# CameraBoard.net
KiCad netlist of a schematic drawn in Altium Designer
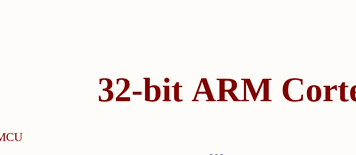
[diagram p0: CameraBoard.SchDoc, top left]
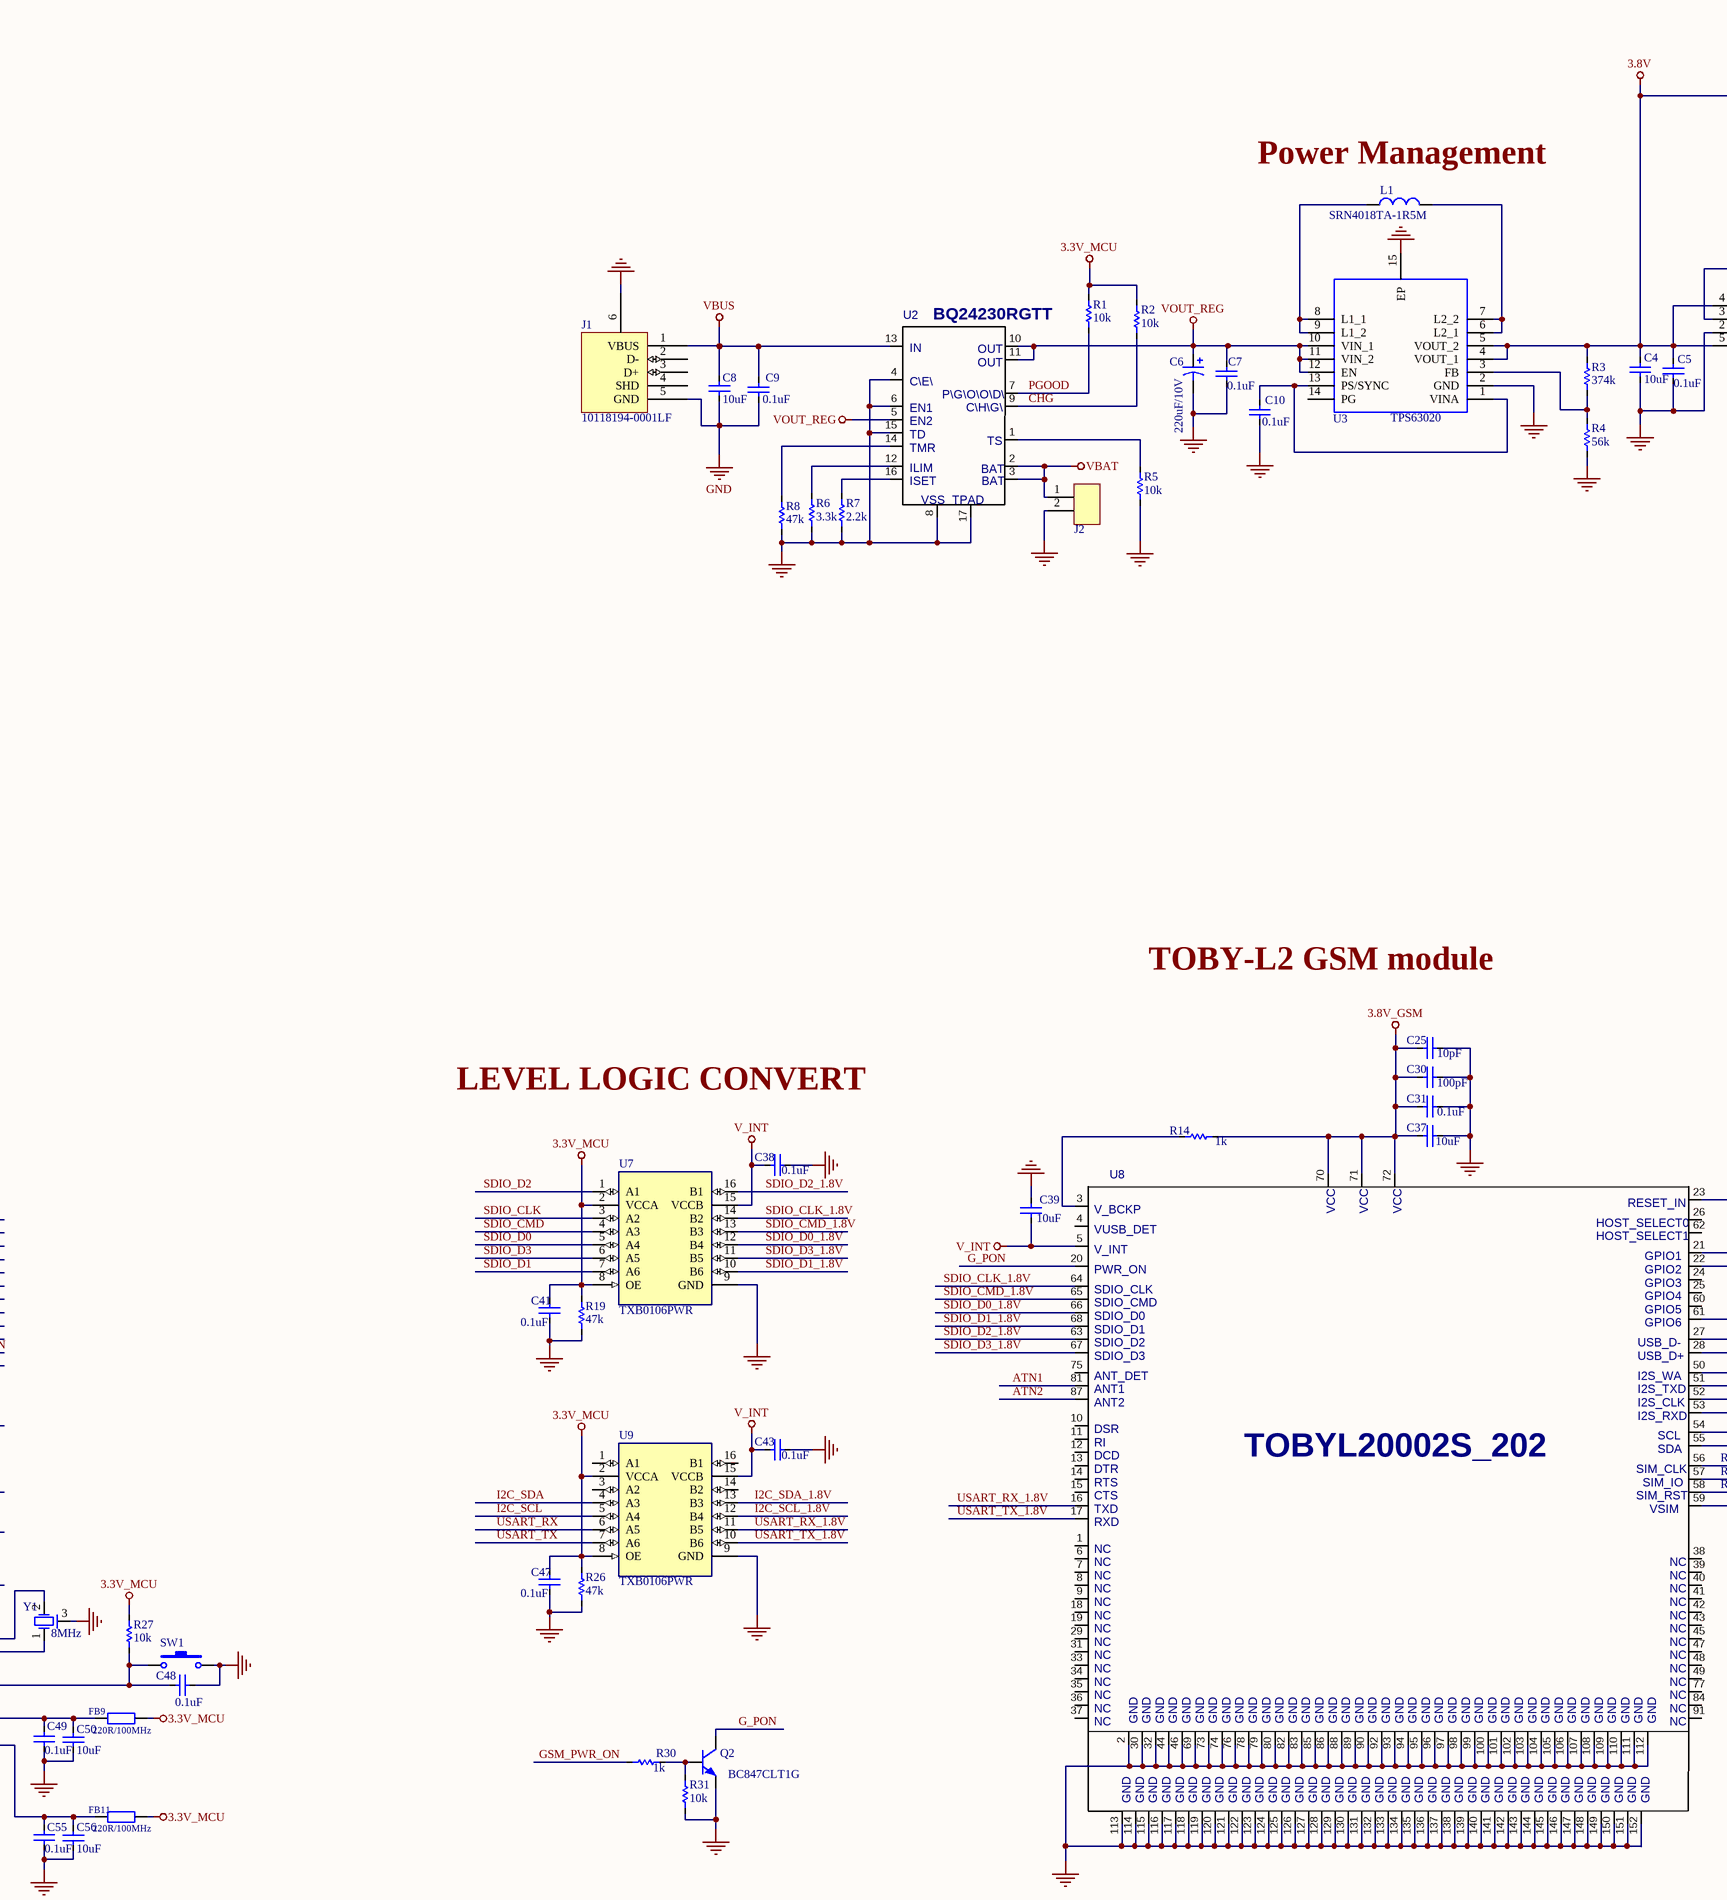
[diagram p1: CameraBoard.SchDoc, top middle]
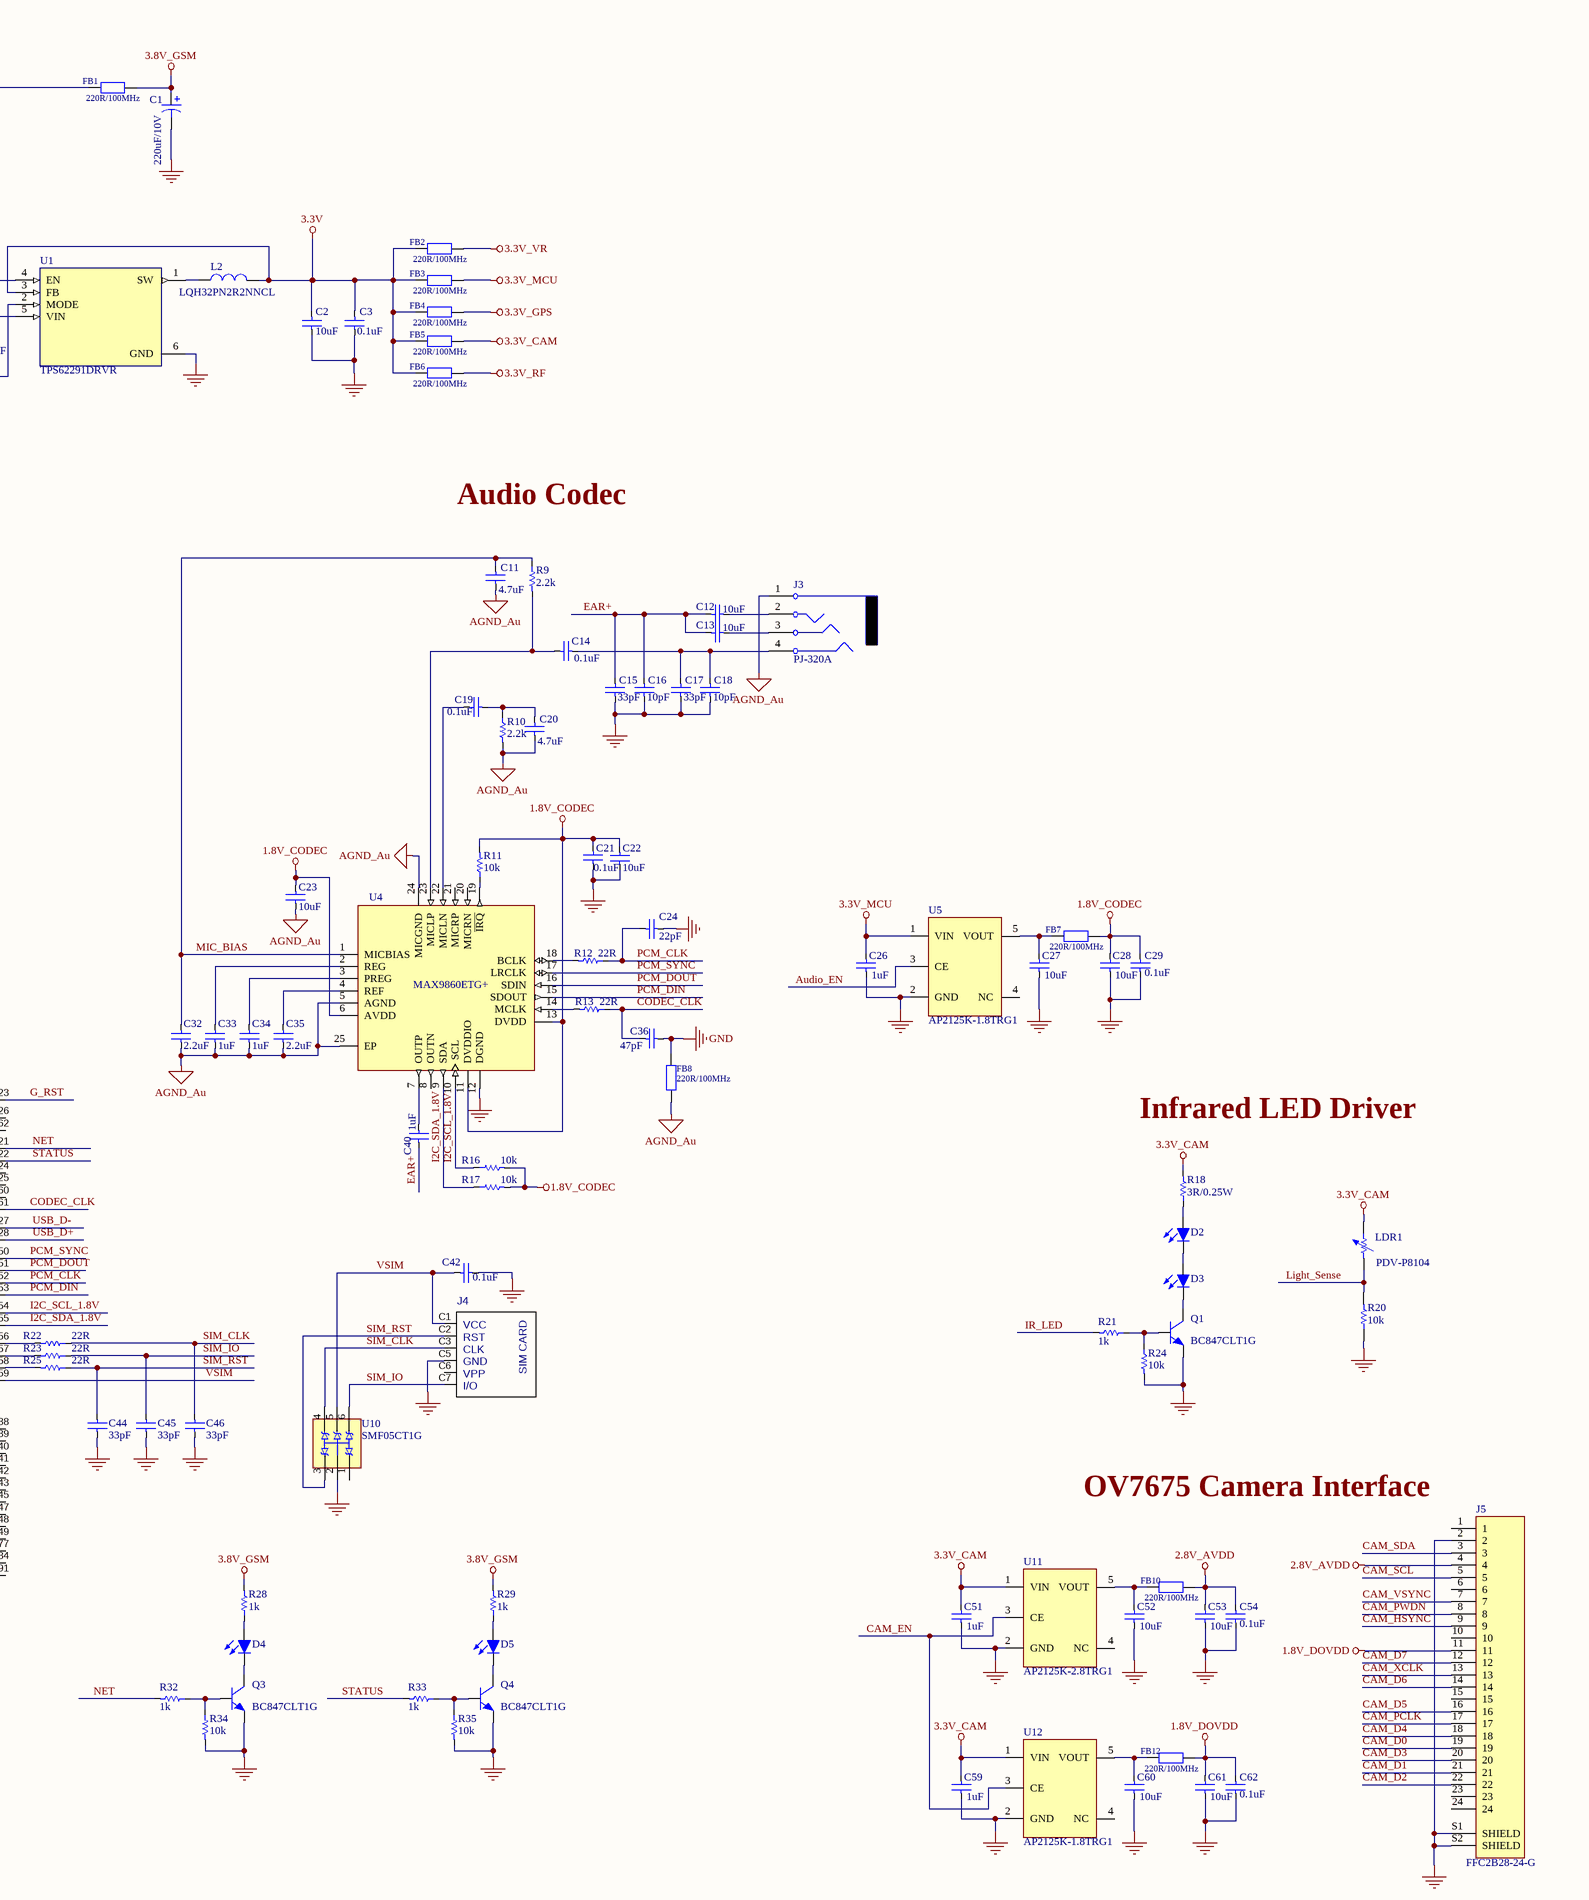
[diagram p2: CameraBoard.SchDoc, top right]
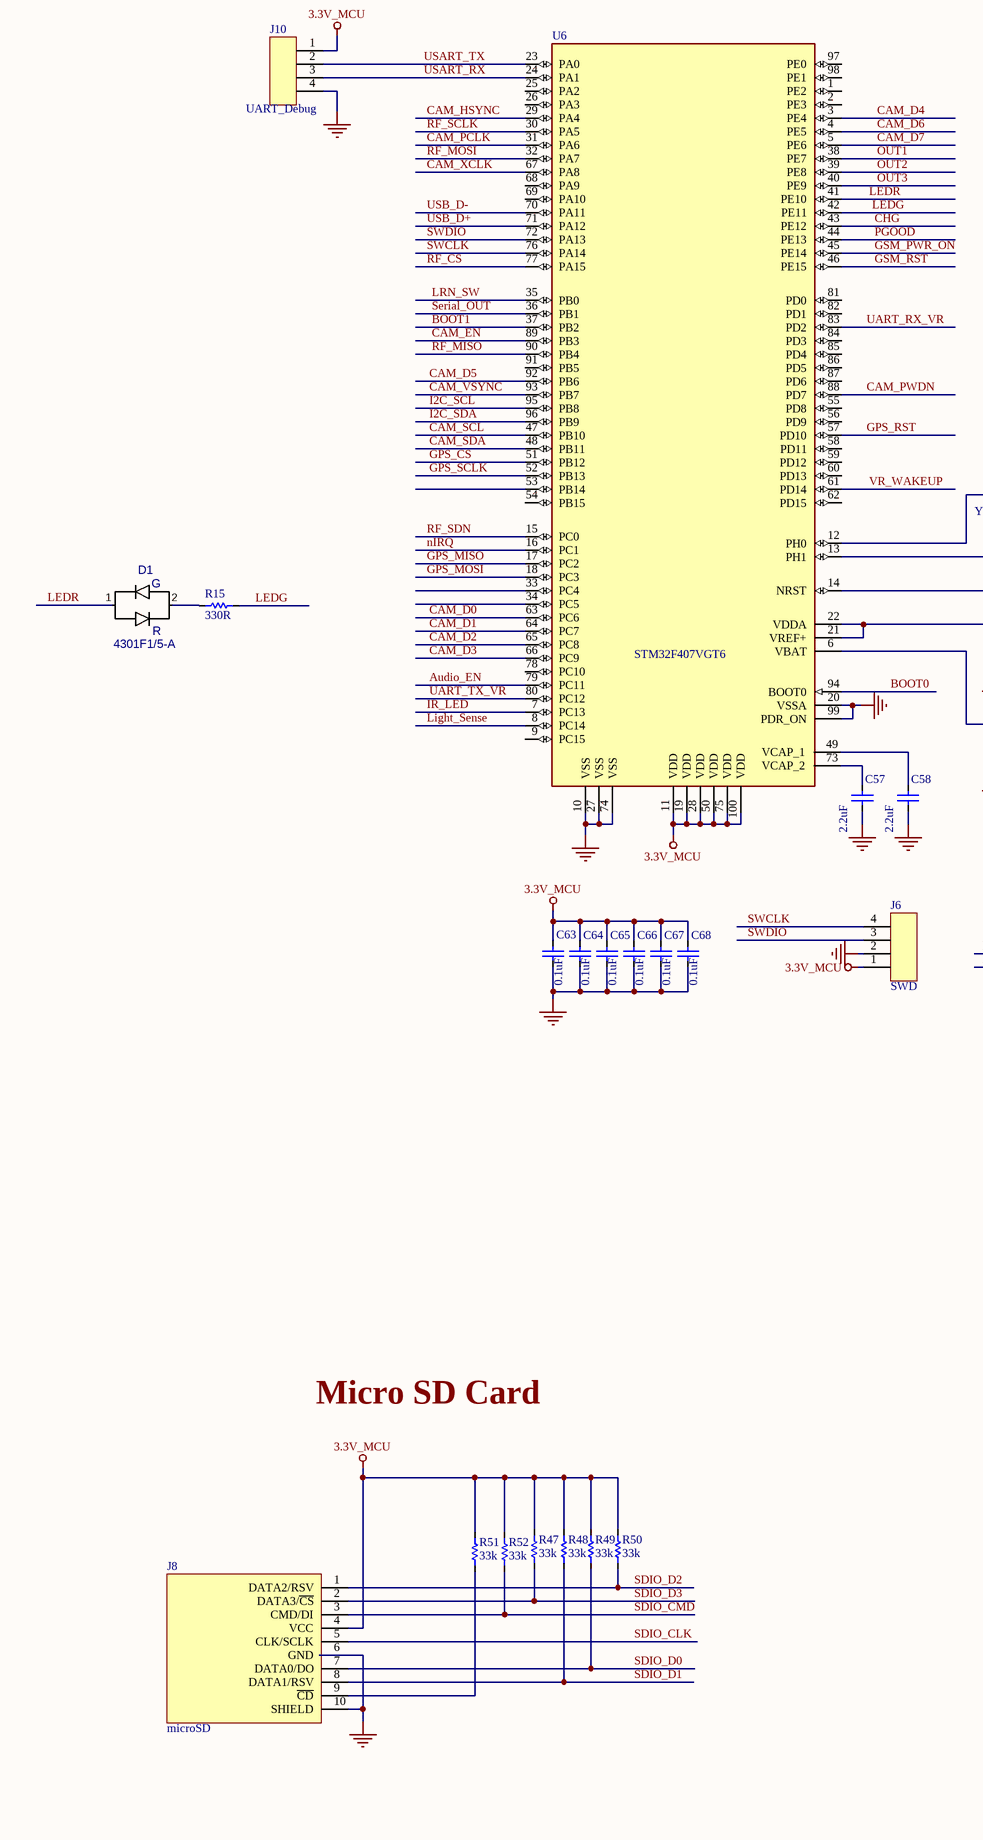
[diagram p3: CameraBoard.SchDoc, bottom left]
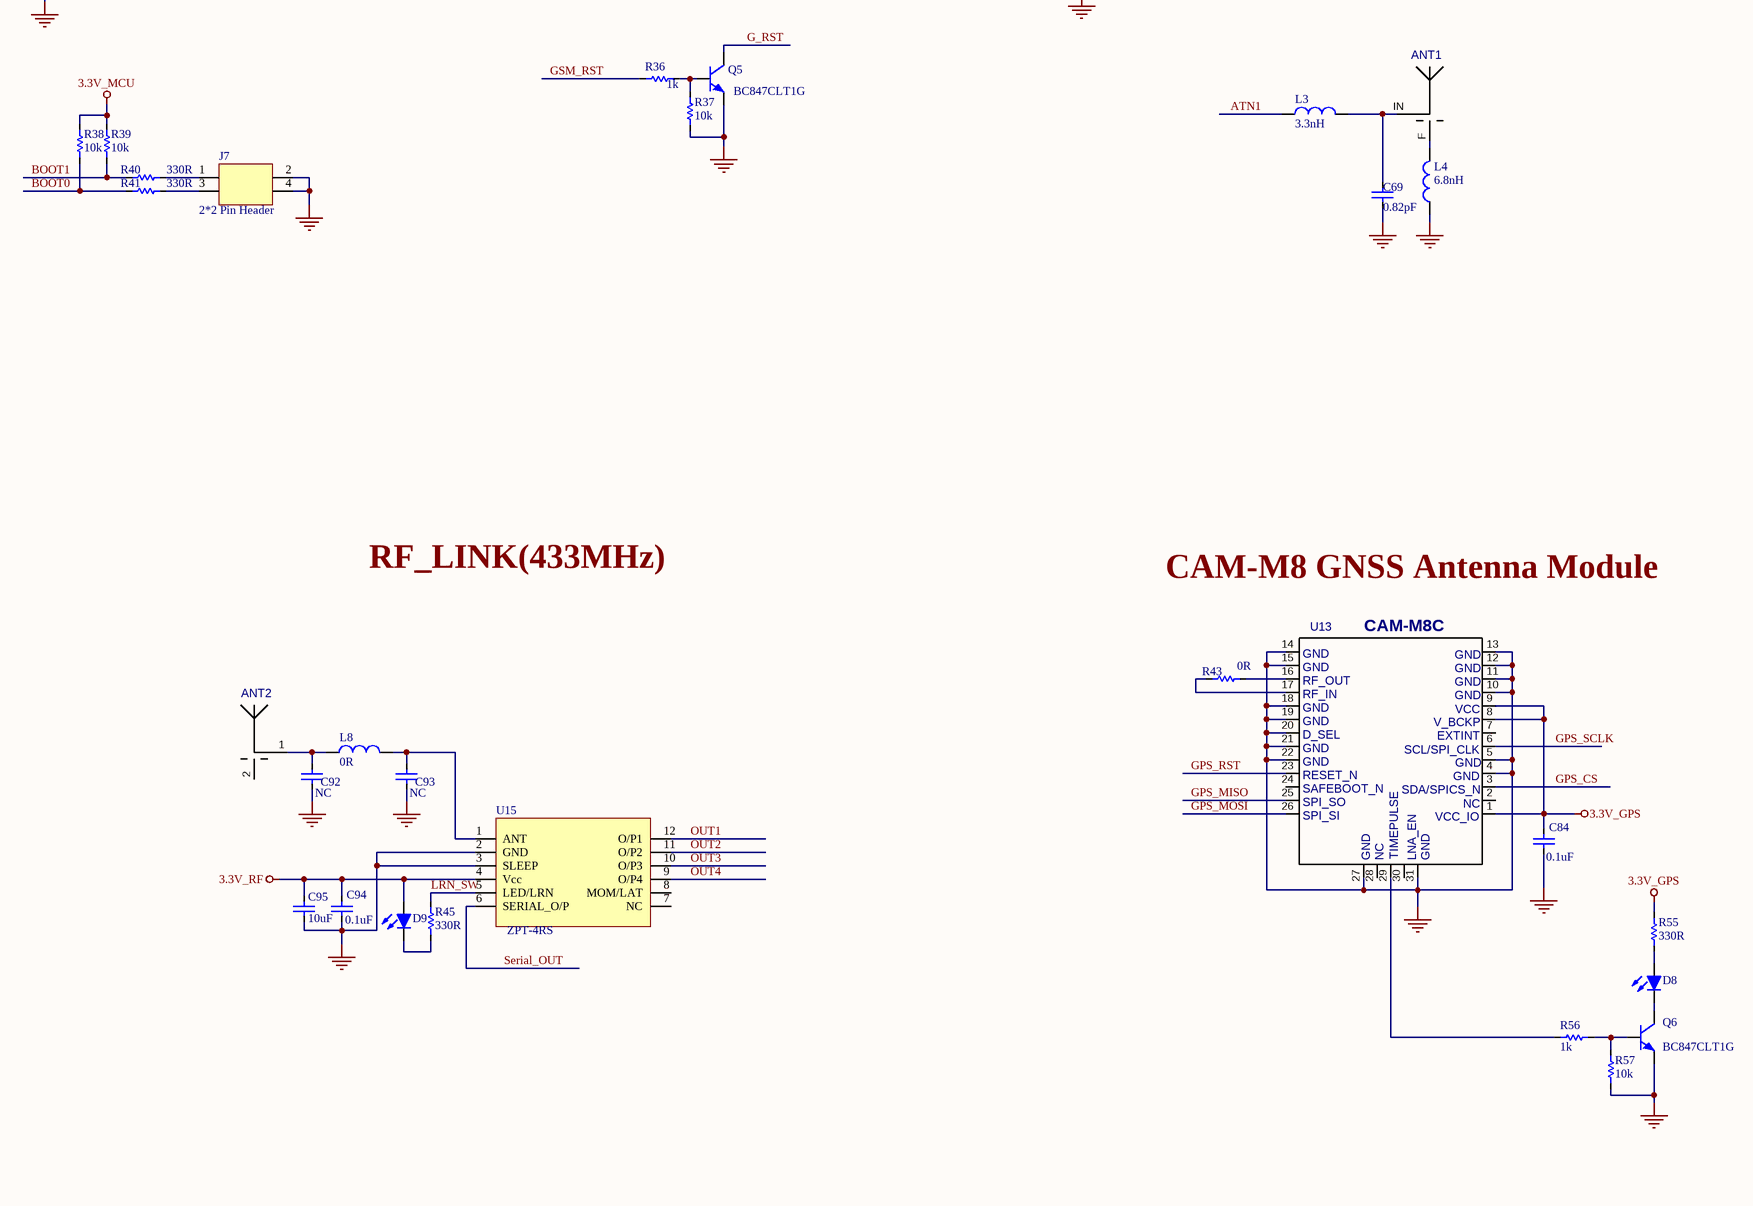
[diagram p4: CameraBoard.SchDoc, bottom middle]
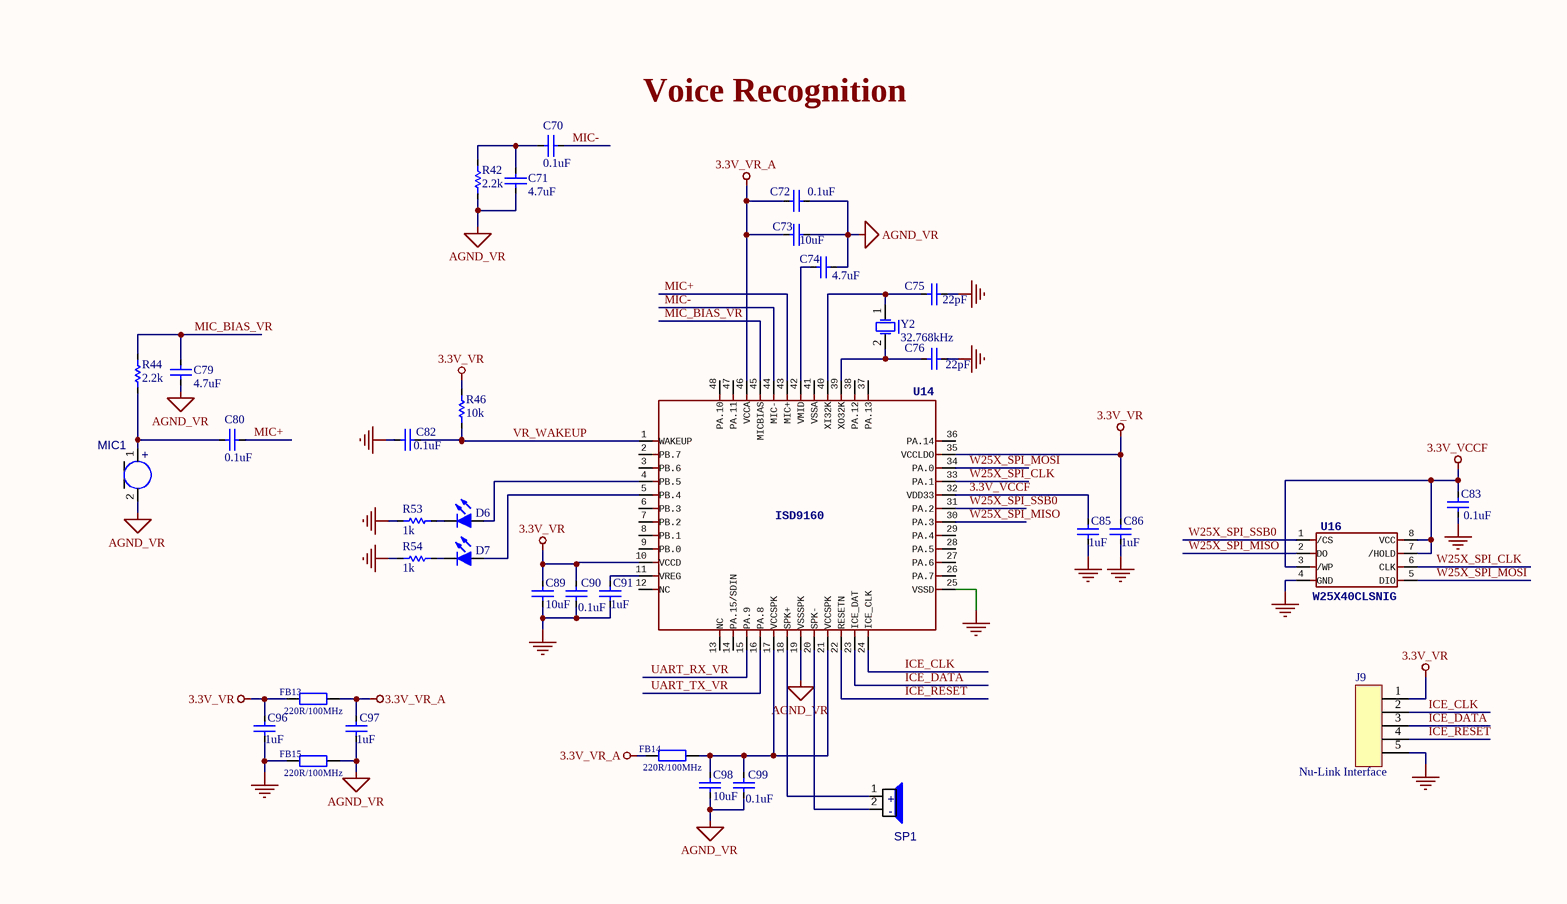
[diagram p5: CameraBoard.SchDoc, bottom right]

(export (version "E")
  (design (tool "Eeschema 10.0.6"))
  (components
    (comp (ref "ANT1")
      (value "Ant W3796_6")
      (footprint "Ant W3796_Ant W3796(Primary)")
      (libsource (lib "") (part "Ant W3796_6_1"))
    )
    (comp (ref "ANT2")
      (value "ACAG1204-868-T")
      (footprint "Antenna_SMD_ANT1204F002R0433A")
      (description "RF ANT 868MHZ CHIP SOLDER SMD")
      (libsource (lib "CameraBoard") (part "Ant W3796_6"))
    )
    (comp (ref "C1")
      (value "220uF/10V")
      (footprint "Tantalum C(E)")
      (description "TPSE227K010T0100V")
      (fields (field (name "PUBLISHER") "Altium Limited"))
      (libsource (lib "Miscellaneous Devices") (part "Cap Pol1"))
    )
    (comp (ref "C2")
      (value "10uF")
      (footprint "SMD_C(0603)")
      (description "PHE840MA6100MA04R17")
      (fields
        (field (name "MANUFACTURER") "Yageo")
        (field (name "MANUFACTURER PART NUMBER") "CC0603KPX7R9BB104")
      )
      (libsource (lib "Miscellaneous Devices") (part "Cap"))
    )
    (comp (ref "C3")
      (value "0.1uF")
      (footprint "SMD_C(0402)")
      (description "PHE840MA6100MA04R17")
      (fields
        (field (name "MANUFACTURER") "Yageo")
        (field (name "MANUFACTURER PART NUMBER") "CC0603KPX7R9BB104")
      )
      (libsource (lib "Miscellaneous Devices") (part "Cap"))
    )
    (comp (ref "C4")
      (value "10uF")
      (footprint "SMD_C(0603)")
      (description "PHE840MA6100MA04R17")
      (fields
        (field (name "MANUFACTURER") "Yageo")
        (field (name "MANUFACTURER PART NUMBER") "CC0603KPX7R9BB104")
      )
      (libsource (lib "Miscellaneous Devices") (part "Cap"))
    )
    (comp (ref "C5")
      (value "0.1uF")
      (footprint "SMD_C(0402)")
      (description "PHE840MA6100MA04R17")
      (fields
        (field (name "MANUFACTURER") "Yageo")
        (field (name "MANUFACTURER PART NUMBER") "CC0603KPX7R9BB104")
      )
      (libsource (lib "Miscellaneous Devices") (part "Cap"))
    )
    (comp (ref "C6")
      (value "220uF/10V")
      (footprint "Tantalum C(E)")
      (description "TPSE227K010T0100V")
      (fields (field (name "PUBLISHER") "Altium Limited"))
      (libsource (lib "Miscellaneous Devices") (part "Cap Pol1"))
    )
    (comp (ref "C7")
      (value "0.1uF")
      (footprint "SMD_C(0402)")
      (description "PHE840MA6100MA04R17")
      (fields
        (field (name "MANUFACTURER") "Yageo")
        (field (name "MANUFACTURER PART NUMBER") "CC0603KPX7R9BB104")
      )
      (libsource (lib "Miscellaneous Devices") (part "Cap"))
    )
    (comp (ref "C8")
      (value "10uF")
      (footprint "SMD_C(0603)")
      (description "PHE840MA6100MA04R17")
      (fields
        (field (name "MANUFACTURER") "Yageo")
        (field (name "MANUFACTURER PART NUMBER") "CC0603KPX7R9BB104")
      )
      (libsource (lib "Miscellaneous Devices") (part "Cap"))
    )
    (comp (ref "C9")
      (value "0.1uF")
      (footprint "SMD_C(0402)")
      (description "PHE840MA6100MA04R17")
      (fields
        (field (name "MANUFACTURER") "Yageo")
        (field (name "MANUFACTURER PART NUMBER") "CC0603KPX7R9BB104")
      )
      (libsource (lib "Miscellaneous Devices") (part "Cap"))
    )
    (comp (ref "C10")
      (value "0.1uF")
      (footprint "SMD_C(0402)")
      (description "PHE840MA6100MA04R17")
      (fields
        (field (name "MANUFACTURER") "Yageo")
        (field (name "MANUFACTURER PART NUMBER") "CC0603KPX7R9BB104")
      )
      (libsource (lib "Miscellaneous Devices") (part "Cap"))
    )
    (comp (ref "C11")
      (value "4.7uF")
      (footprint "SMD_C(0603)")
      (description "PHE840MA6100MA04R17")
      (fields
        (field (name "MANUFACTURER") "Yageo")
        (field (name "MANUFACTURER PART NUMBER") "CC0603KPX7R9BB104")
      )
      (libsource (lib "Miscellaneous Devices") (part "Cap"))
    )
    (comp (ref "C12")
      (value "10uF")
      (footprint "SMD_C(0603)")
      (description "PHE840MA6100MA04R17")
      (fields
        (field (name "MANUFACTURER") "Yageo")
        (field (name "MANUFACTURER PART NUMBER") "CC0603KPX7R9BB104")
      )
      (libsource (lib "Miscellaneous Devices") (part "Cap"))
    )
    (comp (ref "C13")
      (value "10uF")
      (footprint "SMD_C(0603)")
      (description "PHE840MA6100MA04R17")
      (fields
        (field (name "MANUFACTURER") "Yageo")
        (field (name "MANUFACTURER PART NUMBER") "CC0603KPX7R9BB104")
      )
      (libsource (lib "Miscellaneous Devices") (part "Cap"))
    )
    (comp (ref "C14")
      (value "0.1uF")
      (footprint "SMD_C(0402)")
      (description "PHE840MA6100MA04R17")
      (fields
        (field (name "MANUFACTURER") "Yageo")
        (field (name "MANUFACTURER PART NUMBER") "CC0603KPX7R9BB104")
      )
      (libsource (lib "Miscellaneous Devices") (part "Cap"))
    )
    (comp (ref "C15")
      (value "33pF")
      (footprint "SMD_C(0402)")
      (description "PHE840MA6100MA04R17")
      (fields
        (field (name "MANUFACTURER") "Yageo")
        (field (name "MANUFACTURER PART NUMBER") "CC0603KPX7R9BB104")
      )
      (libsource (lib "Miscellaneous Devices") (part "Cap"))
    )
    (comp (ref "C16")
      (value "10pF")
      (footprint "SMD_C(0402)")
      (description "PHE840MA6100MA04R17")
      (fields
        (field (name "MANUFACTURER") "Yageo")
        (field (name "MANUFACTURER PART NUMBER") "CC0603KPX7R9BB104")
      )
      (libsource (lib "Miscellaneous Devices") (part "Cap"))
    )
    (comp (ref "C17")
      (value "33pF")
      (footprint "SMD_C(0402)")
      (description "PHE840MA6100MA04R17")
      (fields
        (field (name "MANUFACTURER") "Yageo")
        (field (name "MANUFACTURER PART NUMBER") "CC0603KPX7R9BB104")
      )
      (libsource (lib "Miscellaneous Devices") (part "Cap"))
    )
    (comp (ref "C18")
      (value "10pF")
      (footprint "SMD_C(0402)")
      (description "PHE840MA6100MA04R17")
      (fields
        (field (name "MANUFACTURER") "Yageo")
        (field (name "MANUFACTURER PART NUMBER") "CC0603KPX7R9BB104")
      )
      (libsource (lib "Miscellaneous Devices") (part "Cap"))
    )
    (comp (ref "C19")
      (value "0.1uF")
      (footprint "SMD_C(0402)")
      (description "PHE840MA6100MA04R17")
      (fields
        (field (name "MANUFACTURER") "Yageo")
        (field (name "MANUFACTURER PART NUMBER") "CC0603KPX7R9BB104")
      )
      (libsource (lib "Miscellaneous Devices") (part "Cap"))
    )
    (comp (ref "C20")
      (value "4.7uF")
      (footprint "SMD_C(0603)")
      (description "PHE840MA6100MA04R17")
      (fields
        (field (name "MANUFACTURER") "Yageo")
        (field (name "MANUFACTURER PART NUMBER") "CC0603KPX7R9BB104")
      )
      (libsource (lib "Miscellaneous Devices") (part "Cap"))
    )
    (comp (ref "C21")
      (value "0.1uF")
      (footprint "SMD_C(0402)")
      (description "PHE840MA6100MA04R17")
      (fields
        (field (name "MANUFACTURER") "Yageo")
        (field (name "MANUFACTURER PART NUMBER") "CC0603KPX7R9BB104")
      )
      (libsource (lib "Miscellaneous Devices") (part "Cap"))
    )
    (comp (ref "C22")
      (value "10uF")
      (footprint "SMD_C(0603)")
      (description "PHE840MA6100MA04R17")
      (fields
        (field (name "MANUFACTURER") "Yageo")
        (field (name "MANUFACTURER PART NUMBER") "CC0603KPX7R9BB104")
      )
      (libsource (lib "Miscellaneous Devices") (part "Cap"))
    )
    (comp (ref "C23")
      (value "10uF")
      (footprint "SMD_C(0603)")
      (description "PHE840MA6100MA04R17")
      (fields
        (field (name "MANUFACTURER") "Yageo")
        (field (name "MANUFACTURER PART NUMBER") "CC0603KPX7R9BB104")
      )
      (libsource (lib "Miscellaneous Devices") (part "Cap"))
    )
    (comp (ref "C24")
      (value "22pF")
      (footprint "SMD_C(0402)")
      (description "PHE840MA6100MA04R17")
      (fields
        (field (name "MANUFACTURER") "Yageo")
        (field (name "MANUFACTURER PART NUMBER") "CC0603KPX7R9BB104")
      )
      (libsource (lib "Miscellaneous Devices") (part "Cap"))
    )
    (comp (ref "C25")
      (value "10pF")
      (footprint "SMD_C(0402)")
      (description "PHE840MA6100MA04R17")
      (fields
        (field (name "MANUFACTURER") "Yageo")
        (field (name "MANUFACTURER PART NUMBER") "CC0603KPX7R9BB104")
      )
      (libsource (lib "Miscellaneous Devices") (part "Cap"))
    )
    (comp (ref "C26")
      (value "1uF")
      (footprint "SMD_C(0603)")
      (description "PHE840MA6100MA04R17")
      (fields
        (field (name "MANUFACTURER") "Yageo")
        (field (name "MANUFACTURER PART NUMBER") "CC0603KPX7R9BB104")
      )
      (libsource (lib "Miscellaneous Devices") (part "Cap"))
    )
    (comp (ref "C27")
      (value "10uF")
      (footprint "SMD_C(0603)")
      (description "PHE840MA6100MA04R17")
      (fields
        (field (name "MANUFACTURER") "Yageo")
        (field (name "MANUFACTURER PART NUMBER") "CC0603KPX7R9BB104")
      )
      (libsource (lib "Miscellaneous Devices") (part "Cap"))
    )
    (comp (ref "C28")
      (value "10uF")
      (footprint "SMD_C(0603)")
      (description "PHE840MA6100MA04R17")
      (fields
        (field (name "MANUFACTURER") "Yageo")
        (field (name "MANUFACTURER PART NUMBER") "CC0603KPX7R9BB104")
      )
      (libsource (lib "Miscellaneous Devices") (part "Cap"))
    )
    (comp (ref "C29")
      (value "0.1uF")
      (footprint "SMD_C(0402)")
      (description "PHE840MA6100MA04R17")
      (fields
        (field (name "MANUFACTURER") "Yageo")
        (field (name "MANUFACTURER PART NUMBER") "CC0603KPX7R9BB104")
      )
      (libsource (lib "Miscellaneous Devices") (part "Cap"))
    )
    (comp (ref "C30")
      (value "100pF")
      (footprint "SMD_C(0402)")
      (description "PHE840MA6100MA04R17")
      (fields
        (field (name "MANUFACTURER") "Yageo")
        (field (name "MANUFACTURER PART NUMBER") "CC0603KPX7R9BB104")
      )
      (libsource (lib "Miscellaneous Devices") (part "Cap"))
    )
    (comp (ref "C31")
      (value "0.1uF")
      (footprint "SMD_C(0402)")
      (description "PHE840MA6100MA04R17")
      (fields
        (field (name "MANUFACTURER") "Yageo")
        (field (name "MANUFACTURER PART NUMBER") "CC0603KPX7R9BB104")
      )
      (libsource (lib "Miscellaneous Devices") (part "Cap"))
    )
    (comp (ref "C32")
      (value "2.2uF")
      (footprint "SMD_C(0603)")
      (description "PHE840MA6100MA04R17")
      (fields
        (field (name "MANUFACTURER") "Yageo")
        (field (name "MANUFACTURER PART NUMBER") "CC0603KPX7R9BB104")
      )
      (libsource (lib "Miscellaneous Devices") (part "Cap"))
    )
    (comp (ref "C33")
      (value "1uF")
      (footprint "SMD_C(0603)")
      (description "PHE840MA6100MA04R17")
      (fields
        (field (name "MANUFACTURER") "Yageo")
        (field (name "MANUFACTURER PART NUMBER") "CC0603KPX7R9BB104")
      )
      (libsource (lib "Miscellaneous Devices") (part "Cap"))
    )
    (comp (ref "C34")
      (value "1uF")
      (footprint "SMD_C(0603)")
      (description "PHE840MA6100MA04R17")
      (fields
        (field (name "MANUFACTURER") "Yageo")
        (field (name "MANUFACTURER PART NUMBER") "CC0603KPX7R9BB104")
      )
      (libsource (lib "Miscellaneous Devices") (part "Cap"))
    )
    (comp (ref "C35")
      (value "2.2uF")
      (footprint "SMD_C(0603)")
      (description "PHE840MA6100MA04R17")
      (fields
        (field (name "MANUFACTURER") "Yageo")
        (field (name "MANUFACTURER PART NUMBER") "CC0603KPX7R9BB104")
      )
      (libsource (lib "Miscellaneous Devices") (part "Cap"))
    )
    (comp (ref "C36")
      (value "47pF")
      (footprint "SMD_C(0402)")
      (description "PHE840MA6100MA04R17")
      (fields
        (field (name "MANUFACTURER") "Yageo")
        (field (name "MANUFACTURER PART NUMBER") "CC0603KPX7R9BB104")
      )
      (libsource (lib "Miscellaneous Devices") (part "Cap"))
    )
    (comp (ref "C37")
      (value "10uF")
      (footprint "SMD_C(0603)")
      (description "PHE840MA6100MA04R17")
      (fields
        (field (name "MANUFACTURER") "Yageo")
        (field (name "MANUFACTURER PART NUMBER") "CC0603KPX7R9BB104")
      )
      (libsource (lib "Miscellaneous Devices") (part "Cap"))
    )
    (comp (ref "C38")
      (value "0.1uF")
      (footprint "SMD_C(0402)")
      (description "PHE840MA6100MA04R17")
      (fields
        (field (name "MANUFACTURER") "Yageo")
        (field (name "MANUFACTURER PART NUMBER") "CC0603KPX7R9BB104")
      )
      (libsource (lib "Miscellaneous Devices") (part "Cap"))
    )
    (comp (ref "C39")
      (value "10uF")
      (footprint "SMD_C(0603)")
      (description "PHE840MA6100MA04R17")
      (fields
        (field (name "MANUFACTURER") "Yageo")
        (field (name "MANUFACTURER PART NUMBER") "CC0603KPX7R9BB104")
      )
      (libsource (lib "Miscellaneous Devices") (part "Cap"))
    )
    (comp (ref "C40")
      (value "1uF")
      (footprint "SMD_C(0603)")
      (description "PHE840MA6100MA04R17")
      (fields
        (field (name "MANUFACTURER") "Yageo")
        (field (name "MANUFACTURER PART NUMBER") "CC0603KPX7R9BB104")
      )
      (libsource (lib "Miscellaneous Devices") (part "Cap"))
    )
    (comp (ref "C41")
      (value "0.1uF")
      (footprint "SMD_C(0402)")
      (description "PHE840MA6100MA04R17")
      (fields
        (field (name "MANUFACTURER") "Yageo")
        (field (name "MANUFACTURER PART NUMBER") "CC0603KPX7R9BB104")
      )
      (libsource (lib "Miscellaneous Devices") (part "Cap"))
    )
    (comp (ref "C42")
      (value "0.1uF")
      (footprint "SMD_C(0402)")
      (description "PHE840MA6100MA04R17")
      (fields
        (field (name "MANUFACTURER") "Yageo")
        (field (name "MANUFACTURER PART NUMBER") "CC0603KPX7R9BB104")
      )
      (libsource (lib "Miscellaneous Devices") (part "Cap"))
    )
    (comp (ref "C43")
      (value "0.1uF")
      (footprint "SMD_C(0402)")
      (description "PHE840MA6100MA04R17")
      (fields
        (field (name "MANUFACTURER") "Yageo")
        (field (name "MANUFACTURER PART NUMBER") "CC0603KPX7R9BB104")
      )
      (libsource (lib "Miscellaneous Devices") (part "Cap"))
    )
    (comp (ref "C44")
      (value "33pF")
      (footprint "SMD_C(0402)")
      (description "PHE840MA6100MA04R17")
      (fields
        (field (name "MANUFACTURER") "Yageo")
        (field (name "MANUFACTURER PART NUMBER") "CC0603KPX7R9BB104")
      )
      (libsource (lib "Miscellaneous Devices") (part "Cap"))
    )
    (comp (ref "C45")
      (value "33pF")
      (footprint "SMD_C(0402)")
      (description "PHE840MA6100MA04R17")
      (fields
        (field (name "MANUFACTURER") "Yageo")
        (field (name "MANUFACTURER PART NUMBER") "CC0603KPX7R9BB104")
      )
      (libsource (lib "Miscellaneous Devices") (part "Cap"))
    )
    (comp (ref "C46")
      (value "33pF")
      (footprint "SMD_C(0402)")
      (description "PHE840MA6100MA04R17")
      (fields
        (field (name "MANUFACTURER") "Yageo")
        (field (name "MANUFACTURER PART NUMBER") "CC0603KPX7R9BB104")
      )
      (libsource (lib "Miscellaneous Devices") (part "Cap"))
    )
    (comp (ref "C47")
      (value "0.1uF")
      (footprint "SMD_C(0402)")
      (description "PHE840MA6100MA04R17")
      (fields
        (field (name "MANUFACTURER") "Yageo")
        (field (name "MANUFACTURER PART NUMBER") "CC0603KPX7R9BB104")
      )
      (libsource (lib "Miscellaneous Devices") (part "Cap"))
    )
    (comp (ref "C48")
      (value "0.1uF")
      (footprint "SMD_C(0402)")
      (description "PHE840MA6100MA04R17")
      (fields
        (field (name "MANUFACTURER") "Yageo")
        (field (name "MANUFACTURER PART NUMBER") "CC0603KPX7R9BB104")
      )
      (libsource (lib "Miscellaneous Devices") (part "Cap"))
    )
    (comp (ref "C49")
      (value "0.1uF")
      (footprint "SMD_C(0402)")
      (description "PHE840MA6100MA04R17")
      (fields
        (field (name "MANUFACTURER") "Yageo")
        (field (name "MANUFACTURER PART NUMBER") "CC0603KPX7R9BB104")
      )
      (libsource (lib "Miscellaneous Devices") (part "Cap"))
    )
    (comp (ref "C50")
      (value "10uF")
      (footprint "SMD_C(0603)")
      (description "PHE840MA6100MA04R17")
      (fields
        (field (name "MANUFACTURER") "Yageo")
        (field (name "MANUFACTURER PART NUMBER") "CC0603KPX7R9BB104")
      )
      (libsource (lib "Miscellaneous Devices") (part "Cap"))
    )
    (comp (ref "C51")
      (value "1uF")
      (footprint "SMD_C(0603)")
      (description "PHE840MA6100MA04R17")
      (fields
        (field (name "MANUFACTURER") "Yageo")
        (field (name "MANUFACTURER PART NUMBER") "CC0603KPX7R9BB104")
      )
      (libsource (lib "Miscellaneous Devices") (part "Cap"))
    )
    (comp (ref "C52")
      (value "10uF")
      (footprint "SMD_C(0603)")
      (description "PHE840MA6100MA04R17")
      (fields
        (field (name "MANUFACTURER") "Yageo")
        (field (name "MANUFACTURER PART NUMBER") "CC0603KPX7R9BB104")
      )
      (libsource (lib "Miscellaneous Devices") (part "Cap"))
    )
    (comp (ref "C53")
      (value "10uF")
      (footprint "SMD_C(0603)")
      (description "PHE840MA6100MA04R17")
      (fields
        (field (name "MANUFACTURER") "Yageo")
        (field (name "MANUFACTURER PART NUMBER") "CC0603KPX7R9BB104")
      )
      (libsource (lib "Miscellaneous Devices") (part "Cap"))
    )
    (comp (ref "C54")
      (value "0.1uF")
      (footprint "SMD_C(0402)")
      (description "PHE840MA6100MA04R17")
      (fields
        (field (name "MANUFACTURER") "Yageo")
        (field (name "MANUFACTURER PART NUMBER") "CC0603KPX7R9BB104")
      )
      (libsource (lib "Miscellaneous Devices") (part "Cap"))
    )
    (comp (ref "C55")
      (value "0.1uF")
      (footprint "SMD_C(0402)")
      (description "PHE840MA6100MA04R17")
      (fields
        (field (name "MANUFACTURER") "Yageo")
        (field (name "MANUFACTURER PART NUMBER") "CC0603KPX7R9BB104")
      )
      (libsource (lib "Miscellaneous Devices") (part "Cap"))
    )
    (comp (ref "C56")
      (value "10uF")
      (footprint "SMD_C(0603)")
      (description "PHE840MA6100MA04R17")
      (fields
        (field (name "MANUFACTURER") "Yageo")
        (field (name "MANUFACTURER PART NUMBER") "CC0603KPX7R9BB104")
      )
      (libsource (lib "Miscellaneous Devices") (part "Cap"))
    )
    (comp (ref "C57")
      (value "2.2uF")
      (footprint "SMD_C(0603)")
      (description "PHE840MA6100MA04R17")
      (fields
        (field (name "MANUFACTURER") "Yageo")
        (field (name "MANUFACTURER PART NUMBER") "CC0603KPX7R9BB104")
      )
      (libsource (lib "Miscellaneous Devices") (part "Cap"))
    )
    (comp (ref "C58")
      (value "2.2uF")
      (footprint "SMD_C(0603)")
      (description "PHE840MA6100MA04R17")
      (fields
        (field (name "MANUFACTURER") "Yageo")
        (field (name "MANUFACTURER PART NUMBER") "CC0603KPX7R9BB104")
      )
      (libsource (lib "Miscellaneous Devices") (part "Cap"))
    )
    (comp (ref "C59")
      (value "1uF")
      (footprint "SMD_C(0603)")
      (description "PHE840MA6100MA04R17")
      (fields
        (field (name "MANUFACTURER") "Yageo")
        (field (name "MANUFACTURER PART NUMBER") "CC0603KPX7R9BB104")
      )
      (libsource (lib "Miscellaneous Devices") (part "Cap"))
    )
    (comp (ref "C60")
      (value "10uF")
      (footprint "SMD_C(0603)")
      (description "PHE840MA6100MA04R17")
      (fields
        (field (name "MANUFACTURER") "Yageo")
        (field (name "MANUFACTURER PART NUMBER") "CC0603KPX7R9BB104")
      )
      (libsource (lib "Miscellaneous Devices") (part "Cap"))
    )
    (comp (ref "C61")
      (value "10uF")
      (footprint "SMD_C(0603)")
      (description "PHE840MA6100MA04R17")
      (fields
        (field (name "MANUFACTURER") "Yageo")
        (field (name "MANUFACTURER PART NUMBER") "CC0603KPX7R9BB104")
      )
      (libsource (lib "Miscellaneous Devices") (part "Cap"))
    )
    (comp (ref "C62")
      (value "0.1uF")
      (footprint "SMD_C(0402)")
      (description "PHE840MA6100MA04R17")
      (fields
        (field (name "MANUFACTURER") "Yageo")
        (field (name "MANUFACTURER PART NUMBER") "CC0603KPX7R9BB104")
      )
      (libsource (lib "Miscellaneous Devices") (part "Cap"))
    )
    (comp (ref "C63")
      (value "0.1uF")
      (footprint "SMD_C(0402)")
      (description "PHE840MA6100MA04R17")
      (fields
        (field (name "MANUFACTURER") "Yageo")
        (field (name "MANUFACTURER PART NUMBER") "CC0603KPX7R9BB104")
      )
      (libsource (lib "Miscellaneous Devices") (part "Cap"))
    )
    (comp (ref "C64")
      (value "0.1uF")
      (footprint "SMD_C(0402)")
      (description "PHE840MA6100MA04R17")
      (fields
        (field (name "MANUFACTURER") "Yageo")
        (field (name "MANUFACTURER PART NUMBER") "CC0603KPX7R9BB104")
      )
      (libsource (lib "Miscellaneous Devices") (part "Cap"))
    )
    (comp (ref "C65")
      (value "0.1uF")
      (footprint "SMD_C(0402)")
      (description "PHE840MA6100MA04R17")
      (fields
        (field (name "MANUFACTURER") "Yageo")
        (field (name "MANUFACTURER PART NUMBER") "CC0603KPX7R9BB104")
      )
      (libsource (lib "Miscellaneous Devices") (part "Cap"))
    )
    (comp (ref "C66")
      (value "0.1uF")
      (footprint "SMD_C(0402)")
      (description "PHE840MA6100MA04R17")
      (fields
        (field (name "MANUFACTURER") "Yageo")
        (field (name "MANUFACTURER PART NUMBER") "CC0603KPX7R9BB104")
      )
      (libsource (lib "Miscellaneous Devices") (part "Cap"))
    )
    (comp (ref "C67")
      (value "0.1uF")
      (footprint "SMD_C(0402)")
      (description "PHE840MA6100MA04R17")
      (fields
        (field (name "MANUFACTURER") "Yageo")
        (field (name "MANUFACTURER PART NUMBER") "CC0603KPX7R9BB104")
      )
      (libsource (lib "Miscellaneous Devices") (part "Cap"))
    )
    (comp (ref "C68")
      (value "0.1uF")
      (footprint "SMD_C(0402)")
      (description "PHE840MA6100MA04R17")
      (fields
        (field (name "MANUFACTURER") "Yageo")
        (field (name "MANUFACTURER PART NUMBER") "CC0603KPX7R9BB104")
      )
      (libsource (lib "Miscellaneous Devices") (part "Cap"))
    )
    (comp (ref "C69")
      (value "0.82pF")
      (footprint "SMD_C(0402)")
      (description "PHE840MA6100MA04R17")
      (fields
        (field (name "MANUFACTURER") "Yageo")
        (field (name "MANUFACTURER PART NUMBER") "CC0603KPX7R9BB104")
      )
      (libsource (lib "Miscellaneous Devices") (part "Cap"))
    )
    (comp (ref "C70")
      (value "0.1uF")
      (footprint "SMD_C(0402)")
      (description "PHE840MA6100MA04R17")
      (fields
        (field (name "MANUFACTURER") "Yageo")
        (field (name "MANUFACTURER PART NUMBER") "CC0603KPX7R9BB104")
      )
      (libsource (lib "Miscellaneous Devices") (part "Cap"))
    )
    (comp (ref "C71")
      (value "4.7uF")
      (footprint "SMD_C(0603)")
      (description "PHE840MA6100MA04R17")
      (fields
        (field (name "MANUFACTURER") "Yageo")
        (field (name "MANUFACTURER PART NUMBER") "CC0603KPX7R9BB104")
      )
      (libsource (lib "Miscellaneous Devices") (part "Cap"))
    )
    (comp (ref "C72")
      (value "0.1uF")
      (footprint "SMD_C(0402)")
      (description "PHE840MA6100MA04R17")
      (fields
        (field (name "MANUFACTURER") "Yageo")
        (field (name "MANUFACTURER PART NUMBER") "CC0603KPX7R9BB104")
      )
      (libsource (lib "Miscellaneous Devices") (part "Cap"))
    )
    (comp (ref "C73")
      (value "10uF")
      (footprint "SMD_C(0603)")
      (description "PHE840MA6100MA04R17")
      (fields
        (field (name "MANUFACTURER") "Yageo")
        (field (name "MANUFACTURER PART NUMBER") "CC0603KPX7R9BB104")
      )
      (libsource (lib "Miscellaneous Devices") (part "Cap"))
    )
    (comp (ref "C74")
      (value "4.7uF")
      (footprint "SMD_C(0603)")
      (description "PHE840MA6100MA04R17")
      (fields
        (field (name "MANUFACTURER") "Yageo")
        (field (name "MANUFACTURER PART NUMBER") "CC0603KPX7R9BB104")
      )
      (libsource (lib "Miscellaneous Devices") (part "Cap"))
    )
    (comp (ref "C75")
      (value "22pF")
      (footprint "SMD_C(0402)")
      (description "PHE840MA6100MA04R17")
      (fields
        (field (name "MANUFACTURER") "Yageo")
        (field (name "MANUFACTURER PART NUMBER") "CC0603KPX7R9BB104")
      )
      (libsource (lib "Miscellaneous Devices") (part "Cap"))
    )
    (comp (ref "C76")
      (value "22pF")
      (footprint "SMD_C(0402)")
      (description "PHE840MA6100MA04R17")
      (fields
        (field (name "MANUFACTURER") "Yageo")
        (field (name "MANUFACTURER PART NUMBER") "CC0603KPX7R9BB104")
      )
      (libsource (lib "Miscellaneous Devices") (part "Cap"))
    )
    (comp (ref "C79")
      (value "4.7uF")
      (footprint "SMD_C(0603)")
      (description "PHE840MA6100MA04R17")
      (fields
        (field (name "MANUFACTURER") "Yageo")
        (field (name "MANUFACTURER PART NUMBER") "CC0603KPX7R9BB104")
      )
      (libsource (lib "Miscellaneous Devices") (part "Cap"))
    )
    (comp (ref "C80")
      (value "0.1uF")
      (footprint "SMD_C(0402)")
      (description "PHE840MA6100MA04R17")
      (fields
        (field (name "MANUFACTURER") "Yageo")
        (field (name "MANUFACTURER PART NUMBER") "CC0603KPX7R9BB104")
      )
      (libsource (lib "Miscellaneous Devices") (part "Cap"))
    )
    (comp (ref "C82")
      (value "0.1uF")
      (footprint "SMD_C(0402)")
      (description "PHE840MA6100MA04R17")
      (fields
        (field (name "MANUFACTURER") "Yageo")
        (field (name "MANUFACTURER PART NUMBER") "CC0603KPX7R9BB104")
      )
      (libsource (lib "Miscellaneous Devices") (part "Cap"))
    )
    (comp (ref "C83")
      (value "0.1uF")
      (footprint "SMD_C(0402)")
      (description "PHE840MA6100MA04R17")
      (fields
        (field (name "MANUFACTURER") "Yageo")
        (field (name "MANUFACTURER PART NUMBER") "CC0603KPX7R9BB104")
      )
      (libsource (lib "Miscellaneous Devices") (part "Cap"))
    )
    (comp (ref "C84")
      (value "0.1uF")
      (footprint "SMD_C(0402)")
      (description "PHE840MA6100MA04R17")
      (fields
        (field (name "MANUFACTURER") "Yageo")
        (field (name "MANUFACTURER PART NUMBER") "CC0603KPX7R9BB104")
      )
      (libsource (lib "Miscellaneous Devices") (part "Cap"))
    )
    (comp (ref "C85")
      (value "1uF")
      (footprint "SMD_C(0603)")
      (description "PHE840MA6100MA04R17")
      (fields
        (field (name "MANUFACTURER") "Yageo")
        (field (name "MANUFACTURER PART NUMBER") "CC0603KPX7R9BB104")
      )
      (libsource (lib "Miscellaneous Devices") (part "Cap"))
    )
    (comp (ref "C86")
      (value "1uF")
      (footprint "SMD_C(0603)")
      (description "PHE840MA6100MA04R17")
      (fields
        (field (name "MANUFACTURER") "Yageo")
        (field (name "MANUFACTURER PART NUMBER") "CC0603KPX7R9BB104")
      )
      (libsource (lib "Miscellaneous Devices") (part "Cap"))
    )
    (comp (ref "C89")
      (value "10uF")
      (footprint "SMD_C(0603)")
      (description "PHE840MA6100MA04R17")
      (fields
        (field (name "MANUFACTURER") "Yageo")
        (field (name "MANUFACTURER PART NUMBER") "CC0603KPX7R9BB104")
      )
      (libsource (lib "Miscellaneous Devices") (part "Cap"))
    )
    (comp (ref "C90")
      (value "0.1uF")
      (footprint "SMD_C(0402)")
      (description "PHE840MA6100MA04R17")
      (fields
        (field (name "MANUFACTURER") "Yageo")
        (field (name "MANUFACTURER PART NUMBER") "CC0603KPX7R9BB104")
      )
      (libsource (lib "Miscellaneous Devices") (part "Cap"))
    )
    (comp (ref "C91")
      (value "1uF")
      (footprint "SMD_C(0603)")
      (description "PHE840MA6100MA04R17")
      (fields
        (field (name "MANUFACTURER") "Yageo")
        (field (name "MANUFACTURER PART NUMBER") "CC0603KPX7R9BB104")
      )
      (libsource (lib "Miscellaneous Devices") (part "Cap"))
    )
    (comp (ref "C92")
      (value "NC")
      (footprint "SMD_C(0402)")
      (description "PHE840MA6100MA04R17")
      (fields
        (field (name "MANUFACTURER") "Yageo")
        (field (name "MANUFACTURER PART NUMBER") "CC0603KPX7R9BB104")
      )
      (libsource (lib "Miscellaneous Devices") (part "Cap"))
    )
    (comp (ref "C93")
      (value "NC")
      (footprint "SMD_C(0402)")
      (description "PHE840MA6100MA04R17")
      (fields
        (field (name "MANUFACTURER") "Yageo")
        (field (name "MANUFACTURER PART NUMBER") "CC0603KPX7R9BB104")
      )
      (libsource (lib "Miscellaneous Devices") (part "Cap"))
    )
    (comp (ref "C94")
      (value "0.1uF")
      (footprint "SMD_C(0402)")
      (description "PHE840MA6100MA04R17")
      (fields
        (field (name "MANUFACTURER") "Yageo")
        (field (name "MANUFACTURER PART NUMBER") "CC0603KPX7R9BB104")
      )
      (libsource (lib "Miscellaneous Devices") (part "Cap"))
    )
    (comp (ref "C95")
      (value "10uF")
      (footprint "SMD_C(0603)")
      (description "PHE840MA6100MA04R17")
      (fields
        (field (name "MANUFACTURER") "Yageo")
        (field (name "MANUFACTURER PART NUMBER") "CC0603KPX7R9BB104")
      )
      (libsource (lib "Miscellaneous Devices") (part "Cap"))
    )
    (comp (ref "C96")
      (value "1uF")
      (footprint "SMD_C(0603)")
      (description "PHE840MA6100MA04R17")
      (fields
        (field (name "MANUFACTURER") "Yageo")
        (field (name "MANUFACTURER PART NUMBER") "CC0603KPX7R9BB104")
      )
      (libsource (lib "Miscellaneous Devices") (part "Cap"))
    )
    (comp (ref "C97")
      (value "1uF")
      (footprint "SMD_C(0603)")
      (description "PHE840MA6100MA04R17")
      (fields
        (field (name "MANUFACTURER") "Yageo")
        (field (name "MANUFACTURER PART NUMBER") "CC0603KPX7R9BB104")
      )
      (libsource (lib "Miscellaneous Devices") (part "Cap"))
    )
    (comp (ref "C98")
      (value "10uF")
      (footprint "SMD_C(0603)")
      (description "PHE840MA6100MA04R17")
      (fields
        (field (name "MANUFACTURER") "Yageo")
        (field (name "MANUFACTURER PART NUMBER") "CC0603KPX7R9BB104")
      )
      (libsource (lib "Miscellaneous Devices") (part "Cap"))
    )
    (comp (ref "C99")
      (value "0.1uF")
      (footprint "SMD_C(0402)")
      (description "PHE840MA6100MA04R17")
      (fields
        (field (name "MANUFACTURER") "Yageo")
        (field (name "MANUFACTURER PART NUMBER") "CC0603KPX7R9BB104")
      )
      (libsource (lib "Miscellaneous Devices") (part "Cap"))
    )
    (comp (ref "D1")
      (value "4301F1/5-A")
      (footprint "LED-DIP 3mm")
      (description "ledBicolor3mmRG_77")
      (libsource (lib "CameraBoard") (part "ledBicolor3mmRG_77"))
    )
    (comp (ref "D2")
      (value "HSDL-4220")
      (footprint "LED-DIP 5mm")
      (description "Typical RED GaAs LED")
      (fields (field (name "PUBLISHER") "Altium Limited"))
      (libsource (lib "WirelessCharger") (part "LED1"))
    )
    (comp (ref "D3")
      (value "HSDL-4220")
      (footprint "LED-DIP 5mm")
      (description "Typical RED GaAs LED")
      (fields (field (name "PUBLISHER") "Altium Limited"))
      (libsource (lib "WirelessCharger") (part "LED1"))
    )
    (comp (ref "D4")
      (value "Yellow")
      (footprint "SMD_LED(0603)")
      (description "Typical RED GaAs LED")
      (fields (field (name "PUBLISHER") "Altium Limited"))
      (libsource (lib "WirelessCharger") (part "LED1"))
    )
    (comp (ref "D5")
      (value "Green")
      (footprint "SMD_LED(0603)")
      (description "Typical RED GaAs LED")
      (fields (field (name "PUBLISHER") "Altium Limited"))
      (libsource (lib "WirelessCharger") (part "LED1"))
    )
    (comp (ref "D6")
      (value "SML-D12U1WT86")
      (footprint "SMD_LED(0603)")
      (description "Typical RED GaAs LED")
      (fields (field (name "PUBLISHER") "Altium Limited"))
      (libsource (lib "WirelessCharger") (part "LED1"))
    )
    (comp (ref "D7")
      (value "BLUE")
      (footprint "SMD_LED(0603)")
      (description "Typical BLUE GaAs LED")
      (fields (field (name "PUBLISHER") "Altium Limited"))
      (libsource (lib "WirelessCharger") (part "LED1"))
    )
    (comp (ref "D8")
      (value "SML-D12U1WT86")
      (footprint "SMD_LED(0603)")
      (description "Typical RED GaAs LED")
      (fields (field (name "PUBLISHER") "Altium Limited"))
      (libsource (lib "WirelessCharger") (part "LED1"))
    )
    (comp (ref "D9")
      (value "SML-D12U1WT86")
      (footprint "SMD_LED(0603)")
      (description "Typical RED GaAs LED")
      (fields (field (name "PUBLISHER") "Altium Limited"))
      (libsource (lib "WirelessCharger") (part "LED1"))
    )
    (comp (ref "FB1")
      (value "220R/100MHz")
      (footprint "SMD_R(0603)")
      (description "BLM18KG221SN1D Ferrite Bead(0603)")
      (fields (field (name "PUBLISHER") "Altium Limited"))
      (libsource (lib "") (part "Res2_1"))
    )
    (comp (ref "FB2")
      (value "220R/100MHz")
      (footprint "SMD_R(0603)")
      (description "BLM18KG221SN1D Ferrite Bead(0603)")
      (fields (field (name "PUBLISHER") "Altium Limited"))
      (libsource (lib "") (part "Res2_1"))
    )
    (comp (ref "FB3")
      (value "220R/100MHz")
      (footprint "SMD_R(0603)")
      (description "BLM18KG221SN1D Ferrite Bead(0603)")
      (fields (field (name "PUBLISHER") "Altium Limited"))
      (libsource (lib "") (part "Res2_1"))
    )
    (comp (ref "FB4")
      (value "220R/100MHz")
      (footprint "SMD_R(0603)")
      (description "BLM18KG221SN1D Ferrite Bead(0603)")
      (fields (field (name "PUBLISHER") "Altium Limited"))
      (libsource (lib "") (part "Res2_1"))
    )
    (comp (ref "FB5")
      (value "220R/100MHz")
      (footprint "SMD_R(0603)")
      (description "BLM18KG221SN1D Ferrite Bead(0603)")
      (fields (field (name "PUBLISHER") "Altium Limited"))
      (libsource (lib "") (part "Res2_1"))
    )
    (comp (ref "FB6")
      (value "220R/100MHz")
      (footprint "SMD_R(0603)")
      (description "BLM18KG221SN1D Ferrite Bead(0603)")
      (fields (field (name "PUBLISHER") "Altium Limited"))
      (libsource (lib "") (part "Res2_1"))
    )
    (comp (ref "FB7")
      (value "220R/100MHz")
      (footprint "SMD_R(0603)")
      (description "BLM18KG221SN1D Ferrite Bead(0603)")
      (fields (field (name "PUBLISHER") "Altium Limited"))
      (libsource (lib "") (part "Res2_1"))
    )
    (comp (ref "FB8")
      (value "220R/100MHz")
      (footprint "SMD_R(0603)")
      (description "BLM18KG221SN1D Ferrite Bead(0603)")
      (fields (field (name "PUBLISHER") "Altium Limited"))
      (libsource (lib "Miscellaneous Devices") (part "Res2"))
    )
    (comp (ref "FB9")
      (value "220R/100MHz")
      (footprint "SMD_R(0603)")
      (description "BLM18KG221SN1D Ferrite Bead(0603)")
      (fields (field (name "PUBLISHER") "Altium Limited"))
      (libsource (lib "") (part "Res2_1"))
    )
    (comp (ref "FB10")
      (value "220R/100MHz")
      (footprint "SMD_R(0603)")
      (description "BLM18KG221SN1D Ferrite Bead(0603)")
      (fields (field (name "PUBLISHER") "Altium Limited"))
      (libsource (lib "") (part "Res2_1"))
    )
    (comp (ref "FB11")
      (value "220R/100MHz")
      (footprint "SMD_R(0603)")
      (description "BLM18KG221SN1D Ferrite Bead(0603)")
      (fields (field (name "PUBLISHER") "Altium Limited"))
      (libsource (lib "") (part "Res2_1"))
    )
    (comp (ref "FB12")
      (value "220R/100MHz")
      (footprint "SMD_R(0603)")
      (description "BLM18KG221SN1D Ferrite Bead(0603)")
      (fields (field (name "PUBLISHER") "Altium Limited"))
      (libsource (lib "") (part "Res2_1"))
    )
    (comp (ref "FB13")
      (value "220R/100MHz")
      (footprint "SMD_R(0603)")
      (description "BLM18KG221SN1D Ferrite Bead(0603)")
      (fields (field (name "PUBLISHER") "Altium Limited"))
      (libsource (lib "") (part "Res2_1"))
    )
    (comp (ref "FB14")
      (value "220R/100MHz")
      (footprint "SMD_R(0603)")
      (description "BLM18KG221SN1D Ferrite Bead(0603)")
      (fields (field (name "PUBLISHER") "Altium Limited"))
      (libsource (lib "") (part "Res2_1"))
    )
    (comp (ref "FB15")
      (value "220R/100MHz")
      (footprint "SMD_R(0603)")
      (description "BLM18KG221SN1D Ferrite Bead(0603)")
      (fields (field (name "PUBLISHER") "Altium Limited"))
      (libsource (lib "") (part "Res2_1"))
    )
    (comp (ref "J1")
      (value "10118194-0001LF")
      (footprint "10118194-0001LF")
      (description "CONN RCPT USB2.0 MICRO B SMD R/A")
      (fields (field (name "MANUFACTURER") "Amphenol FCI"))
      (libsource (lib "LED_LIB") (part "10118194-0001LF"))
    )
    (comp (ref "J2")
      (value "2 Pin Connector")
      (footprint "JST_S2B-PH-SM4-TB(LF)(SN)")
      (description "JST_S2B-PH-SM4-TB(LF)(SN)")
      (libsource (lib "WirelessCharger") (part "2PinConnector"))
    )
    (comp (ref "J3")
      (value "PJ-320A")
      (footprint "AUDIO-TH_PJ-320A")
      (description "Connector, 3.5mm Stereo Audio Socket, Black")
      (libsource (lib "WirelessCharger") (part "PJ-320A"))
    )
    (comp (ref "J4")
      (value "78646-3001")
      (footprint "78646-3001")
      (description "CN SimCard_63")
      (libsource (lib "CameraBoard") (part "CN SimCard_63"))
    )
    (comp (ref "J5")
      (value "FFC2B28-24-G")
      (footprint "FCI_10051922-3010ELF")
      (description "UC7675-A66 connector")
      (fields (field (name "MF") "Global Connector Technology"))
      (libsource (lib "SnapEDAsch") (part "FFC2B28-24-G"))
    )
    (comp (ref "J6")
      (value "SWD")
      (footprint "Header-2.54m-4pin")
      (description "4PinConnector")
      (libsource (lib "") (part "4PinConnector_1"))
    )
    (comp (ref "J7")
      (value "2*2 Pin Header")
      (footprint "Header-2.54m-2*2pin")
      (libsource (lib "WirelessCharger") (part "2*2 Pin Header"))
    )
    (comp (ref "J8")
      (value "microSD")
      (footprint "*MOLEX_47352-1001_47352-1001(Primary)")
      (description "SD CARD SOCKET")
      (fields (field (name "PUBLISHER") "Altium Limited"))
      (libsource (lib "WirelessCharger") (part "SD CARD SOCKET_1"))
    )
    (comp (ref "J9")
      (value "Nu-Link Interface")
      (footprint "Header-2.54m-5pin")
      (description "5PinConnector")
      (libsource (lib "WirelessCharger") (part "5PinConnector"))
    )
    (comp (ref "J10")
      (value "UART_Debug")
      (footprint "Header-2.54m-4pin")
      (description "4PinConnector")
      (libsource (lib "WirelessCharger") (part "4PinConnector"))
    )
    (comp (ref "L1")
      (value "SRN4018TA-1R5M")
      (footprint "IND_SRN4018TA-1R5M")
      (fields (field (name "PUBLISHER") "Altium Limited"))
      (libsource (lib "WirelessCharger") (part "Inductor"))
    )
    (comp (ref "L2")
      (value "LQH32PN2R2NNCL")
      (footprint "IND_LQH32PN2R2NNCL")
      (description "744771004")
      (fields (field (name "PUBLISHER") "Altium Limited"))
      (libsource (lib "WirelessCharger") (part "Inductor"))
    )
    (comp (ref "L3")
      (value "3.3nH")
      (footprint "SMD_R(0603)")
      (description "744771004")
      (fields (field (name "PUBLISHER") "Altium Limited"))
      (libsource (lib "WirelessCharger") (part "Inductor"))
    )
    (comp (ref "L4")
      (value "6.8nH")
      (footprint "SMD_R(0603)")
      (description "744771004")
      (fields (field (name "PUBLISHER") "Altium Limited"))
      (libsource (lib "WirelessCharger") (part "Inductor"))
    )
    (comp (ref "L8")
      (value "0R")
      (footprint "SMD_R(0402)")
      (description "744771004")
      (fields (field (name "PUBLISHER") "Altium Limited"))
      (libsource (lib "WirelessCharger") (part "Inductor"))
    )
    (comp (ref "LDR1")
      (value "PDV-P8104")
      (footprint "PHODET_PDV-P8103")
      (description "Variable Resistor")
      (fields (field (name "PUBLISHER") "Altium Limited"))
      (libsource (lib "Miscellaneous Devices") (part "Res Adj1"))
    )
    (comp (ref "MIC1")
      (value "CMEJ-0627-42-P")
      (footprint "MIC_CMEJ-0627-42-P")
      (description "MICPHONE_80")
      (libsource (lib "CameraBoard") (part "MICPHONE_80"))
    )
    (comp (ref "Q1")
      (value "BC847CLT1G")
      (footprint "SOT23-3")
      (description "NPN General Purpose Amplifier")
      (fields (field (name "PUBLISHER") "Altium Limited"))
      (libsource (lib "Wemo_Board") (part "2N3904"))
    )
    (comp (ref "Q2")
      (value "BC847CLT1G")
      (footprint "SOT23-3")
      (description "NPN General Purpose Amplifier")
      (fields (field (name "PUBLISHER") "Altium Limited"))
      (libsource (lib "Wemo_Board") (part "2N3904"))
    )
    (comp (ref "Q3")
      (value "BC847CLT1G")
      (footprint "SOT23-3")
      (description "NPN General Purpose Amplifier")
      (fields (field (name "PUBLISHER") "Altium Limited"))
      (libsource (lib "Wemo_Board") (part "2N3904"))
    )
    (comp (ref "Q4")
      (value "BC847CLT1G")
      (footprint "SOT23-3")
      (description "NPN General Purpose Amplifier")
      (fields (field (name "PUBLISHER") "Altium Limited"))
      (libsource (lib "Wemo_Board") (part "2N3904"))
    )
    (comp (ref "Q5")
      (value "BC847CLT1G")
      (footprint "SOT23-3")
      (description "NPN General Purpose Amplifier")
      (fields (field (name "PUBLISHER") "Altium Limited"))
      (libsource (lib "Wemo_Board") (part "2N3904"))
    )
    (comp (ref "Q6")
      (value "BC847CLT1G")
      (footprint "SOT23-3")
      (description "NPN General Purpose Amplifier")
      (fields (field (name "PUBLISHER") "Altium Limited"))
      (libsource (lib "Wemo_Board") (part "2N3904"))
    )
    (comp (ref "R1")
      (value "10k")
      (footprint "SMD_R(0402)")
      (description "CRCW04024R02FKED")
      (fields (field (name "PUBLISHER") "Altium Limited"))
      (libsource (lib "Miscellaneous Devices") (part "Res Semi"))
    )
    (comp (ref "R2")
      (value "10k")
      (footprint "SMD_R(0402)")
      (description "CRCW04024R02FKED")
      (fields (field (name "PUBLISHER") "Altium Limited"))
      (libsource (lib "Miscellaneous Devices") (part "Res Semi"))
    )
    (comp (ref "R3")
      (value "374k")
      (footprint "SMD_R(0402)")
      (description "CRCW04024R02FKED")
      (fields (field (name "PUBLISHER") "Altium Limited"))
      (libsource (lib "Miscellaneous Devices") (part "Res Semi"))
    )
    (comp (ref "R4")
      (value "56k")
      (footprint "SMD_R(0402)")
      (description "CRCW04024R02FKED")
      (fields (field (name "PUBLISHER") "Altium Limited"))
      (libsource (lib "Miscellaneous Devices") (part "Res Semi"))
    )
    (comp (ref "R5")
      (value "10k")
      (footprint "SMD_R(0402)")
      (description "CRCW04024R02FKED")
      (fields (field (name "PUBLISHER") "Altium Limited"))
      (libsource (lib "Miscellaneous Devices") (part "Res Semi"))
    )
    (comp (ref "R6")
      (value "3.3k")
      (footprint "SMD_R(0402)")
      (description "CRCW04024R02FKED")
      (fields (field (name "PUBLISHER") "Altium Limited"))
      (libsource (lib "Miscellaneous Devices") (part "Res Semi"))
    )
    (comp (ref "R7")
      (value "2.2k")
      (footprint "SMD_R(0402)")
      (description "CRCW04024R02FKED")
      (fields (field (name "PUBLISHER") "Altium Limited"))
      (libsource (lib "Miscellaneous Devices") (part "Res Semi"))
    )
    (comp (ref "R8")
      (value "47k")
      (footprint "SMD_R(0402)")
      (description "CRCW04024R02FKED")
      (fields (field (name "PUBLISHER") "Altium Limited"))
      (libsource (lib "Miscellaneous Devices") (part "Res Semi"))
    )
    (comp (ref "R9")
      (value "2.2k")
      (footprint "SMD_R(0402)")
      (description "CRCW04024R02FKED")
      (fields (field (name "PUBLISHER") "Altium Limited"))
      (libsource (lib "Miscellaneous Devices") (part "Res Semi"))
    )
    (comp (ref "R10")
      (value "2.2k")
      (footprint "SMD_R(0402)")
      (description "CRCW04024R02FKED")
      (fields (field (name "PUBLISHER") "Altium Limited"))
      (libsource (lib "Miscellaneous Devices") (part "Res Semi"))
    )
    (comp (ref "R11")
      (value "10k")
      (footprint "SMD_R(0402)")
      (description "CRCW04024R02FKED")
      (fields (field (name "PUBLISHER") "Altium Limited"))
      (libsource (lib "Miscellaneous Devices") (part "Res Semi"))
    )
    (comp (ref "R12")
      (value "22R")
      (footprint "SMD_R(0402)")
      (description "CRCW04024R02FKED")
      (fields (field (name "PUBLISHER") "Altium Limited"))
      (libsource (lib "Miscellaneous Devices") (part "Res Semi"))
    )
    (comp (ref "R13")
      (value "22R")
      (footprint "SMD_R(0402)")
      (description "CRCW04024R02FKED")
      (fields (field (name "PUBLISHER") "Altium Limited"))
      (libsource (lib "Miscellaneous Devices") (part "Res Semi"))
    )
    (comp (ref "R14")
      (value "1k")
      (footprint "SMD_R(0402)")
      (description "CRCW04024R02FKED")
      (fields (field (name "PUBLISHER") "Altium Limited"))
      (libsource (lib "Miscellaneous Devices") (part "Res Semi"))
    )
    (comp (ref "R15")
      (value "330R")
      (footprint "SMD_R(0402)")
      (description "CRCW04024R02FKED")
      (fields (field (name "PUBLISHER") "Altium Limited"))
      (libsource (lib "Miscellaneous Devices") (part "Res Semi"))
    )
    (comp (ref "R16")
      (value "10k")
      (footprint "SMD_R(0402)")
      (description "CRCW04024R02FKED")
      (fields (field (name "PUBLISHER") "Altium Limited"))
      (libsource (lib "Miscellaneous Devices") (part "Res Semi"))
    )
    (comp (ref "R17")
      (value "10k")
      (footprint "SMD_R(0402)")
      (description "CRCW04024R02FKED")
      (fields (field (name "PUBLISHER") "Altium Limited"))
      (libsource (lib "Miscellaneous Devices") (part "Res Semi"))
    )
    (comp (ref "R18")
      (value "3R/0.25W")
      (footprint "SMD_R(0603)")
      (description "CRCW04024R02FKED")
      (fields (field (name "PUBLISHER") "Altium Limited"))
      (libsource (lib "Miscellaneous Devices") (part "Res Semi"))
    )
    (comp (ref "R19")
      (value "47k")
      (footprint "SMD_R(0402)")
      (description "CRCW04024R02FKED")
      (fields (field (name "PUBLISHER") "Altium Limited"))
      (libsource (lib "Miscellaneous Devices") (part "Res Semi"))
    )
    (comp (ref "R20")
      (value "10k")
      (footprint "SMD_R(0402)")
      (description "AC0402FR-0710KL")
      (fields (field (name "PUBLISHER") "Altium Limited"))
      (libsource (lib "") (part "Res Semi_1"))
    )
    (comp (ref "R21")
      (value "1k")
      (footprint "SMD_R(0402)")
      (description "CRCW04024R02FKED")
      (fields (field (name "PUBLISHER") "Altium Limited"))
      (libsource (lib "Miscellaneous Devices") (part "Res Semi"))
    )
    (comp (ref "R22")
      (value "22R")
      (footprint "SMD_R(0402)")
      (description "CRCW04024R02FKED")
      (fields (field (name "PUBLISHER") "Altium Limited"))
      (libsource (lib "Miscellaneous Devices") (part "Res Semi"))
    )
    (comp (ref "R23")
      (value "22R")
      (footprint "SMD_R(0402)")
      (description "CRCW04024R02FKED")
      (fields (field (name "PUBLISHER") "Altium Limited"))
      (libsource (lib "Miscellaneous Devices") (part "Res Semi"))
    )
    (comp (ref "R24")
      (value "10k")
      (footprint "SMD_R(0402)")
      (description "CRCW04024R02FKED")
      (fields (field (name "PUBLISHER") "Altium Limited"))
      (libsource (lib "Miscellaneous Devices") (part "Res Semi"))
    )
    (comp (ref "R25")
      (value "22R")
      (footprint "SMD_R(0402)")
      (description "CRCW04024R02FKED")
      (fields (field (name "PUBLISHER") "Altium Limited"))
      (libsource (lib "Miscellaneous Devices") (part "Res Semi"))
    )
    (comp (ref "R26")
      (value "47k")
      (footprint "SMD_R(0402)")
      (description "CRCW04024R02FKED")
      (fields (field (name "PUBLISHER") "Altium Limited"))
      (libsource (lib "Miscellaneous Devices") (part "Res Semi"))
    )
    (comp (ref "R27")
      (value "10k")
      (footprint "SMD_R(0402)")
      (description "CRCW04024R02FKED")
      (fields (field (name "PUBLISHER") "Altium Limited"))
      (libsource (lib "Miscellaneous Devices") (part "Res Semi"))
    )
    (comp (ref "R28")
      (value "1k")
      (footprint "SMD_R(0402)")
      (description "CRCW04024R02FKED")
      (fields (field (name "PUBLISHER") "Altium Limited"))
      (libsource (lib "Miscellaneous Devices") (part "Res Semi"))
    )
    (comp (ref "R29")
      (value "1k")
      (footprint "SMD_R(0402)")
      (description "CRCW04024R02FKED")
      (fields (field (name "PUBLISHER") "Altium Limited"))
      (libsource (lib "Miscellaneous Devices") (part "Res Semi"))
    )
    (comp (ref "R30")
      (value "1k")
      (footprint "SMD_R(0402)")
      (description "CRCW04024R02FKED")
      (fields (field (name "PUBLISHER") "Altium Limited"))
      (libsource (lib "Miscellaneous Devices") (part "Res Semi"))
    )
    (comp (ref "R31")
      (value "10k")
      (footprint "SMD_R(0402)")
      (description "CRCW04024R02FKED")
      (fields (field (name "PUBLISHER") "Altium Limited"))
      (libsource (lib "Miscellaneous Devices") (part "Res Semi"))
    )
    (comp (ref "R32")
      (value "1k")
      (footprint "SMD_R(0402)")
      (description "CRCW04024R02FKED")
      (fields (field (name "PUBLISHER") "Altium Limited"))
      (libsource (lib "Miscellaneous Devices") (part "Res Semi"))
    )
    (comp (ref "R33")
      (value "1k")
      (footprint "SMD_R(0402)")
      (description "CRCW04024R02FKED")
      (fields (field (name "PUBLISHER") "Altium Limited"))
      (libsource (lib "Miscellaneous Devices") (part "Res Semi"))
    )
    (comp (ref "R34")
      (value "10k")
      (footprint "SMD_R(0402)")
      (description "CRCW04024R02FKED")
      (fields (field (name "PUBLISHER") "Altium Limited"))
      (libsource (lib "Miscellaneous Devices") (part "Res Semi"))
    )
    (comp (ref "R35")
      (value "10k")
      (footprint "SMD_R(0402)")
      (description "CRCW04024R02FKED")
      (fields (field (name "PUBLISHER") "Altium Limited"))
      (libsource (lib "Miscellaneous Devices") (part "Res Semi"))
    )
    (comp (ref "R36")
      (value "1k")
      (footprint "SMD_R(0402)")
      (description "CRCW04024R02FKED")
      (fields (field (name "PUBLISHER") "Altium Limited"))
      (libsource (lib "Miscellaneous Devices") (part "Res Semi"))
    )
    (comp (ref "R37")
      (value "10k")
      (footprint "SMD_R(0402)")
      (description "CRCW04024R02FKED")
      (fields (field (name "PUBLISHER") "Altium Limited"))
      (libsource (lib "Miscellaneous Devices") (part "Res Semi"))
    )
    (comp (ref "R38")
      (value "10k")
      (footprint "SMD_R(0402)")
      (description "CRCW04024R02FKED")
      (fields (field (name "PUBLISHER") "Altium Limited"))
      (libsource (lib "Miscellaneous Devices") (part "Res Semi"))
    )
    (comp (ref "R39")
      (value "10k")
      (footprint "SMD_R(0402)")
      (description "CRCW04024R02FKED")
      (fields (field (name "PUBLISHER") "Altium Limited"))
      (libsource (lib "Miscellaneous Devices") (part "Res Semi"))
    )
    (comp (ref "R40")
      (value "330R")
      (footprint "SMD_R(0402)")
      (description "CRCW04024R02FKED")
      (fields (field (name "PUBLISHER") "Altium Limited"))
      (libsource (lib "Miscellaneous Devices") (part "Res Semi"))
    )
    (comp (ref "R41")
      (value "330R")
      (footprint "SMD_R(0402)")
      (description "CRCW04024R02FKED")
      (fields (field (name "PUBLISHER") "Altium Limited"))
      (libsource (lib "Miscellaneous Devices") (part "Res Semi"))
    )
    (comp (ref "R42")
      (value "2.2k")
      (footprint "SMD_R(0402)")
      (description "CRCW04024R02FKED")
      (fields (field (name "PUBLISHER") "Altium Limited"))
      (libsource (lib "Miscellaneous Devices") (part "Res Semi"))
    )
    (comp (ref "R43")
      (value "0R")
      (footprint "SMD_R(0402)")
      (description "CRCW04024R02FKED")
      (fields (field (name "PUBLISHER") "Altium Limited"))
      (libsource (lib "Miscellaneous Devices") (part "Res Semi"))
    )
    (comp (ref "R44")
      (value "2.2k")
      (footprint "SMD_R(0402)")
      (description "CRCW04024R02FKED")
      (fields (field (name "PUBLISHER") "Altium Limited"))
      (libsource (lib "Miscellaneous Devices") (part "Res Semi"))
    )
    (comp (ref "R45")
      (value "330R")
      (footprint "SMD_R(0402)")
      (description "CRCW04024R02FKED")
      (fields (field (name "PUBLISHER") "Altium Limited"))
      (libsource (lib "Miscellaneous Devices") (part "Res Semi"))
    )
    (comp (ref "R46")
      (value "10k")
      (footprint "SMD_R(0402)")
      (description "CRCW04024R02FKED")
      (fields (field (name "PUBLISHER") "Altium Limited"))
      (libsource (lib "Miscellaneous Devices") (part "Res Semi"))
    )
    (comp (ref "R47")
      (value "33k")
      (footprint "SMD_R(0402)")
      (description "CRCW04024R02FKED")
      (fields (field (name "PUBLISHER") "Altium Limited"))
      (libsource (lib "Miscellaneous Devices") (part "Res Semi"))
    )
    (comp (ref "R48")
      (value "33k")
      (footprint "SMD_R(0402)")
      (description "CRCW04024R02FKED")
      (fields (field (name "PUBLISHER") "Altium Limited"))
      (libsource (lib "Miscellaneous Devices") (part "Res Semi"))
    )
    (comp (ref "R49")
      (value "33k")
      (footprint "SMD_R(0402)")
      (description "CRCW04024R02FKED")
      (fields (field (name "PUBLISHER") "Altium Limited"))
      (libsource (lib "Miscellaneous Devices") (part "Res Semi"))
    )
    (comp (ref "R50")
      (value "33k")
      (footprint "SMD_R(0402)")
      (description "CRCW04024R02FKED")
      (fields (field (name "PUBLISHER") "Altium Limited"))
      (libsource (lib "Miscellaneous Devices") (part "Res Semi"))
    )
    (comp (ref "R51")
      (value "33k")
      (footprint "SMD_R(0402)")
      (description "CRCW04024R02FKED")
      (fields (field (name "PUBLISHER") "Altium Limited"))
      (libsource (lib "Miscellaneous Devices") (part "Res Semi"))
    )
    (comp (ref "R52")
      (value "33k")
      (footprint "SMD_R(0402)")
      (description "CRCW04024R02FKED")
      (fields (field (name "PUBLISHER") "Altium Limited"))
      (libsource (lib "Miscellaneous Devices") (part "Res Semi"))
    )
    (comp (ref "R53")
      (value "1k")
      (footprint "SMD_R(0402)")
      (description "CRCW04024R02FKED")
      (fields (field (name "PUBLISHER") "Altium Limited"))
      (libsource (lib "Miscellaneous Devices") (part "Res Semi"))
    )
    (comp (ref "R54")
      (value "1k")
      (footprint "SMD_R(0402)")
      (description "CRCW04024R02FKED")
      (fields (field (name "PUBLISHER") "Altium Limited"))
      (libsource (lib "Miscellaneous Devices") (part "Res Semi"))
    )
    (comp (ref "R55")
      (value "330R")
      (footprint "SMD_R(0402)")
      (description "CRCW04024R02FKED")
      (fields (field (name "PUBLISHER") "Altium Limited"))
      (libsource (lib "Miscellaneous Devices") (part "Res Semi"))
    )
    (comp (ref "R56")
      (value "1k")
      (footprint "SMD_R(0402)")
      (description "CRCW04024R02FKED")
      (fields (field (name "PUBLISHER") "Altium Limited"))
      (libsource (lib "Miscellaneous Devices") (part "Res Semi"))
    )
    (comp (ref "R57")
      (value "10k")
      (footprint "SMD_R(0402)")
      (description "CRCW04024R02FKED")
      (fields (field (name "PUBLISHER") "Altium Limited"))
      (libsource (lib "Miscellaneous Devices") (part "Res Semi"))
    )
    (comp (ref "SP1")
      (value "SPEAKER 10mm_193")
      (footprint "Header-2.54m-2pin")
      (libsource (lib "CameraBoard") (part "SPEAKER 10mm_193"))
    )
    (comp (ref "SW1")
      (value "1825966-1")
      (footprint "SW_1825966-1")
      (description "Switch")
      (fields (field (name "PUBLISHER") "Altium Limited"))
      (libsource (lib "Miscellaneous Devices") (part "SW-PB"))
    )
    (comp (ref "U1")
      (value "TPS62291DRVR")
      (footprint "SON65P200X200X80-7N")
      (description "2.25MHz 1A Step-Down Converter in 2x2mm SON Package 6-WSON -40 to 85")
      (fields (field (name "MF") "Texas Instruments"))
      (libsource (lib "TPS62291DRVR") (part "TPS62291DRVR"))
    )
    (comp (ref "U2")
      (value "BQ24230RGTT")
      (footprint "VQFN-17N")
      (description "BQ24230_200")
      (libsource (lib "CameraBoard") (part "BQ24230_200"))
    )
    (comp (ref "U3") (value "TPS63020") (footprint "TPS63020") (libsource (lib "Schlib1") (part "TPS63020")))
    (comp (ref "U4")
      (value "MAX9860ETG+")
      (footprint "QFN50P400X400X75-25N")
      (description "Audio Interface 16 b Serial 24-TQFN _4x4_")
      (fields (field (name "DIGI-KEY_PART_NUMBER") "MAX9860ETG+-ND") (field (name "MF") "Maxim Integrated"))
      (libsource (lib "WirelessCharger") (part "MAX9860ETG+"))
    )
    (comp (ref "U5")
      (value "AP2125K-1.8TRG1")
      (footprint "SOT23-5")
      (description "IC REG LINEAR 2.8V 300MA SOT23-5")
      (libsource (lib "WirelessCharger") (part "AP2125K-2.8TRG1"))
    )
    (comp (ref "U6")
      (value "STM32F407VGT6")
      (footprint "LQFP-100N")
      (description "ARMÂ® CortexÂ®-M4 STM32F4 Microcontroller IC 32-Bit 168MHz 1MB _1M x 8_ FLASH 100-LQFP _14x14_")
      (fields (field (name "MF") "STMicroelectronics"))
      (libsource (lib "WirelessCharger") (part "STM32F407VGT6"))
    )
    (comp (ref "U7")
      (value "TXB0106PWR")
      (footprint "TSSOP-16N")
      (fields (field (name "MF") "Texas Instruments"))
      (libsource (lib "WirelessCharger") (part "TXB0106PWR"))
    )
    (comp (ref "U8")
      (value "TOBYL20002S_202")
      (footprint "TOBYL20002S_TOBYL20002S(Primary)")
      (libsource (lib "CameraBoard") (part "TOBYL20002S_202"))
    )
    (comp (ref "U9")
      (value "TXB0106PWR")
      (footprint "TSSOP-16N")
      (fields (field (name "MF") "Texas Instruments"))
      (libsource (lib "WirelessCharger") (part "TXB0106PWR"))
    )
    (comp (ref "U10")
      (value "SMF05CT1G")
      (footprint "SOT-363")
      (description "12.5V Clamp 8A _8/20Âµs_ Ipp Tvs Diode Surface Mount SC-88/SC70-6/SOT-363")
      (fields (field (name "DIGI-KEY_PART_NUMBER") "SMF05CT1GOSCT-ND") (field (name "MF") "ON Semiconductor"))
      (libsource (lib "SnapEDAsch") (part "SMF05CT1G"))
    )
    (comp (ref "U11")
      (value "AP2125K-2.8TRG1")
      (footprint "SOT23-5")
      (description "IC REG LINEAR 2.8V 300MA SOT23-5")
      (libsource (lib "WirelessCharger") (part "AP2125K-2.8TRG1"))
    )
    (comp (ref "U12")
      (value "AP2125K-1.8TRG1")
      (footprint "SOT23-5")
      (description "IC REG LINEAR 2.8V 300MA SOT23-5")
      (libsource (lib "WirelessCharger") (part "AP2125K-2.8TRG1"))
    )
    (comp (ref "U13")
      (value "CAM-M8C")
      (footprint "CAM-M8C_LCC-31N")
      (description "CAM-M8C_79")
      (libsource (lib "CameraBoard") (part "CAM-M8C_79"))
    )
    (comp (ref "U14")
      (value "ISD9160")
      (footprint "LQFP-48N")
      (libsource (lib "template") (part "MCU-ISD9160"))
    )
    (comp (ref "U15")
      (value "ZPT-4RS")
      (footprint "ZPT-4RS")
      (description "RF RECEIVER 433MHZ MODULE")
      (libsource (lib "WirelessCharger") (part "ZPT-4RS"))
    )
    (comp (ref "U16")
      (value "W25X40CLSNIG")
      (footprint "SOIC-8N")
      (description "1M-BIT,2M-BIT,4M-BIT AND 8M-BIT SERIAL FLASH MEMORY WITH 4KB SECTORS AND DUAL OUTPUT SPI")
      (libsource (lib "IC-new") (part "FLASH-W25X80"))
    )
    (comp (ref "Y1")
      (value "8MHz")
      (footprint "Resonator_mini")
      (description "Crystal Oscillator")
      (fields (field (name "PUBLISHER") "Altium Limited"))
      (libsource (lib "MySchLib") (part "XTAL"))
    )
    (comp (ref "Y2")
      (value "32.768kHz")
      (footprint "TC26H_3_REPAIR_SMD")
      (description "TFSM262P32K7680")
      (fields (field (name "PUBLISHER") "Altium Limited"))
      (libsource (lib "SolarEnabledPowerBank_1") (part "XTAL"))
    )
  )
  (nets
    (net (code "1") (name "/ATN1") (class "Default")
      (node (ref "L3") (pin "1") (pinfunction "1_1") (pintype "passive"))
      (node (ref "U8") (pin "81") (pinfunction "81_81") (pintype "passive"))
    )
    (net (code "2") (name "/ATN2") (class "Default")
      (node (ref "U8") (pin "87") (pinfunction "87_87") (pintype "passive"))
    )
    (net (code "3") (name "/Audio_EN") (class "Default")
      (node (ref "U5") (pin "3") (pinfunction "CE_3") (pintype "passive"))
      (node (ref "U6") (pin "79") (pinfunction "PC11_79") (pintype "bidirectional"))
    )
    (net (code "4") (name "/BOOT0") (class "Default")
      (node (ref "R38") (pin "2") (pinfunction "2_2") (pintype "passive"))
      (node (ref "R41") (pin "1") (pinfunction "1_1") (pintype "passive"))
      (node (ref "U6") (pin "94") (pinfunction "BOOT0_94") (pintype "input"))
    )
    (net (code "5") (name "/BOOT1") (class "Default")
      (node (ref "R39") (pin "2") (pinfunction "2_2") (pintype "passive"))
      (node (ref "R40") (pin "1") (pinfunction "1_1") (pintype "passive"))
      (node (ref "U6") (pin "37") (pinfunction "PB2_37") (pintype "bidirectional"))
    )
    (net (code "6") (name "/CAM_D0") (class "Default")
      (node (ref "J5") (pin "19") (pinfunction "19_19") (pintype "passive"))
      (node (ref "U6") (pin "63") (pinfunction "PC6_63") (pintype "bidirectional"))
    )
    (net (code "7") (name "/CAM_D1") (class "Default")
      (node (ref "J5") (pin "21") (pinfunction "21_21") (pintype "passive"))
      (node (ref "U6") (pin "64") (pinfunction "PC7_64") (pintype "bidirectional"))
    )
    (net (code "8") (name "/CAM_D2") (class "Default")
      (node (ref "J5") (pin "22") (pinfunction "22_22") (pintype "passive"))
      (node (ref "U6") (pin "65") (pinfunction "PC8_65") (pintype "bidirectional"))
    )
    (net (code "9") (name "/CAM_D3") (class "Default")
      (node (ref "J5") (pin "20") (pinfunction "20_20") (pintype "passive"))
      (node (ref "U6") (pin "66") (pinfunction "PC9_66") (pintype "bidirectional"))
    )
    (net (code "10") (name "/CAM_D4") (class "Default")
      (node (ref "J5") (pin "18") (pinfunction "18_18") (pintype "passive"))
      (node (ref "U6") (pin "3") (pinfunction "PE4_3") (pintype "bidirectional"))
    )
    (net (code "11") (name "/CAM_D5") (class "Default")
      (node (ref "J5") (pin "16") (pinfunction "16_16") (pintype "passive"))
      (node (ref "U6") (pin "92") (pinfunction "PB6_92") (pintype "bidirectional"))
    )
    (net (code "12") (name "/CAM_D6") (class "Default")
      (node (ref "J5") (pin "14") (pinfunction "14_14") (pintype "passive"))
      (node (ref "U6") (pin "4") (pinfunction "PE5_4") (pintype "bidirectional"))
    )
    (net (code "13") (name "/CAM_D7") (class "Default")
      (node (ref "J5") (pin "12") (pinfunction "12_12") (pintype "passive"))
      (node (ref "U6") (pin "5") (pinfunction "PE6_5") (pintype "bidirectional"))
    )
    (net (code "14") (name "/CAM_EN") (class "Default")
      (node (ref "U11") (pin "3") (pinfunction "CE_3") (pintype "passive"))
      (node (ref "U12") (pin "3") (pinfunction "CE_3") (pintype "passive"))
      (node (ref "U6") (pin "89") (pinfunction "PB3_89") (pintype "bidirectional"))
    )
    (net (code "15") (name "/CAM_HSYNC") (class "Default")
      (node (ref "J5") (pin "9") (pinfunction "9_9") (pintype "passive"))
      (node (ref "U6") (pin "29") (pinfunction "PA4_29") (pintype "bidirectional"))
    )
    (net (code "16") (name "/CAM_PCLK") (class "Default")
      (node (ref "J5") (pin "17") (pinfunction "17_17") (pintype "passive"))
      (node (ref "U6") (pin "31") (pinfunction "PA6_31") (pintype "bidirectional"))
    )
    (net (code "17") (name "/CAM_PWDN") (class "Default")
      (node (ref "J5") (pin "8") (pinfunction "8_8") (pintype "passive"))
      (node (ref "U6") (pin "88") (pinfunction "PD7_88") (pintype "bidirectional"))
    )
    (net (code "18") (name "/CAM_SCL") (class "Default")
      (node (ref "J5") (pin "5") (pinfunction "5_5") (pintype "passive"))
      (node (ref "U6") (pin "47") (pinfunction "PB10_47") (pintype "bidirectional"))
    )
    (net (code "19") (name "/CAM_SDA") (class "Default")
      (node (ref "J5") (pin "3") (pinfunction "3_3") (pintype "passive"))
      (node (ref "U6") (pin "48") (pinfunction "PB11_48") (pintype "bidirectional"))
    )
    (net (code "20") (name "/CAM_VSYNC") (class "Default")
      (node (ref "J5") (pin "7") (pinfunction "7_7") (pintype "passive"))
      (node (ref "U6") (pin "93") (pinfunction "PB7_93") (pintype "bidirectional"))
    )
    (net (code "21") (name "/CAM_XCLK") (class "Default")
      (node (ref "J5") (pin "13") (pinfunction "13_13") (pintype "passive"))
      (node (ref "U6") (pin "67") (pinfunction "PA8_67") (pintype "bidirectional"))
    )
    (net (code "22") (name "/CHG") (class "Default")
      (node (ref "R2") (pin "2") (pinfunction "2_2") (pintype "passive"))
      (node (ref "U2") (pin "9") (pinfunction "9_9") (pintype "passive"))
      (node (ref "U6") (pin "43") (pinfunction "PE12_43") (pintype "bidirectional"))
    )
    (net (code "23") (name "/CODEC_CLK") (class "Default")
      (node (ref "C36") (pin "2") (pinfunction "2_2") (pintype "passive"))
      (node (ref "R13") (pin "1") (pinfunction "1_1") (pintype "passive"))
      (node (ref "U8") (pin "61") (pinfunction "61_61") (pintype "passive"))
    )
    (net (code "24") (name "/EAR+") (class "Default")
      (node (ref "C12") (pin "2") (pinfunction "2_2") (pintype "passive"))
      (node (ref "C13") (pin "2") (pinfunction "2_2") (pintype "passive"))
      (node (ref "C15") (pin "1") (pinfunction "1_1") (pintype "passive"))
      (node (ref "C16") (pin "1") (pinfunction "1_1") (pintype "passive"))
      (node (ref "C40") (pin "1") (pinfunction "1_1") (pintype "passive"))
    )
    (net (code "25") (name "/GPS_CS") (class "Default")
      (node (ref "U13") (pin "3") (pinfunction "3_3") (pintype "passive"))
      (node (ref "U6") (pin "51") (pinfunction "PB12_51") (pintype "bidirectional"))
    )
    (net (code "26") (name "/GPS_MISO") (class "Default")
      (node (ref "U13") (pin "25") (pinfunction "25_25") (pintype "passive"))
      (node (ref "U6") (pin "17") (pinfunction "PC2_17") (pintype "bidirectional"))
    )
    (net (code "27") (name "/GPS_MOSI") (class "Default")
      (node (ref "U13") (pin "26") (pinfunction "26_26") (pintype "passive"))
      (node (ref "U6") (pin "18") (pinfunction "PC3_18") (pintype "bidirectional"))
    )
    (net (code "28") (name "/GPS_RST") (class "Default")
      (node (ref "U13") (pin "23") (pinfunction "23_23") (pintype "passive"))
      (node (ref "U6") (pin "57") (pinfunction "PD10_57") (pintype "bidirectional"))
    )
    (net (code "29") (name "/GPS_SCLK") (class "Default")
      (node (ref "U13") (pin "6") (pinfunction "6_6") (pintype "passive"))
      (node (ref "U6") (pin "52") (pinfunction "PB13_52") (pintype "bidirectional"))
    )
    (net (code "30") (name "/GSM_PWR_ON") (class "Default")
      (node (ref "R30") (pin "2") (pinfunction "2_2") (pintype "passive"))
      (node (ref "U6") (pin "45") (pinfunction "PE14_45") (pintype "bidirectional"))
    )
    (net (code "31") (name "/GSM_RST") (class "Default")
      (node (ref "R36") (pin "2") (pinfunction "2_2") (pintype "passive"))
      (node (ref "U6") (pin "46") (pinfunction "PE15_46") (pintype "bidirectional"))
    )
    (net (code "32") (name "/G_PON") (class "Default")
      (node (ref "Q2") (pin "3") (pinfunction "C_3") (pintype "passive"))
      (node (ref "U8") (pin "20") (pinfunction "20_20") (pintype "passive"))
    )
    (net (code "33") (name "/G_RST") (class "Default")
      (node (ref "Q5") (pin "3") (pinfunction "C_3") (pintype "passive"))
      (node (ref "U8") (pin "23") (pinfunction "23_23") (pintype "passive"))
    )
    (net (code "34") (name "/I2C_SCL") (class "Default")
      (node (ref "U6") (pin "95") (pinfunction "PB8_95") (pintype "bidirectional"))
      (node (ref "U9") (pin "5") (pinfunction "A4_5") (pintype "bidirectional"))
    )
    (net (code "35") (name "/I2C_SCL_1.8V") (class "Default")
      (node (ref "R16") (pin "1") (pinfunction "1_1") (pintype "passive"))
      (node (ref "U4") (pin "10") (pinfunction "SCL_10") (pintype "input"))
      (node (ref "U8") (pin "54") (pinfunction "54_54") (pintype "passive"))
      (node (ref "U9") (pin "12") (pinfunction "B4_12") (pintype "bidirectional"))
    )
    (net (code "36") (name "/I2C_SDA") (class "Default")
      (node (ref "U6") (pin "96") (pinfunction "PB9_96") (pintype "bidirectional"))
      (node (ref "U9") (pin "4") (pinfunction "A3_4") (pintype "bidirectional"))
    )
    (net (code "37") (name "/I2C_SDA_1.8V") (class "Default")
      (node (ref "R17") (pin "1") (pinfunction "1_1") (pintype "passive"))
      (node (ref "U4") (pin "9") (pinfunction "SDA_9") (pintype "output"))
      (node (ref "U8") (pin "55") (pinfunction "55_55") (pintype "passive"))
      (node (ref "U9") (pin "13") (pinfunction "B3_13") (pintype "bidirectional"))
    )
    (net (code "38") (name "/ICE_CLK") (class "Default")
      (node (ref "J9") (pin "2") (pinfunction "2_2") (pintype "passive"))
      (node (ref "U14") (pin "24") (pinfunction "ICE_CLK_24") (pintype "passive"))
    )
    (net (code "39") (name "/ICE_DATA") (class "Default")
      (node (ref "J9") (pin "3") (pinfunction "3_3") (pintype "passive"))
      (node (ref "U14") (pin "23") (pinfunction "ICE_DAT_23") (pintype "passive"))
    )
    (net (code "40") (name "/ICE_RESET") (class "Default")
      (node (ref "J9") (pin "4") (pinfunction "4_4") (pintype "passive"))
      (node (ref "U14") (pin "22") (pinfunction "RESETN_22") (pintype "passive"))
    )
    (net (code "41") (name "/IR_LED") (class "Default")
      (node (ref "R21") (pin "2") (pinfunction "2_2") (pintype "passive"))
      (node (ref "U6") (pin "7") (pinfunction "PC13_7") (pintype "bidirectional"))
    )
    (net (code "42") (name "/LEDG") (class "Default")
      (node (ref "R15") (pin "1") (pinfunction "1_1") (pintype "passive"))
      (node (ref "U6") (pin "42") (pinfunction "PE11_42") (pintype "bidirectional"))
    )
    (net (code "43") (name "/LEDR") (class "Default")
      (node (ref "D1") (pin "1") (pinfunction "R_1") (pintype "passive"))
      (node (ref "U6") (pin "41") (pinfunction "PE10_41") (pintype "bidirectional"))
    )
    (net (code "44") (name "/LRN_SW") (class "Default")
      (node (ref "R45") (pin "2") (pinfunction "2_2") (pintype "passive"))
      (node (ref "U15") (pin "5") (pinfunction "LED/LRN_5") (pintype "passive"))
      (node (ref "U6") (pin "35") (pinfunction "PB0_35") (pintype "bidirectional"))
    )
    (net (code "45") (name "/Light_Sense") (class "Default")
      (node (ref "LDR1") (pin "1") (pinfunction "1_1") (pintype "passive"))
      (node (ref "R20") (pin "2") (pinfunction "2_2") (pintype "passive"))
      (node (ref "U6") (pin "8") (pinfunction "PC14_8") (pintype "bidirectional"))
    )
    (net (code "46") (name "/MIC+") (class "Default")
      (node (ref "C80") (pin "2") (pinfunction "2_2") (pintype "passive"))
      (node (ref "U14") (pin "43") (pinfunction "MIC+_43") (pintype "passive"))
    )
    (net (code "47") (name "/MIC-") (class "Default")
      (node (ref "C70") (pin "2") (pinfunction "2_2") (pintype "passive"))
      (node (ref "U14") (pin "44") (pinfunction "MIC-_44") (pintype "passive"))
    )
    (net (code "48") (name "/MIC_BIAS") (class "Default")
      (node (ref "C11") (pin "2") (pinfunction "2_2") (pintype "passive"))
      (node (ref "C32") (pin "2") (pinfunction "2_2") (pintype "passive"))
      (node (ref "R9") (pin "1") (pinfunction "1_1") (pintype "passive"))
      (node (ref "U4") (pin "1") (pinfunction "MICBIAS_1") (pintype "passive"))
    )
    (net (code "49") (name "/MIC_BIAS_VR") (class "Default")
      (node (ref "C79") (pin "2") (pinfunction "2_2") (pintype "passive"))
      (node (ref "R44") (pin "1") (pinfunction "1_1") (pintype "passive"))
      (node (ref "U14") (pin "45") (pinfunction "MICBIAS_45") (pintype "passive"))
    )
    (net (code "50") (name "/NET") (class "Default")
      (node (ref "R32") (pin "2") (pinfunction "2_2") (pintype "passive"))
      (node (ref "U8") (pin "21") (pinfunction "21_21") (pintype "passive"))
    )
    (net (code "51") (name "/OUT1") (class "Default")
      (node (ref "U15") (pin "12") (pinfunction "O/P1_12") (pintype "passive"))
      (node (ref "U6") (pin "38") (pinfunction "PE7_38") (pintype "bidirectional"))
    )
    (net (code "52") (name "/OUT2") (class "Default")
      (node (ref "U15") (pin "11") (pinfunction "O/P2_11") (pintype "passive"))
      (node (ref "U6") (pin "39") (pinfunction "PE8_39") (pintype "bidirectional"))
    )
    (net (code "53") (name "/OUT3") (class "Default")
      (node (ref "U15") (pin "10") (pinfunction "O/P3_10") (pintype "passive"))
      (node (ref "U6") (pin "40") (pinfunction "PE9_40") (pintype "bidirectional"))
    )
    (net (code "54") (name "/OUT4") (class "Default")
      (node (ref "U15") (pin "9") (pinfunction "O/P4_9") (pintype "passive"))
    )
    (net (code "55") (name "/PCM_CLK") (class "Default")
      (node (ref "C24") (pin "2") (pinfunction "2_2") (pintype "passive"))
      (node (ref "R12") (pin "1") (pinfunction "1_1") (pintype "passive"))
      (node (ref "U8") (pin "52") (pinfunction "52_52") (pintype "passive"))
    )
    (net (code "56") (name "/PCM_DIN") (class "Default")
      (node (ref "U4") (pin "15") (pinfunction "SDOUT_15") (pintype "output"))
      (node (ref "U8") (pin "53") (pinfunction "53_53") (pintype "passive"))
    )
    (net (code "57") (name "/PCM_DOUT") (class "Default")
      (node (ref "U4") (pin "16") (pinfunction "SDIN_16") (pintype "input"))
      (node (ref "U8") (pin "51") (pinfunction "51_51") (pintype "passive"))
    )
    (net (code "58") (name "/PCM_SYNC") (class "Default")
      (node (ref "U4") (pin "17") (pinfunction "LRCLK_17") (pintype "bidirectional"))
      (node (ref "U8") (pin "50") (pinfunction "50_50") (pintype "passive"))
    )
    (net (code "59") (name "/PGOOD") (class "Default")
      (node (ref "R1") (pin "2") (pinfunction "2_2") (pintype "passive"))
      (node (ref "U2") (pin "7") (pinfunction "7_7") (pintype "passive"))
      (node (ref "U6") (pin "44") (pinfunction "PE13_44") (pintype "bidirectional"))
    )
    (net (code "60") (name "/RF_CS") (class "Default")
      (node (ref "U6") (pin "77") (pinfunction "PA15_77") (pintype "bidirectional"))
    )
    (net (code "61") (name "/RF_MISO") (class "Default")
      (node (ref "U6") (pin "90") (pinfunction "PB4_90") (pintype "bidirectional"))
    )
    (net (code "62") (name "/RF_MOSI") (class "Default")
      (node (ref "U6") (pin "32") (pinfunction "PA7_32") (pintype "bidirectional"))
    )
    (net (code "63") (name "/RF_SCLK") (class "Default")
      (node (ref "U6") (pin "30") (pinfunction "PA5_30") (pintype "bidirectional"))
    )
    (net (code "64") (name "/RF_SDN") (class "Default")
      (node (ref "U6") (pin "15") (pinfunction "PC0_15") (pintype "bidirectional"))
    )
    (net (code "65") (name "/SDIO_CLK") (class "Default")
      (node (ref "J8") (pin "5") (pinfunction "CLK/SCLK_5") (pintype "passive"))
      (node (ref "U7") (pin "3") (pinfunction "A2_3") (pintype "bidirectional"))
    )
    (net (code "66") (name "/SDIO_CLK_1.8V") (class "Default")
      (node (ref "U7") (pin "14") (pinfunction "B2_14") (pintype "bidirectional"))
      (node (ref "U8") (pin "64") (pinfunction "64_64") (pintype "passive"))
    )
    (net (code "67") (name "/SDIO_CMD") (class "Default")
      (node (ref "J8") (pin "3") (pinfunction "CMD/DI_3") (pintype "passive"))
      (node (ref "R52") (pin "1") (pinfunction "1_1") (pintype "passive"))
      (node (ref "U7") (pin "4") (pinfunction "A3_4") (pintype "bidirectional"))
    )
    (net (code "68") (name "/SDIO_CMD_1.8V") (class "Default")
      (node (ref "U7") (pin "13") (pinfunction "B3_13") (pintype "bidirectional"))
      (node (ref "U8") (pin "65") (pinfunction "65_65") (pintype "passive"))
    )
    (net (code "69") (name "/SDIO_D0") (class "Default")
      (node (ref "J8") (pin "7") (pinfunction "DATA0/DO_7") (pintype "passive"))
      (node (ref "R49") (pin "1") (pinfunction "1_1") (pintype "passive"))
      (node (ref "U7") (pin "5") (pinfunction "A4_5") (pintype "bidirectional"))
    )
    (net (code "70") (name "/SDIO_D0_1.8V") (class "Default")
      (node (ref "U7") (pin "12") (pinfunction "B4_12") (pintype "bidirectional"))
      (node (ref "U8") (pin "66") (pinfunction "66_66") (pintype "passive"))
    )
    (net (code "71") (name "/SDIO_D1") (class "Default")
      (node (ref "J8") (pin "8") (pinfunction "DATA1/RSV_8") (pintype "passive"))
      (node (ref "R48") (pin "1") (pinfunction "1_1") (pintype "passive"))
      (node (ref "U7") (pin "7") (pinfunction "A6_7") (pintype "bidirectional"))
    )
    (net (code "72") (name "/SDIO_D1_1.8V") (class "Default")
      (node (ref "U7") (pin "10") (pinfunction "B6_10") (pintype "bidirectional"))
      (node (ref "U8") (pin "68") (pinfunction "68_68") (pintype "passive"))
    )
    (net (code "73") (name "/SDIO_D2") (class "Default")
      (node (ref "J8") (pin "1") (pinfunction "DATA2/RSV_1") (pintype "passive"))
      (node (ref "R50") (pin "1") (pinfunction "1_1") (pintype "passive"))
      (node (ref "U7") (pin "1") (pinfunction "A1_1") (pintype "bidirectional"))
    )
    (net (code "74") (name "/SDIO_D2_1.8V") (class "Default")
      (node (ref "U7") (pin "16") (pinfunction "B1_16") (pintype "bidirectional"))
      (node (ref "U8") (pin "63") (pinfunction "63_63") (pintype "passive"))
    )
    (net (code "75") (name "/SDIO_D3") (class "Default")
      (node (ref "J8") (pin "2") (pinfunction "DATA3/~{CS}_2") (pintype "passive"))
      (node (ref "R47") (pin "1") (pinfunction "1_1") (pintype "passive"))
      (node (ref "U7") (pin "6") (pinfunction "A5_6") (pintype "bidirectional"))
    )
    (net (code "76") (name "/SDIO_D3_1.8V") (class "Default")
      (node (ref "U7") (pin "11") (pinfunction "B5_11") (pintype "bidirectional"))
      (node (ref "U8") (pin "67") (pinfunction "67_67") (pintype "passive"))
    )
    (net (code "77") (name "/SIM_CLK") (class "Default")
      (node (ref "C46") (pin "2") (pinfunction "2_2") (pintype "passive"))
      (node (ref "J4") (pin "C3") (pinfunction "C3_C3") (pintype "passive"))
      (node (ref "R22") (pin "1") (pinfunction "1_1") (pintype "passive"))
      (node (ref "U10") (pin "4") (pinfunction "C3_4") (pintype "passive"))
    )
    (net (code "78") (name "/SIM_IO") (class "Default")
      (node (ref "C45") (pin "2") (pinfunction "2_2") (pintype "passive"))
      (node (ref "J4") (pin "C7") (pinfunction "C7_C7") (pintype "passive"))
      (node (ref "R23") (pin "1") (pinfunction "1_1") (pintype "passive"))
      (node (ref "U10") (pin "6") (pinfunction "C5_6") (pintype "passive"))
    )
    (net (code "79") (name "/SIM_RST") (class "Default")
      (node (ref "C44") (pin "2") (pinfunction "2_2") (pintype "passive"))
      (node (ref "J4") (pin "C2") (pinfunction "C2_C2") (pintype "passive"))
      (node (ref "R25") (pin "1") (pinfunction "1_1") (pintype "passive"))
      (node (ref "U10") (pin "3") (pinfunction "C2_3") (pintype "passive"))
    )
    (net (code "80") (name "/STATUS") (class "Default")
      (node (ref "R33") (pin "2") (pinfunction "2_2") (pintype "passive"))
      (node (ref "U8") (pin "22") (pinfunction "22_22") (pintype "passive"))
    )
    (net (code "81") (name "/SWCLK") (class "Default")
      (node (ref "J6") (pin "4") (pinfunction "4_4") (pintype "passive"))
      (node (ref "U6") (pin "76") (pinfunction "PA14_76") (pintype "bidirectional"))
    )
    (net (code "82") (name "/SWDIO") (class "Default")
      (node (ref "J6") (pin "3") (pinfunction "3_3") (pintype "passive"))
      (node (ref "U6") (pin "72") (pinfunction "PA13_72") (pintype "bidirectional"))
    )
    (net (code "83") (name "/Serial_OUT") (class "Default")
      (node (ref "U15") (pin "6") (pinfunction "SERIAL_O/P_6") (pintype "passive"))
      (node (ref "U6") (pin "36") (pinfunction "PB1_36") (pintype "bidirectional"))
    )
    (net (code "84") (name "/UART_RX_VR") (class "Default")
      (node (ref "U14") (pin "15") (pinfunction "PA.9_15") (pintype "passive"))
      (node (ref "U6") (pin "83") (pinfunction "PD2_83") (pintype "bidirectional"))
    )
    (net (code "85") (name "/UART_TX_VR") (class "Default")
      (node (ref "U14") (pin "16") (pinfunction "PA.8_16") (pintype "passive"))
      (node (ref "U6") (pin "80") (pinfunction "PC12_80") (pintype "bidirectional"))
    )
    (net (code "86") (name "/USART_RX") (class "Default")
      (node (ref "J10") (pin "3") (pinfunction "3_3") (pintype "passive"))
      (node (ref "U6") (pin "24") (pinfunction "PA1_24") (pintype "bidirectional"))
      (node (ref "U9") (pin "6") (pinfunction "A5_6") (pintype "bidirectional"))
    )
    (net (code "87") (name "/USART_RX_1.8V") (class "Default")
      (node (ref "U8") (pin "16") (pinfunction "16_16") (pintype "passive"))
      (node (ref "U9") (pin "11") (pinfunction "B5_11") (pintype "bidirectional"))
    )
    (net (code "88") (name "/USART_TX") (class "Default")
      (node (ref "J10") (pin "2") (pinfunction "2_2") (pintype "passive"))
      (node (ref "U6") (pin "23") (pinfunction "PA0_23") (pintype "bidirectional"))
      (node (ref "U9") (pin "7") (pinfunction "A6_7") (pintype "bidirectional"))
    )
    (net (code "89") (name "/USART_TX_1.8V") (class "Default")
      (node (ref "U8") (pin "17") (pinfunction "17_17") (pintype "passive"))
      (node (ref "U9") (pin "10") (pinfunction "B6_10") (pintype "bidirectional"))
    )
    (net (code "90") (name "/USB_D+") (class "Default")
      (node (ref "U6") (pin "71") (pinfunction "PA12_71") (pintype "bidirectional"))
      (node (ref "U8") (pin "28") (pinfunction "28_28") (pintype "passive"))
    )
    (net (code "91") (name "/USB_D-") (class "Default")
      (node (ref "U6") (pin "70") (pinfunction "PA11_70") (pintype "bidirectional"))
      (node (ref "U8") (pin "27") (pinfunction "27_27") (pintype "passive"))
    )
    (net (code "92") (name "/VR_WAKEUP") (class "Default")
      (node (ref "C82") (pin "2") (pinfunction "2_2") (pintype "passive"))
      (node (ref "R46") (pin "2") (pinfunction "2_2") (pintype "passive"))
      (node (ref "U14") (pin "1") (pinfunction "WAKEUP_1") (pintype "passive"))
      (node (ref "U6") (pin "61") (pinfunction "PD14_61") (pintype "bidirectional"))
    )
    (net (code "93") (name "/VSIM") (class "Default")
      (node (ref "C42") (pin "1") (pinfunction "1_1") (pintype "passive"))
      (node (ref "J4") (pin "C1") (pinfunction "C1_C1") (pintype "passive"))
      (node (ref "U10") (pin "5") (pinfunction "C4_5") (pintype "passive"))
      (node (ref "U8") (pin "59") (pinfunction "59_59") (pintype "passive"))
    )
    (net (code "94") (name "/W25X_SPI_CLK") (class "Default")
      (node (ref "U14") (pin "33") (pinfunction "PA.1_33") (pintype "passive"))
      (node (ref "U16") (pin "6") (pinfunction "CLK_6") (pintype "passive"))
    )
    (net (code "95") (name "/W25X_SPI_MISO") (class "Default")
      (node (ref "U14") (pin "30") (pinfunction "PA.3_30") (pintype "passive"))
      (node (ref "U16") (pin "2") (pinfunction "DO_2") (pintype "passive"))
    )
    (net (code "96") (name "/W25X_SPI_MOSI") (class "Default")
      (node (ref "U14") (pin "34") (pinfunction "PA.0_34") (pintype "passive"))
      (node (ref "U16") (pin "5") (pinfunction "DIO_5") (pintype "passive"))
    )
    (net (code "97") (name "/W25X_SPI_SSB0") (class "Default")
      (node (ref "U14") (pin "31") (pinfunction "PA.2_31") (pintype "passive"))
      (node (ref "U16") (pin "1") (pinfunction "/CS_1") (pintype "passive"))
    )
    (net (code "98") (name "/nIRQ") (class "Default")
      (node (ref "U6") (pin "16") (pinfunction "PC1_16") (pintype "bidirectional"))
    )
    (net (code "99") (name "1.8V_CODEC") (class "Default")
      (node (ref "C21") (pin "2") (pinfunction "2_2") (pintype "passive"))
      (node (ref "C22") (pin "2") (pinfunction "2_2") (pintype "passive"))
      (node (ref "C23") (pin "2") (pinfunction "2_2") (pintype "passive"))
      (node (ref "C28") (pin "2") (pinfunction "2_2") (pintype "passive"))
      (node (ref "C29") (pin "1") (pinfunction "1_1") (pintype "passive"))
      (node (ref "FB7") (pin "2") (pinfunction "2_2") (pintype "passive"))
      (node (ref "R11") (pin "2") (pinfunction "2_2") (pintype "passive"))
      (node (ref "R16") (pin "2") (pinfunction "2_2") (pintype "passive"))
      (node (ref "R17") (pin "2") (pinfunction "2_2") (pintype "passive"))
      (node (ref "U4") (pin "11") (pinfunction "DVDDIO_11") (pintype "power_in"))
      (node (ref "U4") (pin "13") (pinfunction "DVDD_13") (pintype "power_in"))
      (node (ref "U4") (pin "6") (pinfunction "AVDD_6") (pintype "power_in"))
    )
    (net (code "100") (name "1.8V_DOVDD") (class "Default")
      (node (ref "C61") (pin "2") (pinfunction "2_2") (pintype "passive"))
      (node (ref "C62") (pin "1") (pinfunction "1_1") (pintype "passive"))
      (node (ref "FB12") (pin "2") (pinfunction "2_2") (pintype "passive"))
      (node (ref "J5") (pin "11") (pinfunction "11_11") (pintype "passive"))
    )
    (net (code "101") (name "2.8V_AVDD") (class "Default")
      (node (ref "C53") (pin "2") (pinfunction "2_2") (pintype "passive"))
      (node (ref "C54") (pin "1") (pinfunction "1_1") (pintype "passive"))
      (node (ref "FB10") (pin "2") (pinfunction "2_2") (pintype "passive"))
      (node (ref "J5") (pin "4") (pinfunction "4_4") (pintype "passive"))
    )
    (net (code "102") (name "3.3V") (class "Default")
      (node (ref "C2") (pin "2") (pinfunction "2_2") (pintype "passive"))
      (node (ref "C3") (pin "2") (pinfunction "2_2") (pintype "passive"))
      (node (ref "FB2") (pin "1") (pinfunction "1_1") (pintype "passive"))
      (node (ref "FB3") (pin "1") (pinfunction "1_1") (pintype "passive"))
      (node (ref "FB4") (pin "1") (pinfunction "1_1") (pintype "passive"))
      (node (ref "FB5") (pin "1") (pinfunction "1_1") (pintype "passive"))
      (node (ref "FB6") (pin "1") (pinfunction "1_1") (pintype "passive"))
      (node (ref "L2") (pin "2") (pinfunction "2_2") (pintype "passive"))
      (node (ref "U1") (pin "3") (pinfunction "FB_3") (pintype "input"))
    )
    (net (code "103") (name "3.3V_CAM") (class "Default")
      (node (ref "C51") (pin "2") (pinfunction "2_2") (pintype "passive"))
      (node (ref "C59") (pin "2") (pinfunction "2_2") (pintype "passive"))
      (node (ref "FB5") (pin "2") (pinfunction "2_2") (pintype "passive"))
      (node (ref "LDR1") (pin "2") (pinfunction "2_2") (pintype "passive"))
      (node (ref "R18") (pin "2") (pinfunction "2_2") (pintype "passive"))
      (node (ref "U11") (pin "1") (pinfunction "VIN_1") (pintype "passive"))
      (node (ref "U12") (pin "1") (pinfunction "VIN_1") (pintype "passive"))
    )
    (net (code "104") (name "3.3V_GPS") (class "Default")
      (node (ref "C84") (pin "2") (pinfunction "2_2") (pintype "passive"))
      (node (ref "FB4") (pin "2") (pinfunction "2_2") (pintype "passive"))
      (node (ref "R55") (pin "2") (pinfunction "2_2") (pintype "passive"))
      (node (ref "U13") (pin "1") (pinfunction "1_1") (pintype "passive"))
      (node (ref "U13") (pin "8") (pinfunction "8_8") (pintype "passive"))
      (node (ref "U13") (pin "9") (pinfunction "9_9") (pintype "passive"))
    )
    (net (code "105") (name "3.3V_MCU") (class "Default")
      (node (ref "C26") (pin "2") (pinfunction "2_2") (pintype "passive"))
      (node (ref "C41") (pin "1") (pinfunction "1_1") (pintype "passive"))
      (node (ref "C47") (pin "1") (pinfunction "1_1") (pintype "passive"))
      (node (ref "C63") (pin "2") (pinfunction "2_2") (pintype "passive"))
      (node (ref "C64") (pin "2") (pinfunction "2_2") (pintype "passive"))
      (node (ref "C65") (pin "2") (pinfunction "2_2") (pintype "passive"))
      (node (ref "C66") (pin "2") (pinfunction "2_2") (pintype "passive"))
      (node (ref "C67") (pin "2") (pinfunction "2_2") (pintype "passive"))
      (node (ref "C68") (pin "2") (pinfunction "2_2") (pintype "passive"))
      (node (ref "FB11") (pin "2") (pinfunction "2_2") (pintype "passive"))
      (node (ref "FB3") (pin "2") (pinfunction "2_2") (pintype "passive"))
      (node (ref "FB9") (pin "2") (pinfunction "2_2") (pintype "passive"))
      (node (ref "J10") (pin "1") (pinfunction "1_1") (pintype "passive"))
      (node (ref "J6") (pin "1") (pinfunction "1_1") (pintype "passive"))
      (node (ref "J8") (pin "4") (pinfunction "VCC_4") (pintype "passive"))
      (node (ref "R1") (pin "1") (pinfunction "1_1") (pintype "passive"))
      (node (ref "R19") (pin "2") (pinfunction "2_2") (pintype "passive"))
      (node (ref "R2") (pin "1") (pinfunction "1_1") (pintype "passive"))
      (node (ref "R26") (pin "2") (pinfunction "2_2") (pintype "passive"))
      (node (ref "R27") (pin "1") (pinfunction "1_1") (pintype "passive"))
      (node (ref "R38") (pin "1") (pinfunction "1_1") (pintype "passive"))
      (node (ref "R39") (pin "1") (pinfunction "1_1") (pintype "passive"))
      (node (ref "R47") (pin "2") (pinfunction "2_2") (pintype "passive"))
      (node (ref "R48") (pin "2") (pinfunction "2_2") (pintype "passive"))
      (node (ref "R49") (pin "2") (pinfunction "2_2") (pintype "passive"))
      (node (ref "R50") (pin "2") (pinfunction "2_2") (pintype "passive"))
      (node (ref "R51") (pin "2") (pinfunction "2_2") (pintype "passive"))
      (node (ref "R52") (pin "2") (pinfunction "2_2") (pintype "passive"))
      (node (ref "U5") (pin "1") (pinfunction "VIN_1") (pintype "passive"))
      (node (ref "U6") (pin "100") (pinfunction "VDD_100") (pintype "power_in"))
      (node (ref "U6") (pin "11") (pinfunction "VDD_11") (pintype "power_in"))
      (node (ref "U6") (pin "19") (pinfunction "VDD_19") (pintype "power_in"))
      (node (ref "U6") (pin "28") (pinfunction "VDD_28") (pintype "power_in"))
      (node (ref "U6") (pin "50") (pinfunction "VDD_50") (pintype "power_in"))
      (node (ref "U6") (pin "75") (pinfunction "VDD_75") (pintype "power_in"))
      (node (ref "U7") (pin "2") (pinfunction "VCCA_2") (pintype "power_in"))
      (node (ref "U7") (pin "8") (pinfunction "OE_8") (pintype "input"))
      (node (ref "U9") (pin "2") (pinfunction "VCCA_2") (pintype "power_in"))
      (node (ref "U9") (pin "8") (pinfunction "OE_8") (pintype "input"))
    )
    (net (code "106") (name "3.3V_RF") (class "Default")
      (node (ref "C94") (pin "2") (pinfunction "2_2") (pintype "passive"))
      (node (ref "C95") (pin "2") (pinfunction "2_2") (pintype "passive"))
      (node (ref "D9") (pin "1") (pinfunction "A_1") (pintype "passive"))
      (node (ref "FB6") (pin "2") (pinfunction "2_2") (pintype "passive"))
      (node (ref "U15") (pin "4") (pinfunction "Vcc_4") (pintype "passive"))
    )
    (net (code "107") (name "3.3V_VCCF") (class "Default")
      (node (ref "C83") (pin "2") (pinfunction "2_2") (pintype "passive"))
      (node (ref "C85") (pin "2") (pinfunction "2_2") (pintype "passive"))
      (node (ref "U14") (pin "32") (pinfunction "VDD33_32") (pintype "passive"))
      (node (ref "U16") (pin "3") (pinfunction "/WP_3") (pintype "passive"))
      (node (ref "U16") (pin "7") (pinfunction "/HOLD_7") (pintype "passive"))
      (node (ref "U16") (pin "8") (pinfunction "VCC_8") (pintype "passive"))
    )
    (net (code "108") (name "3.3V_VR") (class "Default")
      (node (ref "C86") (pin "2") (pinfunction "2_2") (pintype "passive"))
      (node (ref "C89") (pin "2") (pinfunction "2_2") (pintype "passive"))
      (node (ref "C90") (pin "1") (pinfunction "1_1") (pintype "passive"))
      (node (ref "C96") (pin "2") (pinfunction "2_2") (pintype "passive"))
      (node (ref "FB13") (pin "1") (pinfunction "1_1") (pintype "passive"))
      (node (ref "FB2") (pin "2") (pinfunction "2_2") (pintype "passive"))
      (node (ref "J9") (pin "1") (pinfunction "1_1") (pintype "passive"))
      (node (ref "R46") (pin "1") (pinfunction "1_1") (pintype "passive"))
      (node (ref "U14") (pin "10") (pinfunction "VCCD_10") (pintype "passive"))
      (node (ref "U14") (pin "35") (pinfunction "VCCLDO_35") (pintype "passive"))
    )
    (net (code "109") (name "3.3V_VR_A") (class "Default")
      (node (ref "C72") (pin "1") (pinfunction "1_1") (pintype "passive"))
      (node (ref "C73") (pin "2") (pinfunction "2_2") (pintype "passive"))
      (node (ref "C97") (pin "2") (pinfunction "2_2") (pintype "passive"))
      (node (ref "FB13") (pin "2") (pinfunction "2_2") (pintype "passive"))
      (node (ref "FB14") (pin "1") (pinfunction "1_1") (pintype "passive"))
      (node (ref "U14") (pin "46") (pinfunction "VCCA_46") (pintype "passive"))
    )
    (net (code "110") (name "3.8V") (class "Default")
      (node (ref "C4") (pin "2") (pinfunction "2_2") (pintype "passive"))
      (node (ref "C5") (pin "1") (pinfunction "1_1") (pintype "passive"))
      (node (ref "FB1") (pin "1") (pinfunction "1_1") (pintype "passive"))
      (node (ref "R3") (pin "1") (pinfunction "1_1") (pintype "passive"))
      (node (ref "U1") (pin "4") (pinfunction "EN_4") (pintype "input"))
      (node (ref "U1") (pin "5") (pinfunction "VIN_5") (pintype "input"))
      (node (ref "U3") (pin "4") (pinfunction "VOUT_1_4") (pintype "passive"))
      (node (ref "U3") (pin "5") (pinfunction "VOUT_2_5") (pintype "passive"))
    )
    (net (code "111") (name "3.8V_GSM") (class "Default")
      (node (ref "C1") (pin "1") (pinfunction "1_1") (pintype "passive"))
      (node (ref "C25") (pin "1") (pinfunction "1_1") (pintype "passive"))
      (node (ref "C30") (pin "1") (pinfunction "1_1") (pintype "passive"))
      (node (ref "C31") (pin "1") (pinfunction "1_1") (pintype "passive"))
      (node (ref "C37") (pin "1") (pinfunction "1_1") (pintype "passive"))
      (node (ref "FB1") (pin "2") (pinfunction "2_2") (pintype "passive"))
      (node (ref "R14") (pin "1") (pinfunction "1_1") (pintype "passive"))
      (node (ref "R28") (pin "2") (pinfunction "2_2") (pintype "passive"))
      (node (ref "R29") (pin "2") (pinfunction "2_2") (pintype "passive"))
      (node (ref "U8") (pin "70") (pinfunction "70_70") (pintype "passive"))
      (node (ref "U8") (pin "71") (pinfunction "71_71") (pintype "passive"))
      (node (ref "U8") (pin "72") (pinfunction "72_72") (pintype "passive"))
    )
    (net (code "112") (name "AGND_Au") (class "Default")
      (node (ref "C11") (pin "1") (pinfunction "1_1") (pintype "passive"))
      (node (ref "C20") (pin "1") (pinfunction "1_1") (pintype "passive"))
      (node (ref "C23") (pin "1") (pinfunction "1_1") (pintype "passive"))
      (node (ref "C32") (pin "1") (pinfunction "1_1") (pintype "passive"))
      (node (ref "C33") (pin "1") (pinfunction "1_1") (pintype "passive"))
      (node (ref "C34") (pin "1") (pinfunction "1_1") (pintype "passive"))
      (node (ref "C35") (pin "1") (pinfunction "1_1") (pintype "passive"))
      (node (ref "FB8") (pin "1") (pinfunction "1_1") (pintype "passive"))
      (node (ref "J3") (pin "1") (pinfunction "1_1") (pintype "passive"))
      (node (ref "R10") (pin "2") (pinfunction "2_2") (pintype "passive"))
      (node (ref "U4") (pin "24") (pinfunction "MICGND_24") (pintype "power_in"))
      (node (ref "U4") (pin "25") (pinfunction "EP_25") (pintype "power_in"))
      (node (ref "U4") (pin "5") (pinfunction "AGND_5") (pintype "power_in"))
    )
    (net (code "113") (name "AGND_VR") (class "Default")
      (node (ref "C71") (pin "1") (pinfunction "1_1") (pintype "passive"))
      (node (ref "C72") (pin "2") (pinfunction "2_2") (pintype "passive"))
      (node (ref "C73") (pin "1") (pinfunction "1_1") (pintype "passive"))
      (node (ref "C74") (pin "1") (pinfunction "1_1") (pintype "passive"))
      (node (ref "C79") (pin "1") (pinfunction "1_1") (pintype "passive"))
      (node (ref "C97") (pin "1") (pinfunction "1_1") (pintype "passive"))
      (node (ref "C98") (pin "1") (pinfunction "1_1") (pintype "passive"))
      (node (ref "C99") (pin "2") (pinfunction "2_2") (pintype "passive"))
      (node (ref "FB15") (pin "2") (pinfunction "2_2") (pintype "passive"))
      (node (ref "MIC1") (pin "2") (pinfunction "2_2") (pintype "passive"))
      (node (ref "R42") (pin "2") (pinfunction "2_2") (pintype "passive"))
      (node (ref "U14") (pin "19") (pinfunction "VSSSPK_19") (pintype "passive"))
    )
    (net (code "114") (name "GND") (class "Default")
      (node (ref "C1") (pin "2") (pinfunction "2_2") (pintype "passive"))
      (node (ref "C10") (pin "1") (pinfunction "1_1") (pintype "passive"))
      (node (ref "C15") (pin "2") (pinfunction "2_2") (pintype "passive"))
      (node (ref "C16") (pin "2") (pinfunction "2_2") (pintype "passive"))
      (node (ref "C17") (pin "2") (pinfunction "2_2") (pintype "passive"))
      (node (ref "C18") (pin "2") (pinfunction "2_2") (pintype "passive"))
      (node (ref "C2") (pin "1") (pinfunction "1_1") (pintype "passive"))
      (node (ref "C21") (pin "1") (pinfunction "1_1") (pintype "passive"))
      (node (ref "C22") (pin "1") (pinfunction "1_1") (pintype "passive"))
      (node (ref "C24") (pin "1") (pinfunction "1_1") (pintype "passive"))
      (node (ref "C25") (pin "2") (pinfunction "2_2") (pintype "passive"))
      (node (ref "C26") (pin "1") (pinfunction "1_1") (pintype "passive"))
      (node (ref "C27") (pin "1") (pinfunction "1_1") (pintype "passive"))
      (node (ref "C28") (pin "1") (pinfunction "1_1") (pintype "passive"))
      (node (ref "C29") (pin "2") (pinfunction "2_2") (pintype "passive"))
      (node (ref "C3") (pin "1") (pinfunction "1_1") (pintype "passive"))
      (node (ref "C30") (pin "2") (pinfunction "2_2") (pintype "passive"))
      (node (ref "C31") (pin "2") (pinfunction "2_2") (pintype "passive"))
      (node (ref "C36") (pin "1") (pinfunction "1_1") (pintype "passive"))
      (node (ref "C37") (pin "2") (pinfunction "2_2") (pintype "passive"))
      (node (ref "C38") (pin "1") (pinfunction "1_1") (pintype "passive"))
      (node (ref "C39") (pin "2") (pinfunction "2_2") (pintype "passive"))
      (node (ref "C4") (pin "1") (pinfunction "1_1") (pintype "passive"))
      (node (ref "C41") (pin "2") (pinfunction "2_2") (pintype "passive"))
      (node (ref "C42") (pin "2") (pinfunction "2_2") (pintype "passive"))
      (node (ref "C43") (pin "1") (pinfunction "1_1") (pintype "passive"))
      (node (ref "C44") (pin "1") (pinfunction "1_1") (pintype "passive"))
      (node (ref "C45") (pin "1") (pinfunction "1_1") (pintype "passive"))
      (node (ref "C46") (pin "1") (pinfunction "1_1") (pintype "passive"))
      (node (ref "C47") (pin "2") (pinfunction "2_2") (pintype "passive"))
      (node (ref "C48") (pin "1") (pinfunction "1_1") (pintype "passive"))
      (node (ref "C49") (pin "1") (pinfunction "1_1") (pintype "passive"))
      (node (ref "C5") (pin "2") (pinfunction "2_2") (pintype "passive"))
      (node (ref "C50") (pin "1") (pinfunction "1_1") (pintype "passive"))
      (node (ref "C51") (pin "1") (pinfunction "1_1") (pintype "passive"))
      (node (ref "C52") (pin "1") (pinfunction "1_1") (pintype "passive"))
      (node (ref "C53") (pin "1") (pinfunction "1_1") (pintype "passive"))
      (node (ref "C54") (pin "2") (pinfunction "2_2") (pintype "passive"))
      (node (ref "C55") (pin "1") (pinfunction "1_1") (pintype "passive"))
      (node (ref "C56") (pin "1") (pinfunction "1_1") (pintype "passive"))
      (node (ref "C57") (pin "1") (pinfunction "1_1") (pintype "passive"))
      (node (ref "C58") (pin "1") (pinfunction "1_1") (pintype "passive"))
      (node (ref "C59") (pin "1") (pinfunction "1_1") (pintype "passive"))
      (node (ref "C6") (pin "2") (pinfunction "2_2") (pintype "passive"))
      (node (ref "C60") (pin "1") (pinfunction "1_1") (pintype "passive"))
      (node (ref "C61") (pin "1") (pinfunction "1_1") (pintype "passive"))
      (node (ref "C62") (pin "2") (pinfunction "2_2") (pintype "passive"))
      (node (ref "C63") (pin "1") (pinfunction "1_1") (pintype "passive"))
      (node (ref "C64") (pin "1") (pinfunction "1_1") (pintype "passive"))
      (node (ref "C65") (pin "1") (pinfunction "1_1") (pintype "passive"))
      (node (ref "C66") (pin "1") (pinfunction "1_1") (pintype "passive"))
      (node (ref "C67") (pin "1") (pinfunction "1_1") (pintype "passive"))
      (node (ref "C68") (pin "1") (pinfunction "1_1") (pintype "passive"))
      (node (ref "C69") (pin "2") (pinfunction "2_2") (pintype "passive"))
      (node (ref "C7") (pin "2") (pinfunction "2_2") (pintype "passive"))
      (node (ref "C75") (pin "2") (pinfunction "2_2") (pintype "passive"))
      (node (ref "C76") (pin "2") (pinfunction "2_2") (pintype "passive"))
      (node (ref "C8") (pin "1") (pinfunction "1_1") (pintype "passive"))
      (node (ref "C82") (pin "1") (pinfunction "1_1") (pintype "passive"))
      (node (ref "C83") (pin "1") (pinfunction "1_1") (pintype "passive"))
      (node (ref "C84") (pin "1") (pinfunction "1_1") (pintype "passive"))
      (node (ref "C85") (pin "1") (pinfunction "1_1") (pintype "passive"))
      (node (ref "C86") (pin "1") (pinfunction "1_1") (pintype "passive"))
      (node (ref "C89") (pin "1") (pinfunction "1_1") (pintype "passive"))
      (node (ref "C9") (pin "1") (pinfunction "1_1") (pintype "passive"))
      (node (ref "C90") (pin "2") (pinfunction "2_2") (pintype "passive"))
      (node (ref "C91") (pin "1") (pinfunction "1_1") (pintype "passive"))
      (node (ref "C92") (pin "2") (pinfunction "2_2") (pintype "passive"))
      (node (ref "C93") (pin "2") (pinfunction "2_2") (pintype "passive"))
      (node (ref "C94") (pin "1") (pinfunction "1_1") (pintype "passive"))
      (node (ref "C95") (pin "1") (pinfunction "1_1") (pintype "passive"))
      (node (ref "C96") (pin "1") (pinfunction "1_1") (pintype "passive"))
      (node (ref "FB15") (pin "1") (pinfunction "1_1") (pintype "passive"))
      (node (ref "FB8") (pin "2") (pinfunction "2_2") (pintype "passive"))
      (node (ref "J1") (pin "5") (pinfunction "GND_5") (pintype "power_in"))
      (node (ref "J1") (pin "6") (pintype "passive"))
      (node (ref "J10") (pin "4") (pinfunction "4_4") (pintype "passive"))
      (node (ref "J2") (pin "2") (pinfunction "2_2") (pintype "passive"))
      (node (ref "J4") (pin "C5") (pinfunction "C5_C5") (pintype "passive"))
      (node (ref "J5") (pin "2") (pinfunction "2_2") (pintype "passive"))
      (node (ref "J5") (pin "S1") (pinfunction "SHIELD_S1") (pintype "passive"))
      (node (ref "J5") (pin "S2") (pinfunction "SHIELD_S2") (pintype "passive"))
      (node (ref "J6") (pin "2") (pinfunction "2_2") (pintype "passive"))
      (node (ref "J7") (pin "2") (pinfunction "2_2") (pintype "passive"))
      (node (ref "J7") (pin "4") (pinfunction "4_4") (pintype "passive"))
      (node (ref "J8") (pin "10") (pinfunction "SHIELD_10") (pintype "passive"))
      (node (ref "J8") (pin "6") (pinfunction "GND_6") (pintype "passive"))
      (node (ref "J9") (pin "5") (pinfunction "5_5") (pintype "passive"))
      (node (ref "L4") (pin "1") (pinfunction "1_1") (pintype "passive"))
      (node (ref "Q1") (pin "2") (pinfunction "E_2") (pintype "passive"))
      (node (ref "Q2") (pin "2") (pinfunction "E_2") (pintype "passive"))
      (node (ref "Q3") (pin "2") (pinfunction "E_2") (pintype "passive"))
      (node (ref "Q4") (pin "2") (pinfunction "E_2") (pintype "passive"))
      (node (ref "Q5") (pin "2") (pinfunction "E_2") (pintype "passive"))
      (node (ref "Q6") (pin "2") (pinfunction "E_2") (pintype "passive"))
      (node (ref "R19") (pin "1") (pinfunction "1_1") (pintype "passive"))
      (node (ref "R20") (pin "1") (pinfunction "1_1") (pintype "passive"))
      (node (ref "R24") (pin "2") (pinfunction "2_2") (pintype "passive"))
      (node (ref "R26") (pin "1") (pinfunction "1_1") (pintype "passive"))
      (node (ref "R31") (pin "2") (pinfunction "2_2") (pintype "passive"))
      (node (ref "R34") (pin "2") (pinfunction "2_2") (pintype "passive"))
      (node (ref "R35") (pin "2") (pinfunction "2_2") (pintype "passive"))
      (node (ref "R37") (pin "2") (pinfunction "2_2") (pintype "passive"))
      (node (ref "R4") (pin "2") (pinfunction "2_2") (pintype "passive"))
      (node (ref "R5") (pin "2") (pinfunction "2_2") (pintype "passive"))
      (node (ref "R53") (pin "1") (pinfunction "1_1") (pintype "passive"))
      (node (ref "R54") (pin "1") (pinfunction "1_1") (pintype "passive"))
      (node (ref "R57") (pin "2") (pinfunction "2_2") (pintype "passive"))
      (node (ref "R6") (pin "2") (pinfunction "2_2") (pintype "passive"))
      (node (ref "R7") (pin "2") (pinfunction "2_2") (pintype "passive"))
      (node (ref "R8") (pin "2") (pinfunction "2_2") (pintype "passive"))
      (node (ref "SW1") (pin "2") (pinfunction "2_2") (pintype "passive"))
      (node (ref "U1") (pin "2") (pinfunction "MODE_2") (pintype "input"))
      (node (ref "U1") (pin "6") (pinfunction "GND_6") (pintype "power_in"))
      (node (ref "U10") (pin "2") (pinfunction "A_2") (pintype "passive"))
      (node (ref "U11") (pin "2") (pinfunction "GND_2") (pintype "passive"))
      (node (ref "U12") (pin "2") (pinfunction "GND_2") (pintype "passive"))
      (node (ref "U13") (pin "10") (pinfunction "10_10") (pintype "passive"))
      (node (ref "U13") (pin "11") (pinfunction "11_11") (pintype "passive"))
      (node (ref "U13") (pin "12") (pinfunction "12_12") (pintype "passive"))
      (node (ref "U13") (pin "13") (pinfunction "13_13") (pintype "passive"))
      (node (ref "U13") (pin "14") (pinfunction "14_14") (pintype "passive"))
      (node (ref "U13") (pin "15") (pinfunction "15_15") (pintype "passive"))
      (node (ref "U13") (pin "18") (pinfunction "18_18") (pintype "passive"))
      (node (ref "U13") (pin "19") (pinfunction "19_19") (pintype "passive"))
      (node (ref "U13") (pin "20") (pinfunction "20_20") (pintype "passive"))
      (node (ref "U13") (pin "21") (pinfunction "21_21") (pintype "passive"))
      (node (ref "U13") (pin "22") (pinfunction "22_22") (pintype "passive"))
      (node (ref "U13") (pin "27") (pinfunction "27_27") (pintype "passive"))
      (node (ref "U13") (pin "31") (pinfunction "31_31") (pintype "passive"))
      (node (ref "U13") (pin "4") (pinfunction "4_4") (pintype "passive"))
      (node (ref "U13") (pin "5") (pinfunction "5_5") (pintype "passive"))
      (node (ref "U14") (pin "25") (pinfunction "VSSD_25") (pintype "passive"))
      (node (ref "U15") (pin "2") (pinfunction "GND_2") (pintype "passive"))
      (node (ref "U15") (pin "3") (pinfunction "SLEEP_3") (pintype "passive"))
      (node (ref "U16") (pin "4") (pinfunction "GND_4") (pintype "passive"))
      (node (ref "U2") (pin "15") (pinfunction "15_15") (pintype "passive"))
      (node (ref "U2") (pin "17") (pinfunction "17_17") (pintype "passive"))
      (node (ref "U2") (pin "4") (pinfunction "4_4") (pintype "passive"))
      (node (ref "U2") (pin "6") (pinfunction "6_6") (pintype "passive"))
      (node (ref "U2") (pin "8") (pinfunction "8_8") (pintype "passive"))
      (node (ref "U3") (pin "15") (pinfunction "EP_15") (pintype "passive"))
      (node (ref "U3") (pin "2") (pinfunction "GND_2") (pintype "passive"))
      (node (ref "U4") (pin "12") (pinfunction "DGND_12") (pintype "power_in"))
      (node (ref "U5") (pin "2") (pinfunction "GND_2") (pintype "passive"))
      (node (ref "U6") (pin "10") (pinfunction "VSS_10") (pintype "power_in"))
      (node (ref "U6") (pin "20") (pinfunction "VSSA_20") (pintype "power_in"))
      (node (ref "U6") (pin "27") (pinfunction "VSS_27") (pintype "power_in"))
      (node (ref "U6") (pin "74") (pinfunction "VSS_74") (pintype "power_in"))
      (node (ref "U6") (pin "99") (pinfunction "PDR_ON_99") (pintype "power_in"))
      (node (ref "U7") (pin "9") (pinfunction "GND_9") (pintype "power_in"))
      (node (ref "U8") (pin "100") (pinfunction "100_100") (pintype "passive"))
      (node (ref "U8") (pin "101") (pinfunction "101_101") (pintype "passive"))
      (node (ref "U8") (pin "102") (pinfunction "102_102") (pintype "passive"))
      (node (ref "U8") (pin "103") (pinfunction "103_103") (pintype "passive"))
      (node (ref "U8") (pin "104") (pinfunction "104_104") (pintype "passive"))
      (node (ref "U8") (pin "105") (pinfunction "105_105") (pintype "passive"))
      (node (ref "U8") (pin "106") (pinfunction "106_106") (pintype "passive"))
      (node (ref "U8") (pin "107") (pinfunction "107_107") (pintype "passive"))
      (node (ref "U8") (pin "108") (pinfunction "108_108") (pintype "passive"))
      (node (ref "U8") (pin "109") (pinfunction "109_109") (pintype "passive"))
      (node (ref "U8") (pin "110") (pinfunction "110_110") (pintype "passive"))
      (node (ref "U8") (pin "111") (pinfunction "111_111") (pintype "passive"))
      (node (ref "U8") (pin "112") (pinfunction "112_112") (pintype "passive"))
      (node (ref "U8") (pin "113") (pinfunction "113_113") (pintype "passive"))
      (node (ref "U8") (pin "114") (pinfunction "114_114") (pintype "passive"))
      (node (ref "U8") (pin "115") (pinfunction "115_115") (pintype "passive"))
      (node (ref "U8") (pin "116") (pinfunction "116_116") (pintype "passive"))
      (node (ref "U8") (pin "117") (pinfunction "117_117") (pintype "passive"))
      (node (ref "U8") (pin "118") (pinfunction "118_118") (pintype "passive"))
      (node (ref "U8") (pin "119") (pinfunction "119_119") (pintype "passive"))
      (node (ref "U8") (pin "120") (pinfunction "120_120") (pintype "passive"))
      (node (ref "U8") (pin "121") (pinfunction "121_121") (pintype "passive"))
      (node (ref "U8") (pin "122") (pinfunction "122_122") (pintype "passive"))
      (node (ref "U8") (pin "123") (pinfunction "123_123") (pintype "passive"))
      (node (ref "U8") (pin "124") (pinfunction "124_124") (pintype "passive"))
      (node (ref "U8") (pin "125") (pinfunction "125_125") (pintype "passive"))
      (node (ref "U8") (pin "126") (pinfunction "126_126") (pintype "passive"))
      (node (ref "U8") (pin "127") (pinfunction "127_127") (pintype "passive"))
      (node (ref "U8") (pin "128") (pinfunction "128_128") (pintype "passive"))
      (node (ref "U8") (pin "129") (pinfunction "129_129") (pintype "passive"))
      (node (ref "U8") (pin "130") (pinfunction "130_130") (pintype "passive"))
      (node (ref "U8") (pin "131") (pinfunction "131_131") (pintype "passive"))
      (node (ref "U8") (pin "132") (pinfunction "132_132") (pintype "passive"))
      (node (ref "U8") (pin "133") (pinfunction "133_133") (pintype "passive"))
      (node (ref "U8") (pin "134") (pinfunction "134_134") (pintype "passive"))
      (node (ref "U8") (pin "135") (pinfunction "135_135") (pintype "passive"))
      (node (ref "U8") (pin "136") (pinfunction "136_136") (pintype "passive"))
      (node (ref "U8") (pin "137") (pinfunction "137_137") (pintype "passive"))
      (node (ref "U8") (pin "138") (pinfunction "138_138") (pintype "passive"))
      (node (ref "U8") (pin "139") (pinfunction "139_139") (pintype "passive"))
      (node (ref "U8") (pin "140") (pinfunction "140_140") (pintype "passive"))
      (node (ref "U8") (pin "141") (pinfunction "141_141") (pintype "passive"))
      (node (ref "U8") (pin "142") (pinfunction "142_142") (pintype "passive"))
      (node (ref "U8") (pin "143") (pinfunction "143_143") (pintype "passive"))
      (node (ref "U8") (pin "144") (pinfunction "144_144") (pintype "passive"))
      (node (ref "U8") (pin "145") (pinfunction "145_145") (pintype "passive"))
      (node (ref "U8") (pin "146") (pinfunction "146_146") (pintype "passive"))
      (node (ref "U8") (pin "147") (pinfunction "147_147") (pintype "passive"))
      (node (ref "U8") (pin "148") (pinfunction "148_148") (pintype "passive"))
      (node (ref "U8") (pin "149") (pinfunction "149_149") (pintype "passive"))
      (node (ref "U8") (pin "150") (pinfunction "150_150") (pintype "passive"))
      (node (ref "U8") (pin "151") (pinfunction "151_151") (pintype "passive"))
      (node (ref "U8") (pin "152") (pinfunction "152_152") (pintype "passive"))
      (node (ref "U8") (pin "2") (pinfunction "2_2") (pintype "passive"))
      (node (ref "U8") (pin "30") (pinfunction "30_30") (pintype "passive"))
      (node (ref "U8") (pin "32") (pinfunction "32_32") (pintype "passive"))
      (node (ref "U8") (pin "44") (pinfunction "44_44") (pintype "passive"))
      (node (ref "U8") (pin "46") (pinfunction "46_46") (pintype "passive"))
      (node (ref "U8") (pin "69") (pinfunction "69_69") (pintype "passive"))
      (node (ref "U8") (pin "73") (pinfunction "73_73") (pintype "passive"))
      (node (ref "U8") (pin "74") (pinfunction "74_74") (pintype "passive"))
      (node (ref "U8") (pin "76") (pinfunction "76_76") (pintype "passive"))
      (node (ref "U8") (pin "78") (pinfunction "78_78") (pintype "passive"))
      (node (ref "U8") (pin "79") (pinfunction "79_79") (pintype "passive"))
      (node (ref "U8") (pin "80") (pinfunction "80_80") (pintype "passive"))
      (node (ref "U8") (pin "82") (pinfunction "82_82") (pintype "passive"))
      (node (ref "U8") (pin "83") (pinfunction "83_83") (pintype "passive"))
      (node (ref "U8") (pin "85") (pinfunction "85_85") (pintype "passive"))
      (node (ref "U8") (pin "86") (pinfunction "86_86") (pintype "passive"))
      (node (ref "U8") (pin "88") (pinfunction "88_88") (pintype "passive"))
      (node (ref "U8") (pin "89") (pinfunction "89_89") (pintype "passive"))
      (node (ref "U8") (pin "90") (pinfunction "90_90") (pintype "passive"))
      (node (ref "U8") (pin "92") (pinfunction "92_92") (pintype "passive"))
      (node (ref "U8") (pin "93") (pinfunction "93_93") (pintype "passive"))
      (node (ref "U8") (pin "94") (pinfunction "94_94") (pintype "passive"))
      (node (ref "U8") (pin "95") (pinfunction "95_95") (pintype "passive"))
      (node (ref "U8") (pin "96") (pinfunction "96_96") (pintype "passive"))
      (node (ref "U8") (pin "97") (pinfunction "97_97") (pintype "passive"))
      (node (ref "U8") (pin "98") (pinfunction "98_98") (pintype "passive"))
      (node (ref "U8") (pin "99") (pinfunction "99_99") (pintype "passive"))
      (node (ref "U9") (pin "9") (pinfunction "GND_9") (pintype "power_in"))
      (node (ref "Y1") (pin "3") (pinfunction "OSC2_3") (pintype "passive"))
    )
    (net (code "115") (name "Net-(ANT1-PadF)") (class "Default")
      (node (ref "ANT1") (pin "F") (pinfunction "F_F") (pintype "passive"))
      (node (ref "L4") (pin "2") (pinfunction "2_2") (pintype "passive"))
    )
    (net (code "116") (name "Net-(ANT1-PadIN)") (class "Default")
      (node (ref "ANT1") (pin "IN") (pinfunction "IN_IN") (pintype "passive"))
      (node (ref "C69") (pin "1") (pinfunction "1_1") (pintype "passive"))
      (node (ref "L3") (pin "2") (pinfunction "2_2") (pintype "passive"))
    )
    (net (code "117") (name "Net-(ANT2-IN)") (class "Default")
      (node (ref "ANT2") (pin "1") (pinfunction "IN_1") (pintype "passive"))
      (node (ref "C92") (pin "1") (pinfunction "1_1") (pintype "passive"))
      (node (ref "L8") (pin "1") (pinfunction "1_1") (pintype "passive"))
    )
    (net (code "118") (name "Net-(C12-Pad1)") (class "Default")
      (node (ref "C12") (pin "1") (pinfunction "1_1") (pintype "passive"))
      (node (ref "J3") (pin "2") (pinfunction "2_2") (pintype "passive"))
    )
    (net (code "119") (name "Net-(C13-Pad1)") (class "Default")
      (node (ref "C13") (pin "1") (pinfunction "1_1") (pintype "passive"))
      (node (ref "J3") (pin "3") (pintype "passive"))
    )
    (net (code "120") (name "Net-(C14-Pad1)") (class "Default")
      (node (ref "C14") (pin "1") (pinfunction "1_1") (pintype "passive"))
      (node (ref "C17") (pin "1") (pinfunction "1_1") (pintype "passive"))
      (node (ref "C18") (pin "1") (pinfunction "1_1") (pintype "passive"))
      (node (ref "J3") (pin "4") (pintype "passive"))
    )
    (net (code "121") (name "Net-(C19-Pad1)") (class "Default")
      (node (ref "C19") (pin "1") (pinfunction "1_1") (pintype "passive"))
      (node (ref "C20") (pin "2") (pinfunction "2_2") (pintype "passive"))
      (node (ref "R10") (pin "1") (pinfunction "1_1") (pintype "passive"))
    )
    (net (code "122") (name "Net-(C70-Pad1)") (class "Default")
      (node (ref "C70") (pin "1") (pinfunction "1_1") (pintype "passive"))
      (node (ref "C71") (pin "2") (pinfunction "2_2") (pintype "passive"))
      (node (ref "R42") (pin "1") (pinfunction "1_1") (pintype "passive"))
    )
    (net (code "123") (name "Net-(C80-Pad1)") (class "Default")
      (node (ref "C80") (pin "1") (pinfunction "1_1") (pintype "passive"))
      (node (ref "MIC1") (pin "1") (pinfunction "1_1") (pintype "passive"))
      (node (ref "R44") (pin "2") (pinfunction "2_2") (pintype "passive"))
    )
    (net (code "124") (name "Net-(C98-Pad2)") (class "Default")
      (node (ref "C98") (pin "2") (pinfunction "2_2") (pintype "passive"))
      (node (ref "C99") (pin "1") (pinfunction "1_1") (pintype "passive"))
      (node (ref "FB14") (pin "2") (pinfunction "2_2") (pintype "passive"))
      (node (ref "U14") (pin "17") (pinfunction "VCCSPK_17") (pintype "passive"))
      (node (ref "U14") (pin "21") (pinfunction "VCCSPK_21") (pintype "passive"))
    )
    (net (code "125") (name "Net-(D1-G)") (class "Default")
      (node (ref "D1") (pin "2") (pinfunction "G_2") (pintype "passive"))
      (node (ref "R15") (pin "2") (pinfunction "2_2") (pintype "passive"))
    )
    (net (code "126") (name "Net-(D2-A)") (class "Default")
      (node (ref "D2") (pin "1") (pinfunction "A_1") (pintype "passive"))
      (node (ref "R18") (pin "1") (pinfunction "1_1") (pintype "passive"))
    )
    (net (code "127") (name "Net-(D2-K)") (class "Default")
      (node (ref "D2") (pin "2") (pinfunction "K_2") (pintype "passive"))
      (node (ref "D3") (pin "1") (pinfunction "A_1") (pintype "passive"))
    )
    (net (code "128") (name "Net-(D3-K)") (class "Default")
      (node (ref "D3") (pin "2") (pinfunction "K_2") (pintype "passive"))
      (node (ref "Q1") (pin "3") (pinfunction "C_3") (pintype "passive"))
    )
    (net (code "129") (name "Net-(D4-A)") (class "Default")
      (node (ref "D4") (pin "1") (pinfunction "A_1") (pintype "passive"))
      (node (ref "R28") (pin "1") (pinfunction "1_1") (pintype "passive"))
    )
    (net (code "130") (name "Net-(D4-K)") (class "Default")
      (node (ref "D4") (pin "2") (pinfunction "K_2") (pintype "passive"))
      (node (ref "Q3") (pin "3") (pinfunction "C_3") (pintype "passive"))
    )
    (net (code "131") (name "Net-(D5-A)") (class "Default")
      (node (ref "D5") (pin "1") (pinfunction "A_1") (pintype "passive"))
      (node (ref "R29") (pin "1") (pinfunction "1_1") (pintype "passive"))
    )
    (net (code "132") (name "Net-(D5-K)") (class "Default")
      (node (ref "D5") (pin "2") (pinfunction "K_2") (pintype "passive"))
      (node (ref "Q4") (pin "3") (pinfunction "C_3") (pintype "passive"))
    )
    (net (code "133") (name "Net-(D6-A)") (class "Default")
      (node (ref "D6") (pin "1") (pinfunction "A_1") (pintype "passive"))
      (node (ref "U14") (pin "4") (pinfunction "PB.5_4") (pintype "passive"))
    )
    (net (code "134") (name "Net-(D6-K)") (class "Default")
      (node (ref "D6") (pin "2") (pinfunction "K_2") (pintype "passive"))
      (node (ref "R53") (pin "2") (pinfunction "2_2") (pintype "passive"))
    )
    (net (code "135") (name "Net-(D7-A)") (class "Default")
      (node (ref "D7") (pin "1") (pinfunction "A_1") (pintype "passive"))
      (node (ref "U14") (pin "5") (pinfunction "PB.4_5") (pintype "passive"))
    )
    (net (code "136") (name "Net-(D7-K)") (class "Default")
      (node (ref "D7") (pin "2") (pinfunction "K_2") (pintype "passive"))
      (node (ref "R54") (pin "2") (pinfunction "2_2") (pintype "passive"))
    )
    (net (code "137") (name "Net-(D8-A)") (class "Default")
      (node (ref "D8") (pin "1") (pinfunction "A_1") (pintype "passive"))
      (node (ref "R55") (pin "1") (pinfunction "1_1") (pintype "passive"))
    )
    (net (code "138") (name "Net-(D8-K)") (class "Default")
      (node (ref "D8") (pin "2") (pinfunction "K_2") (pintype "passive"))
      (node (ref "Q6") (pin "3") (pinfunction "C_3") (pintype "passive"))
    )
    (net (code "139") (name "Net-(D9-K)") (class "Default")
      (node (ref "D9") (pin "2") (pinfunction "K_2") (pintype "passive"))
      (node (ref "R45") (pin "1") (pinfunction "1_1") (pintype "passive"))
    )
    (net (code "140") (name "Net-(J7-Pad1)") (class "Default")
      (node (ref "J7") (pin "1") (pinfunction "1_1") (pintype "passive"))
      (node (ref "R40") (pin "2") (pinfunction "2_2") (pintype "passive"))
    )
    (net (code "141") (name "Net-(J7-Pad3)") (class "Default")
      (node (ref "J7") (pin "3") (pinfunction "3_3") (pintype "passive"))
      (node (ref "R41") (pin "2") (pinfunction "2_2") (pintype "passive"))
    )
    (net (code "142") (name "Net-(J8-~{CD})") (class "Default")
      (node (ref "J8") (pin "9") (pinfunction "~{CD}_9") (pintype "passive"))
      (node (ref "R51") (pin "1") (pinfunction "1_1") (pintype "passive"))
    )
    (net (code "143") (name "Net-(Q1-B)") (class "Default")
      (node (ref "Q1") (pin "1") (pinfunction "B_1") (pintype "passive"))
      (node (ref "R21") (pin "1") (pinfunction "1_1") (pintype "passive"))
      (node (ref "R24") (pin "1") (pinfunction "1_1") (pintype "passive"))
    )
    (net (code "144") (name "Net-(Q2-B)") (class "Default")
      (node (ref "Q2") (pin "1") (pinfunction "B_1") (pintype "passive"))
      (node (ref "R30") (pin "1") (pinfunction "1_1") (pintype "passive"))
      (node (ref "R31") (pin "1") (pinfunction "1_1") (pintype "passive"))
    )
    (net (code "145") (name "Net-(Q3-B)") (class "Default")
      (node (ref "Q3") (pin "1") (pinfunction "B_1") (pintype "passive"))
      (node (ref "R32") (pin "1") (pinfunction "1_1") (pintype "passive"))
      (node (ref "R34") (pin "1") (pinfunction "1_1") (pintype "passive"))
    )
    (net (code "146") (name "Net-(Q4-B)") (class "Default")
      (node (ref "Q4") (pin "1") (pinfunction "B_1") (pintype "passive"))
      (node (ref "R33") (pin "1") (pinfunction "1_1") (pintype "passive"))
      (node (ref "R35") (pin "1") (pinfunction "1_1") (pintype "passive"))
    )
    (net (code "147") (name "Net-(Q5-B)") (class "Default")
      (node (ref "Q5") (pin "1") (pinfunction "B_1") (pintype "passive"))
      (node (ref "R36") (pin "1") (pinfunction "1_1") (pintype "passive"))
      (node (ref "R37") (pin "1") (pinfunction "1_1") (pintype "passive"))
    )
    (net (code "148") (name "Net-(Q6-B)") (class "Default")
      (node (ref "Q6") (pin "1") (pinfunction "B_1") (pintype "passive"))
      (node (ref "R56") (pin "1") (pinfunction "1_1") (pintype "passive"))
      (node (ref "R57") (pin "1") (pinfunction "1_1") (pintype "passive"))
    )
    (net (code "149") (name "Net-(R5-Pad1)") (class "Default")
      (node (ref "R5") (pin "1") (pinfunction "1_1") (pintype "passive"))
      (node (ref "U2") (pin "1") (pinfunction "1_1") (pintype "passive"))
    )
    (net (code "150") (name "Net-(R6-Pad1)") (class "Default")
      (node (ref "R6") (pin "1") (pinfunction "1_1") (pintype "passive"))
      (node (ref "U2") (pin "12") (pinfunction "12_12") (pintype "passive"))
    )
    (net (code "151") (name "Net-(R7-Pad1)") (class "Default")
      (node (ref "R7") (pin "1") (pinfunction "1_1") (pintype "passive"))
      (node (ref "U2") (pin "16") (pinfunction "16_16") (pintype "passive"))
    )
    (net (code "152") (name "Net-(R8-Pad1)") (class "Default")
      (node (ref "R8") (pin "1") (pinfunction "1_1") (pintype "passive"))
      (node (ref "U2") (pin "14") (pinfunction "14_14") (pintype "passive"))
    )
    (net (code "153") (name "Net-(R14-Pad2)") (class "Default")
      (node (ref "R14") (pin "2") (pinfunction "2_2") (pintype "passive"))
      (node (ref "U8") (pin "3") (pinfunction "3_3") (pintype "passive"))
    )
    (net (code "154") (name "Net-(R22-Pad2)") (class "Default")
      (node (ref "R22") (pin "2") (pinfunction "2_2") (pintype "passive"))
      (node (ref "U8") (pin "56") (pinfunction "56_56") (pintype "passive"))
    )
    (net (code "155") (name "Net-(R23-Pad2)") (class "Default")
      (node (ref "R23") (pin "2") (pinfunction "2_2") (pintype "passive"))
      (node (ref "U8") (pin "57") (pinfunction "57_57") (pintype "passive"))
    )
    (net (code "156") (name "Net-(R25-Pad2)") (class "Default")
      (node (ref "R25") (pin "2") (pinfunction "2_2") (pintype "passive"))
      (node (ref "U8") (pin "58") (pinfunction "58_58") (pintype "passive"))
    )
    (net (code "157") (name "Net-(R43-Pad1)") (class "Default")
      (node (ref "R43") (pin "1") (pinfunction "1_1") (pintype "passive"))
      (node (ref "U13") (pin "16") (pinfunction "16_16") (pintype "passive"))
    )
    (net (code "158") (name "Net-(R43-Pad2)") (class "Default")
      (node (ref "R43") (pin "2") (pinfunction "2_2") (pintype "passive"))
      (node (ref "U13") (pin "17") (pinfunction "17_17") (pintype "passive"))
    )
    (net (code "159") (name "Net-(R56-Pad2)") (class "Default")
      (node (ref "R56") (pin "2") (pinfunction "2_2") (pintype "passive"))
      (node (ref "U13") (pin "29") (pinfunction "29_29") (pintype "passive"))
    )
    (net (code "160") (name "Net-(SP1-SP+)") (class "Default")
      (node (ref "SP1") (pin "1") (pinfunction "SP+_1") (pintype "passive"))
      (node (ref "U14") (pin "18") (pinfunction "SPK+_18") (pintype "passive"))
    )
    (net (code "161") (name "Net-(SP1-SP-)") (class "Default")
      (node (ref "SP1") (pin "2") (pinfunction "SP-_2") (pintype "passive"))
      (node (ref "U14") (pin "20") (pinfunction "SPK-_20") (pintype "passive"))
    )
    (net (code "162") (name "Net-(U1-SW)") (class "Default")
      (node (ref "L2") (pin "1") (pinfunction "1_1") (pintype "passive"))
      (node (ref "U1") (pin "1") (pinfunction "SW_1") (pintype "output"))
    )
    (net (code "163") (name "Net-(U3-FB)") (class "Default")
      (node (ref "R3") (pin "2") (pinfunction "2_2") (pintype "passive"))
      (node (ref "R4") (pin "1") (pinfunction "1_1") (pintype "passive"))
      (node (ref "U3") (pin "3") (pinfunction "FB_3") (pintype "passive"))
    )
    (net (code "164") (name "Net-(U3-L1_1)") (class "Default")
      (node (ref "L1") (pin "1") (pinfunction "1_1") (pintype "passive"))
      (node (ref "U3") (pin "8") (pinfunction "L1_1_8") (pintype "passive"))
      (node (ref "U3") (pin "9") (pinfunction "L1_2_9") (pintype "passive"))
    )
    (net (code "165") (name "Net-(U3-L2_1)") (class "Default")
      (node (ref "L1") (pin "2") (pinfunction "2_2") (pintype "passive"))
      (node (ref "U3") (pin "6") (pinfunction "L2_1_6") (pintype "passive"))
      (node (ref "U3") (pin "7") (pinfunction "L2_2_7") (pintype "passive"))
    )
    (net (code "166") (name "Net-(U3-PS{slash}SYNC)") (class "Default")
      (node (ref "C10") (pin "2") (pinfunction "2_2") (pintype "passive"))
      (node (ref "U3") (pin "1") (pinfunction "VINA_1") (pintype "passive"))
      (node (ref "U3") (pin "13") (pinfunction "PS/SYNC_13") (pintype "passive"))
    )
    (net (code "167") (name "Net-(U4-BCLK)") (class "Default")
      (node (ref "R12") (pin "2") (pinfunction "2_2") (pintype "passive"))
      (node (ref "U4") (pin "18") (pinfunction "BCLK_18") (pintype "bidirectional"))
    )
    (net (code "168") (name "Net-(U4-MCLK)") (class "Default")
      (node (ref "R13") (pin "2") (pinfunction "2_2") (pintype "passive"))
      (node (ref "U4") (pin "14") (pinfunction "MCLK_14") (pintype "input"))
    )
    (net (code "169") (name "Net-(U4-MICLN)") (class "Default")
      (node (ref "C19") (pin "2") (pinfunction "2_2") (pintype "passive"))
      (node (ref "U4") (pin "22") (pinfunction "MICLN_22") (pintype "input"))
    )
    (net (code "170") (name "Net-(U4-MICLP)") (class "Default")
      (node (ref "C14") (pin "2") (pinfunction "2_2") (pintype "passive"))
      (node (ref "R9") (pin "2") (pinfunction "2_2") (pintype "passive"))
      (node (ref "U4") (pin "23") (pinfunction "MICLP_23") (pintype "input"))
    )
    (net (code "171") (name "Net-(U4-OUTP)") (class "Default")
      (node (ref "C40") (pin "2") (pinfunction "2_2") (pintype "passive"))
      (node (ref "U4") (pin "7") (pinfunction "OUTP_7") (pintype "output"))
    )
    (net (code "172") (name "Net-(U4-PREG)") (class "Default")
      (node (ref "C34") (pin "2") (pinfunction "2_2") (pintype "passive"))
      (node (ref "U4") (pin "3") (pinfunction "PREG_3") (pintype "passive"))
    )
    (net (code "173") (name "Net-(U4-REF)") (class "Default")
      (node (ref "C35") (pin "2") (pinfunction "2_2") (pintype "passive"))
      (node (ref "U4") (pin "4") (pinfunction "REF_4") (pintype "passive"))
    )
    (net (code "174") (name "Net-(U4-REG)") (class "Default")
      (node (ref "C33") (pin "2") (pinfunction "2_2") (pintype "passive"))
      (node (ref "U4") (pin "2") (pinfunction "REG_2") (pintype "passive"))
    )
    (net (code "175") (name "Net-(U4-~{IRQ})") (class "Default")
      (node (ref "R11") (pin "1") (pinfunction "1_1") (pintype "passive"))
      (node (ref "U4") (pin "19") (pinfunction "~{IRQ}_19") (pintype "output"))
    )
    (net (code "176") (name "Net-(U5-VOUT)") (class "Default")
      (node (ref "C27") (pin "2") (pinfunction "2_2") (pintype "passive"))
      (node (ref "FB7") (pin "1") (pinfunction "1_1") (pintype "passive"))
      (node (ref "U5") (pin "5") (pinfunction "VOUT_5") (pintype "passive"))
    )
    (net (code "177") (name "Net-(U6-NRST)") (class "Default")
      (node (ref "C48") (pin "2") (pinfunction "2_2") (pintype "passive"))
      (node (ref "R27") (pin "2") (pinfunction "2_2") (pintype "passive"))
      (node (ref "SW1") (pin "1") (pinfunction "1_1") (pintype "passive"))
      (node (ref "U6") (pin "14") (pinfunction "NRST_14") (pintype "bidirectional"))
    )
    (net (code "178") (name "Net-(U6-PH0)") (class "Default")
      (node (ref "U6") (pin "12") (pinfunction "PH0_12") (pintype "bidirectional"))
      (node (ref "Y1") (pin "2") (pinfunction "OSC2_2") (pintype "passive"))
    )
    (net (code "179") (name "Net-(U6-PH1)") (class "Default")
      (node (ref "U6") (pin "13") (pinfunction "PH1_13") (pintype "bidirectional"))
      (node (ref "Y1") (pin "1") (pinfunction "OSC1_1") (pintype "passive"))
    )
    (net (code "180") (name "Net-(U6-VBAT)") (class "Default")
      (node (ref "C55") (pin "2") (pinfunction "2_2") (pintype "passive"))
      (node (ref "C56") (pin "2") (pinfunction "2_2") (pintype "passive"))
      (node (ref "FB11") (pin "1") (pinfunction "1_1") (pintype "passive"))
      (node (ref "U6") (pin "6") (pinfunction "VBAT_6") (pintype "power_in"))
    )
    (net (code "181") (name "Net-(U6-VCAP_1)") (class "Default")
      (node (ref "C58") (pin "2") (pinfunction "2_2") (pintype "passive"))
      (node (ref "U6") (pin "49") (pinfunction "VCAP_1_49") (pintype "passive"))
    )
    (net (code "182") (name "Net-(U6-VCAP_2)") (class "Default")
      (node (ref "C57") (pin "2") (pinfunction "2_2") (pintype "passive"))
      (node (ref "U6") (pin "73") (pinfunction "VCAP_2_73") (pintype "passive"))
    )
    (net (code "183") (name "Net-(U6-VDDA)") (class "Default")
      (node (ref "C49") (pin "2") (pinfunction "2_2") (pintype "passive"))
      (node (ref "C50") (pin "2") (pinfunction "2_2") (pintype "passive"))
      (node (ref "FB9") (pin "1") (pinfunction "1_1") (pintype "passive"))
      (node (ref "U6") (pin "21") (pinfunction "VREF+_21") (pintype "power_in"))
      (node (ref "U6") (pin "22") (pinfunction "VDDA_22") (pintype "power_in"))
    )
    (net (code "184") (name "Net-(U11-VOUT)") (class "Default")
      (node (ref "C52") (pin "2") (pinfunction "2_2") (pintype "passive"))
      (node (ref "FB10") (pin "1") (pinfunction "1_1") (pintype "passive"))
      (node (ref "U11") (pin "5") (pinfunction "VOUT_5") (pintype "passive"))
    )
    (net (code "185") (name "Net-(U12-VOUT)") (class "Default")
      (node (ref "C60") (pin "2") (pinfunction "2_2") (pintype "passive"))
      (node (ref "FB12") (pin "1") (pinfunction "1_1") (pintype "passive"))
      (node (ref "U12") (pin "5") (pinfunction "VOUT_5") (pintype "passive"))
    )
    (net (code "186") (name "Net-(U14-VMID)") (class "Default")
      (node (ref "C74") (pin "2") (pinfunction "2_2") (pintype "passive"))
      (node (ref "U14") (pin "42") (pinfunction "VMID_42") (pintype "passive"))
    )
    (net (code "187") (name "Net-(U14-VREG)") (class "Default")
      (node (ref "C91") (pin "2") (pinfunction "2_2") (pintype "passive"))
      (node (ref "U14") (pin "11") (pinfunction "VREG_11") (pintype "passive"))
    )
    (net (code "188") (name "Net-(U14-XI32K)") (class "Default")
      (node (ref "C75") (pin "1") (pinfunction "1_1") (pintype "passive"))
      (node (ref "U14") (pin "40") (pinfunction "XI32K_40") (pintype "passive"))
      (node (ref "Y2") (pin "1") (pinfunction "OSC1_1") (pintype "passive"))
    )
    (net (code "189") (name "Net-(U14-XO32K)") (class "Default")
      (node (ref "C76") (pin "1") (pinfunction "1_1") (pintype "passive"))
      (node (ref "U14") (pin "39") (pinfunction "XO32K_39") (pintype "passive"))
      (node (ref "Y2") (pin "2") (pinfunction "OSC2_2") (pintype "passive"))
    )
    (net (code "190") (name "Net-(U15-ANT)") (class "Default")
      (node (ref "C93") (pin "1") (pinfunction "1_1") (pintype "passive"))
      (node (ref "L8") (pin "2") (pinfunction "2_2") (pintype "passive"))
      (node (ref "U15") (pin "1") (pinfunction "ANT_1") (pintype "passive"))
    )
    (net (code "191") (name "VBAT") (class "Default")
      (node (ref "J2") (pin "1") (pinfunction "1_1") (pintype "passive"))
      (node (ref "U2") (pin "2") (pinfunction "2_2") (pintype "passive"))
      (node (ref "U2") (pin "3") (pinfunction "3_3") (pintype "passive"))
    )
    (net (code "192") (name "VBUS") (class "Default")
      (node (ref "C8") (pin "2") (pinfunction "2_2") (pintype "passive"))
      (node (ref "C9") (pin "2") (pinfunction "2_2") (pintype "passive"))
      (node (ref "J1") (pin "1") (pinfunction "VBUS_1") (pintype "power_in"))
      (node (ref "U2") (pin "13") (pinfunction "13_13") (pintype "passive"))
    )
    (net (code "193") (name "VOUT_REG") (class "Default")
      (node (ref "C6") (pin "1") (pinfunction "1_1") (pintype "passive"))
      (node (ref "C7") (pin "1") (pinfunction "1_1") (pintype "passive"))
      (node (ref "U2") (pin "10") (pinfunction "10_10") (pintype "passive"))
      (node (ref "U2") (pin "11") (pinfunction "11_11") (pintype "passive"))
      (node (ref "U2") (pin "5") (pinfunction "5_5") (pintype "passive"))
      (node (ref "U3") (pin "10") (pinfunction "VIN_1_10") (pintype "passive"))
      (node (ref "U3") (pin "11") (pinfunction "VIN_2_11") (pintype "passive"))
      (node (ref "U3") (pin "12") (pinfunction "EN_12") (pintype "passive"))
    )
    (net (code "194") (name "V_INT") (class "Default")
      (node (ref "C38") (pin "2") (pinfunction "2_2") (pintype "passive"))
      (node (ref "C39") (pin "1") (pinfunction "1_1") (pintype "passive"))
      (node (ref "C43") (pin "2") (pinfunction "2_2") (pintype "passive"))
      (node (ref "U7") (pin "15") (pinfunction "VCCB_15") (pintype "power_in"))
      (node (ref "U8") (pin "5") (pinfunction "5_5") (pintype "passive"))
      (node (ref "U9") (pin "15") (pinfunction "VCCB_15") (pintype "power_in"))
    )
    (net (code "195") (name "unconnected-(ANT2-F-Pad2)") (class "Default")
      (node (ref "ANT2") (pin "2") (pinfunction "F_2") (pintype "passive"))
    )
    (net (code "196") (name "unconnected-(J1-D+-Pad3)") (class "Default")
      (node (ref "J1") (pin "3") (pinfunction "D+_3") (pintype "bidirectional"))
    )
    (net (code "197") (name "unconnected-(J1-D--Pad2)") (class "Default")
      (node (ref "J1") (pin "2") (pinfunction "D-_2") (pintype "bidirectional"))
    )
    (net (code "198") (name "unconnected-(J1-SHD-Pad4)") (class "Default")
      (node (ref "J1") (pin "4") (pinfunction "SHD_4") (pintype "passive"))
    )
    (net (code "199") (name "unconnected-(J4-PadC6)") (class "Default")
      (node (ref "J4") (pin "C6") (pinfunction "C6_C6") (pintype "passive"))
    )
    (net (code "200") (name "unconnected-(J5-Pad1)") (class "Default")
      (node (ref "J5") (pin "1") (pinfunction "1_1") (pintype "passive"))
    )
    (net (code "201") (name "unconnected-(J5-Pad6)") (class "Default")
      (node (ref "J5") (pin "6") (pinfunction "6_6") (pintype "passive"))
    )
    (net (code "202") (name "unconnected-(J5-Pad10)") (class "Default")
      (node (ref "J5") (pin "10") (pinfunction "10_10") (pintype "passive"))
    )
    (net (code "203") (name "unconnected-(J5-Pad15)") (class "Default")
      (node (ref "J5") (pin "15") (pinfunction "15_15") (pintype "passive"))
    )
    (net (code "204") (name "unconnected-(J5-Pad23)") (class "Default")
      (node (ref "J5") (pin "23") (pinfunction "23_23") (pintype "passive"))
    )
    (net (code "205") (name "unconnected-(J5-Pad24)") (class "Default")
      (node (ref "J5") (pin "24") (pinfunction "24_24") (pintype "passive"))
    )
    (net (code "206") (name "unconnected-(U3-PG-Pad14)") (class "Default")
      (node (ref "U3") (pin "14") (pinfunction "PG_14") (pintype "passive"))
    )
    (net (code "207") (name "unconnected-(U4-MICRN-Pad20)") (class "Default")
      (node (ref "U4") (pin "20") (pinfunction "MICRN_20") (pintype "input"))
    )
    (net (code "208") (name "unconnected-(U4-MICRP-Pad21)") (class "Default")
      (node (ref "U4") (pin "21") (pinfunction "MICRP_21") (pintype "input"))
    )
    (net (code "209") (name "unconnected-(U4-OUTN-Pad8)") (class "Default")
      (node (ref "U4") (pin "8") (pinfunction "OUTN_8") (pintype "output"))
    )
    (net (code "210") (name "unconnected-(U5-NC-Pad4)") (class "Default")
      (node (ref "U5") (pin "4") (pinfunction "NC_4") (pintype "passive"))
    )
    (net (code "211") (name "unconnected-(U6-PA2-Pad25)") (class "Default")
      (node (ref "U6") (pin "25") (pinfunction "PA2_25") (pintype "bidirectional"))
    )
    (net (code "212") (name "unconnected-(U6-PA3-Pad26)") (class "Default")
      (node (ref "U6") (pin "26") (pinfunction "PA3_26") (pintype "bidirectional"))
    )
    (net (code "213") (name "unconnected-(U6-PA9-Pad68)") (class "Default")
      (node (ref "U6") (pin "68") (pinfunction "PA9_68") (pintype "bidirectional"))
    )
    (net (code "214") (name "unconnected-(U6-PA10-Pad69)") (class "Default")
      (node (ref "U6") (pin "69") (pinfunction "PA10_69") (pintype "bidirectional"))
    )
    (net (code "215") (name "unconnected-(U6-PB5-Pad91)") (class "Default")
      (node (ref "U6") (pin "91") (pinfunction "PB5_91") (pintype "bidirectional"))
    )
    (net (code "216") (name "unconnected-(U6-PB14-Pad53)") (class "Default")
      (node (ref "U6") (pin "53") (pinfunction "PB14_53") (pintype "bidirectional"))
    )
    (net (code "217") (name "unconnected-(U6-PB15-Pad54)") (class "Default")
      (node (ref "U6") (pin "54") (pinfunction "PB15_54") (pintype "bidirectional"))
    )
    (net (code "218") (name "unconnected-(U6-PC4-Pad33)") (class "Default")
      (node (ref "U6") (pin "33") (pinfunction "PC4_33") (pintype "bidirectional"))
    )
    (net (code "219") (name "unconnected-(U6-PC5-Pad34)") (class "Default")
      (node (ref "U6") (pin "34") (pinfunction "PC5_34") (pintype "bidirectional"))
    )
    (net (code "220") (name "unconnected-(U6-PC10-Pad78)") (class "Default")
      (node (ref "U6") (pin "78") (pinfunction "PC10_78") (pintype "bidirectional"))
    )
    (net (code "221") (name "unconnected-(U6-PC15-Pad9)") (class "Default")
      (node (ref "U6") (pin "9") (pinfunction "PC15_9") (pintype "bidirectional"))
    )
    (net (code "222") (name "unconnected-(U6-PD0-Pad81)") (class "Default")
      (node (ref "U6") (pin "81") (pinfunction "PD0_81") (pintype "bidirectional"))
    )
    (net (code "223") (name "unconnected-(U6-PD1-Pad82)") (class "Default")
      (node (ref "U6") (pin "82") (pinfunction "PD1_82") (pintype "bidirectional"))
    )
    (net (code "224") (name "unconnected-(U6-PD3-Pad84)") (class "Default")
      (node (ref "U6") (pin "84") (pinfunction "PD3_84") (pintype "bidirectional"))
    )
    (net (code "225") (name "unconnected-(U6-PD4-Pad85)") (class "Default")
      (node (ref "U6") (pin "85") (pinfunction "PD4_85") (pintype "bidirectional"))
    )
    (net (code "226") (name "unconnected-(U6-PD5-Pad86)") (class "Default")
      (node (ref "U6") (pin "86") (pinfunction "PD5_86") (pintype "bidirectional"))
    )
    (net (code "227") (name "unconnected-(U6-PD6-Pad87)") (class "Default")
      (node (ref "U6") (pin "87") (pinfunction "PD6_87") (pintype "bidirectional"))
    )
    (net (code "228") (name "unconnected-(U6-PD8-Pad55)") (class "Default")
      (node (ref "U6") (pin "55") (pinfunction "PD8_55") (pintype "bidirectional"))
    )
    (net (code "229") (name "unconnected-(U6-PD9-Pad56)") (class "Default")
      (node (ref "U6") (pin "56") (pinfunction "PD9_56") (pintype "bidirectional"))
    )
    (net (code "230") (name "unconnected-(U6-PD11-Pad58)") (class "Default")
      (node (ref "U6") (pin "58") (pinfunction "PD11_58") (pintype "bidirectional"))
    )
    (net (code "231") (name "unconnected-(U6-PD12-Pad59)") (class "Default")
      (node (ref "U6") (pin "59") (pinfunction "PD12_59") (pintype "bidirectional"))
    )
    (net (code "232") (name "unconnected-(U6-PD13-Pad60)") (class "Default")
      (node (ref "U6") (pin "60") (pinfunction "PD13_60") (pintype "bidirectional"))
    )
    (net (code "233") (name "unconnected-(U6-PD15-Pad62)") (class "Default")
      (node (ref "U6") (pin "62") (pinfunction "PD15_62") (pintype "bidirectional"))
    )
    (net (code "234") (name "unconnected-(U6-PE0-Pad97)") (class "Default")
      (node (ref "U6") (pin "97") (pinfunction "PE0_97") (pintype "bidirectional"))
    )
    (net (code "235") (name "unconnected-(U6-PE1-Pad98)") (class "Default")
      (node (ref "U6") (pin "98") (pinfunction "PE1_98") (pintype "bidirectional"))
    )
    (net (code "236") (name "unconnected-(U6-PE2-Pad1)") (class "Default")
      (node (ref "U6") (pin "1") (pinfunction "PE2_1") (pintype "bidirectional"))
    )
    (net (code "237") (name "unconnected-(U6-PE3-Pad2)") (class "Default")
      (node (ref "U6") (pin "2") (pinfunction "PE3_2") (pintype "bidirectional"))
    )
    (net (code "238") (name "unconnected-(U8-Pad1)") (class "Default")
      (node (ref "U8") (pin "1") (pinfunction "1_1") (pintype "passive"))
    )
    (net (code "239") (name "unconnected-(U8-Pad4)") (class "Default")
      (node (ref "U8") (pin "4") (pinfunction "4_4") (pintype "passive"))
    )
    (net (code "240") (name "unconnected-(U8-Pad6)") (class "Default")
      (node (ref "U8") (pin "6") (pinfunction "6_6") (pintype "passive"))
    )
    (net (code "241") (name "unconnected-(U8-Pad7)") (class "Default")
      (node (ref "U8") (pin "7") (pinfunction "7_7") (pintype "passive"))
    )
    (net (code "242") (name "unconnected-(U8-Pad8)") (class "Default")
      (node (ref "U8") (pin "8") (pinfunction "8_8") (pintype "passive"))
    )
    (net (code "243") (name "unconnected-(U8-Pad9)") (class "Default")
      (node (ref "U8") (pin "9") (pinfunction "9_9") (pintype "passive"))
    )
    (net (code "244") (name "unconnected-(U8-Pad10)") (class "Default")
      (node (ref "U8") (pin "10") (pinfunction "10_10") (pintype "passive"))
    )
    (net (code "245") (name "unconnected-(U8-Pad11)") (class "Default")
      (node (ref "U8") (pin "11") (pinfunction "11_11") (pintype "passive"))
    )
    (net (code "246") (name "unconnected-(U8-Pad12)") (class "Default")
      (node (ref "U8") (pin "12") (pinfunction "12_12") (pintype "passive"))
    )
    (net (code "247") (name "unconnected-(U8-Pad13)") (class "Default")
      (node (ref "U8") (pin "13") (pinfunction "13_13") (pintype "passive"))
    )
    (net (code "248") (name "unconnected-(U8-Pad14)") (class "Default")
      (node (ref "U8") (pin "14") (pinfunction "14_14") (pintype "passive"))
    )
    (net (code "249") (name "unconnected-(U8-Pad15)") (class "Default")
      (node (ref "U8") (pin "15") (pinfunction "15_15") (pintype "passive"))
    )
    (net (code "250") (name "unconnected-(U8-Pad18)") (class "Default")
      (node (ref "U8") (pin "18") (pinfunction "18_18") (pintype "passive"))
    )
    (net (code "251") (name "unconnected-(U8-Pad19)") (class "Default")
      (node (ref "U8") (pin "19") (pinfunction "19_19") (pintype "passive"))
    )
    (net (code "252") (name "unconnected-(U8-Pad24)") (class "Default")
      (node (ref "U8") (pin "24") (pinfunction "24_24") (pintype "passive"))
    )
    (net (code "253") (name "unconnected-(U8-Pad25)") (class "Default")
      (node (ref "U8") (pin "25") (pinfunction "25_25") (pintype "passive"))
    )
    (net (code "254") (name "unconnected-(U8-Pad26)") (class "Default")
      (node (ref "U8") (pin "26") (pinfunction "26_26") (pintype "passive"))
    )
    (net (code "255") (name "unconnected-(U8-Pad29)") (class "Default")
      (node (ref "U8") (pin "29") (pinfunction "29_29") (pintype "passive"))
    )
    (net (code "256") (name "unconnected-(U8-Pad31)") (class "Default")
      (node (ref "U8") (pin "31") (pinfunction "31_31") (pintype "passive"))
    )
    (net (code "257") (name "unconnected-(U8-Pad33)") (class "Default")
      (node (ref "U8") (pin "33") (pinfunction "33_33") (pintype "passive"))
    )
    (net (code "258") (name "unconnected-(U8-Pad34)") (class "Default")
      (node (ref "U8") (pin "34") (pinfunction "34_34") (pintype "passive"))
    )
    (net (code "259") (name "unconnected-(U8-Pad35)") (class "Default")
      (node (ref "U8") (pin "35") (pinfunction "35_35") (pintype "passive"))
    )
    (net (code "260") (name "unconnected-(U8-Pad36)") (class "Default")
      (node (ref "U8") (pin "36") (pinfunction "36_36") (pintype "passive"))
    )
    (net (code "261") (name "unconnected-(U8-Pad37)") (class "Default")
      (node (ref "U8") (pin "37") (pinfunction "37_37") (pintype "passive"))
    )
    (net (code "262") (name "unconnected-(U8-Pad38)") (class "Default")
      (node (ref "U8") (pin "38") (pinfunction "38_38") (pintype "passive"))
    )
    (net (code "263") (name "unconnected-(U8-Pad39)") (class "Default")
      (node (ref "U8") (pin "39") (pinfunction "39_39") (pintype "passive"))
    )
    (net (code "264") (name "unconnected-(U8-Pad40)") (class "Default")
      (node (ref "U8") (pin "40") (pinfunction "40_40") (pintype "passive"))
    )
    (net (code "265") (name "unconnected-(U8-Pad41)") (class "Default")
      (node (ref "U8") (pin "41") (pinfunction "41_41") (pintype "passive"))
    )
    (net (code "266") (name "unconnected-(U8-Pad42)") (class "Default")
      (node (ref "U8") (pin "42") (pinfunction "42_42") (pintype "passive"))
    )
    (net (code "267") (name "unconnected-(U8-Pad43)") (class "Default")
      (node (ref "U8") (pin "43") (pinfunction "43_43") (pintype "passive"))
    )
    (net (code "268") (name "unconnected-(U8-Pad45)") (class "Default")
      (node (ref "U8") (pin "45") (pinfunction "45_45") (pintype "passive"))
    )
    (net (code "269") (name "unconnected-(U8-Pad47)") (class "Default")
      (node (ref "U8") (pin "47") (pinfunction "47_47") (pintype "passive"))
    )
    (net (code "270") (name "unconnected-(U8-Pad48)") (class "Default")
      (node (ref "U8") (pin "48") (pinfunction "48_48") (pintype "passive"))
    )
    (net (code "271") (name "unconnected-(U8-Pad49)") (class "Default")
      (node (ref "U8") (pin "49") (pinfunction "49_49") (pintype "passive"))
    )
    (net (code "272") (name "unconnected-(U8-Pad60)") (class "Default")
      (node (ref "U8") (pin "60") (pinfunction "60_60") (pintype "passive"))
    )
    (net (code "273") (name "unconnected-(U8-Pad62)") (class "Default")
      (node (ref "U8") (pin "62") (pinfunction "62_62") (pintype "passive"))
    )
    (net (code "274") (name "unconnected-(U8-Pad75)") (class "Default")
      (node (ref "U8") (pin "75") (pinfunction "75_75") (pintype "passive"))
    )
    (net (code "275") (name "unconnected-(U8-Pad77)") (class "Default")
      (node (ref "U8") (pin "77") (pinfunction "77_77") (pintype "passive"))
    )
    (net (code "276") (name "unconnected-(U8-Pad84)") (class "Default")
      (node (ref "U8") (pin "84") (pinfunction "84_84") (pintype "passive"))
    )
    (net (code "277") (name "unconnected-(U8-Pad91)") (class "Default")
      (node (ref "U8") (pin "91") (pinfunction "91_91") (pintype "passive"))
    )
    (net (code "278") (name "unconnected-(U9-A1-Pad1)") (class "Default")
      (node (ref "U9") (pin "1") (pinfunction "A1_1") (pintype "bidirectional"))
    )
    (net (code "279") (name "unconnected-(U9-A2-Pad3)") (class "Default")
      (node (ref "U9") (pin "3") (pinfunction "A2_3") (pintype "bidirectional"))
    )
    (net (code "280") (name "unconnected-(U9-B1-Pad16)") (class "Default")
      (node (ref "U9") (pin "16") (pinfunction "B1_16") (pintype "bidirectional"))
    )
    (net (code "281") (name "unconnected-(U9-B2-Pad14)") (class "Default")
      (node (ref "U9") (pin "14") (pinfunction "B2_14") (pintype "bidirectional"))
    )
    (net (code "282") (name "unconnected-(U10-C1-Pad1)") (class "Default")
      (node (ref "U10") (pin "1") (pinfunction "C1_1") (pintype "passive"))
    )
    (net (code "283") (name "unconnected-(U11-NC-Pad4)") (class "Default")
      (node (ref "U11") (pin "4") (pinfunction "NC_4") (pintype "passive"))
    )
    (net (code "284") (name "unconnected-(U12-NC-Pad4)") (class "Default")
      (node (ref "U12") (pin "4") (pinfunction "NC_4") (pintype "passive"))
    )
    (net (code "285") (name "unconnected-(U13-Pad2)") (class "Default")
      (node (ref "U13") (pin "2") (pinfunction "2_2") (pintype "passive"))
    )
    (net (code "286") (name "unconnected-(U13-Pad7)") (class "Default")
      (node (ref "U13") (pin "7") (pinfunction "7_7") (pintype "passive"))
    )
    (net (code "287") (name "unconnected-(U13-Pad24)") (class "Default")
      (node (ref "U13") (pin "24") (pinfunction "24_24") (pintype "passive"))
    )
    (net (code "288") (name "unconnected-(U13-Pad28)") (class "Default")
      (node (ref "U13") (pin "28") (pinfunction "28_28") (pintype "passive"))
    )
    (net (code "289") (name "unconnected-(U13-Pad30)") (class "Default")
      (node (ref "U13") (pin "30") (pinfunction "30_30") (pintype "passive"))
    )
    (net (code "290") (name "unconnected-(U14-NC-Pad12)") (class "Default")
      (node (ref "U14") (pin "12") (pinfunction "NC_12") (pintype "passive"))
    )
    (net (code "291") (name "unconnected-(U14-NC-Pad13)") (class "Default")
      (node (ref "U14") (pin "13") (pinfunction "NC_13") (pintype "passive"))
    )
    (net (code "292") (name "unconnected-(U14-PA.4-Pad29)") (class "Default")
      (node (ref "U14") (pin "29") (pinfunction "PA.4_29") (pintype "passive"))
    )
    (net (code "293") (name "unconnected-(U14-PA.5-Pad28)") (class "Default")
      (node (ref "U14") (pin "28") (pinfunction "PA.5_28") (pintype "passive"))
    )
    (net (code "294") (name "unconnected-(U14-PA.6-Pad27)") (class "Default")
      (node (ref "U14") (pin "27") (pinfunction "PA.6_27") (pintype "passive"))
    )
    (net (code "295") (name "unconnected-(U14-PA.7-Pad26)") (class "Default")
      (node (ref "U14") (pin "26") (pinfunction "PA.7_26") (pintype "passive"))
    )
    (net (code "296") (name "unconnected-(U14-PA.10-Pad48)") (class "Default")
      (node (ref "U14") (pin "48") (pinfunction "PA.10_48") (pintype "passive"))
    )
    (net (code "297") (name "unconnected-(U14-PA.11-Pad47)") (class "Default")
      (node (ref "U14") (pin "47") (pinfunction "PA.11_47") (pintype "passive"))
    )
    (net (code "298") (name "unconnected-(U14-PA.12-Pad38)") (class "Default")
      (node (ref "U14") (pin "38") (pinfunction "PA.12_38") (pintype "passive"))
    )
    (net (code "299") (name "unconnected-(U14-PA.13-Pad37)") (class "Default")
      (node (ref "U14") (pin "37") (pinfunction "PA.13_37") (pintype "passive"))
    )
    (net (code "300") (name "unconnected-(U14-PA.14-Pad36)") (class "Default")
      (node (ref "U14") (pin "36") (pinfunction "PA.14_36") (pintype "passive"))
    )
    (net (code "301") (name "unconnected-(U14-PA.15{slash}SDIN-Pad14)") (class "Default")
      (node (ref "U14") (pin "14") (pinfunction "PA.15/SDIN_14") (pintype "passive"))
    )
    (net (code "302") (name "unconnected-(U14-PB.0-Pad9)") (class "Default")
      (node (ref "U14") (pin "9") (pinfunction "PB.0_9") (pintype "passive"))
    )
    (net (code "303") (name "unconnected-(U14-PB.1-Pad8)") (class "Default")
      (node (ref "U14") (pin "8") (pinfunction "PB.1_8") (pintype "passive"))
    )
    (net (code "304") (name "unconnected-(U14-PB.2-Pad7)") (class "Default")
      (node (ref "U14") (pin "7") (pinfunction "PB.2_7") (pintype "passive"))
    )
    (net (code "305") (name "unconnected-(U14-PB.3-Pad6)") (class "Default")
      (node (ref "U14") (pin "6") (pinfunction "PB.3_6") (pintype "passive"))
    )
    (net (code "306") (name "unconnected-(U14-PB.6-Pad3)") (class "Default")
      (node (ref "U14") (pin "3") (pinfunction "PB.6_3") (pintype "passive"))
    )
    (net (code "307") (name "unconnected-(U14-PB.7-Pad2)") (class "Default")
      (node (ref "U14") (pin "2") (pinfunction "PB.7_2") (pintype "passive"))
    )
    (net (code "308") (name "unconnected-(U14-VSSA-Pad41)") (class "Default")
      (node (ref "U14") (pin "41") (pinfunction "VSSA_41") (pintype "passive"))
    )
    (net (code "309") (name "unconnected-(U15-MOM{slash}LAT-Pad8)") (class "Default")
      (node (ref "U15") (pin "8") (pinfunction "MOM/LAT_8") (pintype "passive"))
    )
    (net (code "310") (name "unconnected-(U15-NC-Pad7)") (class "Default")
      (node (ref "U15") (pin "7") (pinfunction "NC_7") (pintype "passive"))
    )
  )
)
